# oresat-acs-card.net
KiCad netlist of a schematic drawn in EAGLE
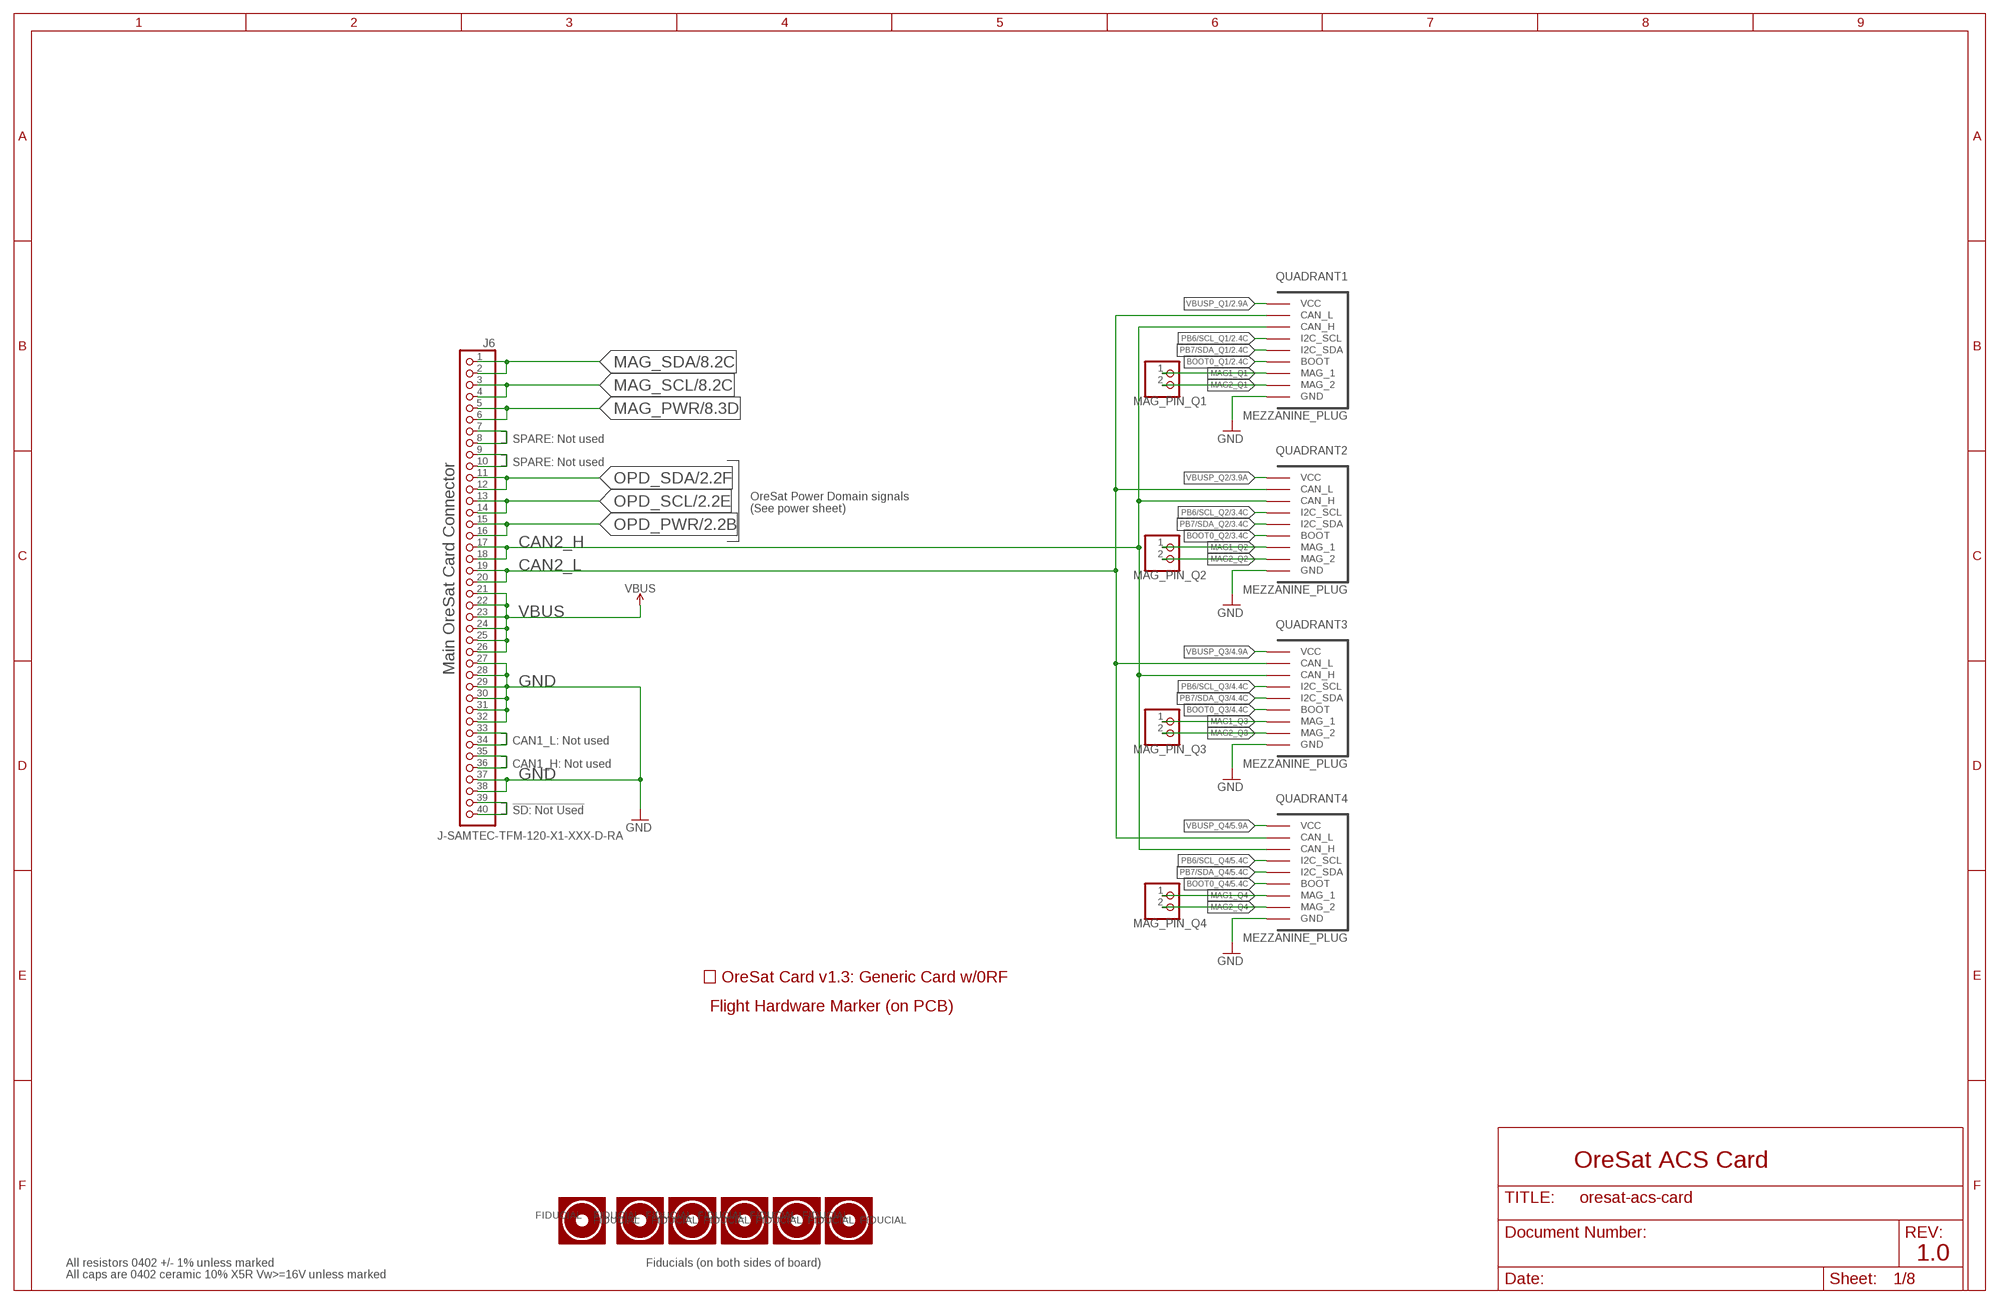
[diagram p0: schematic, sheet 1]
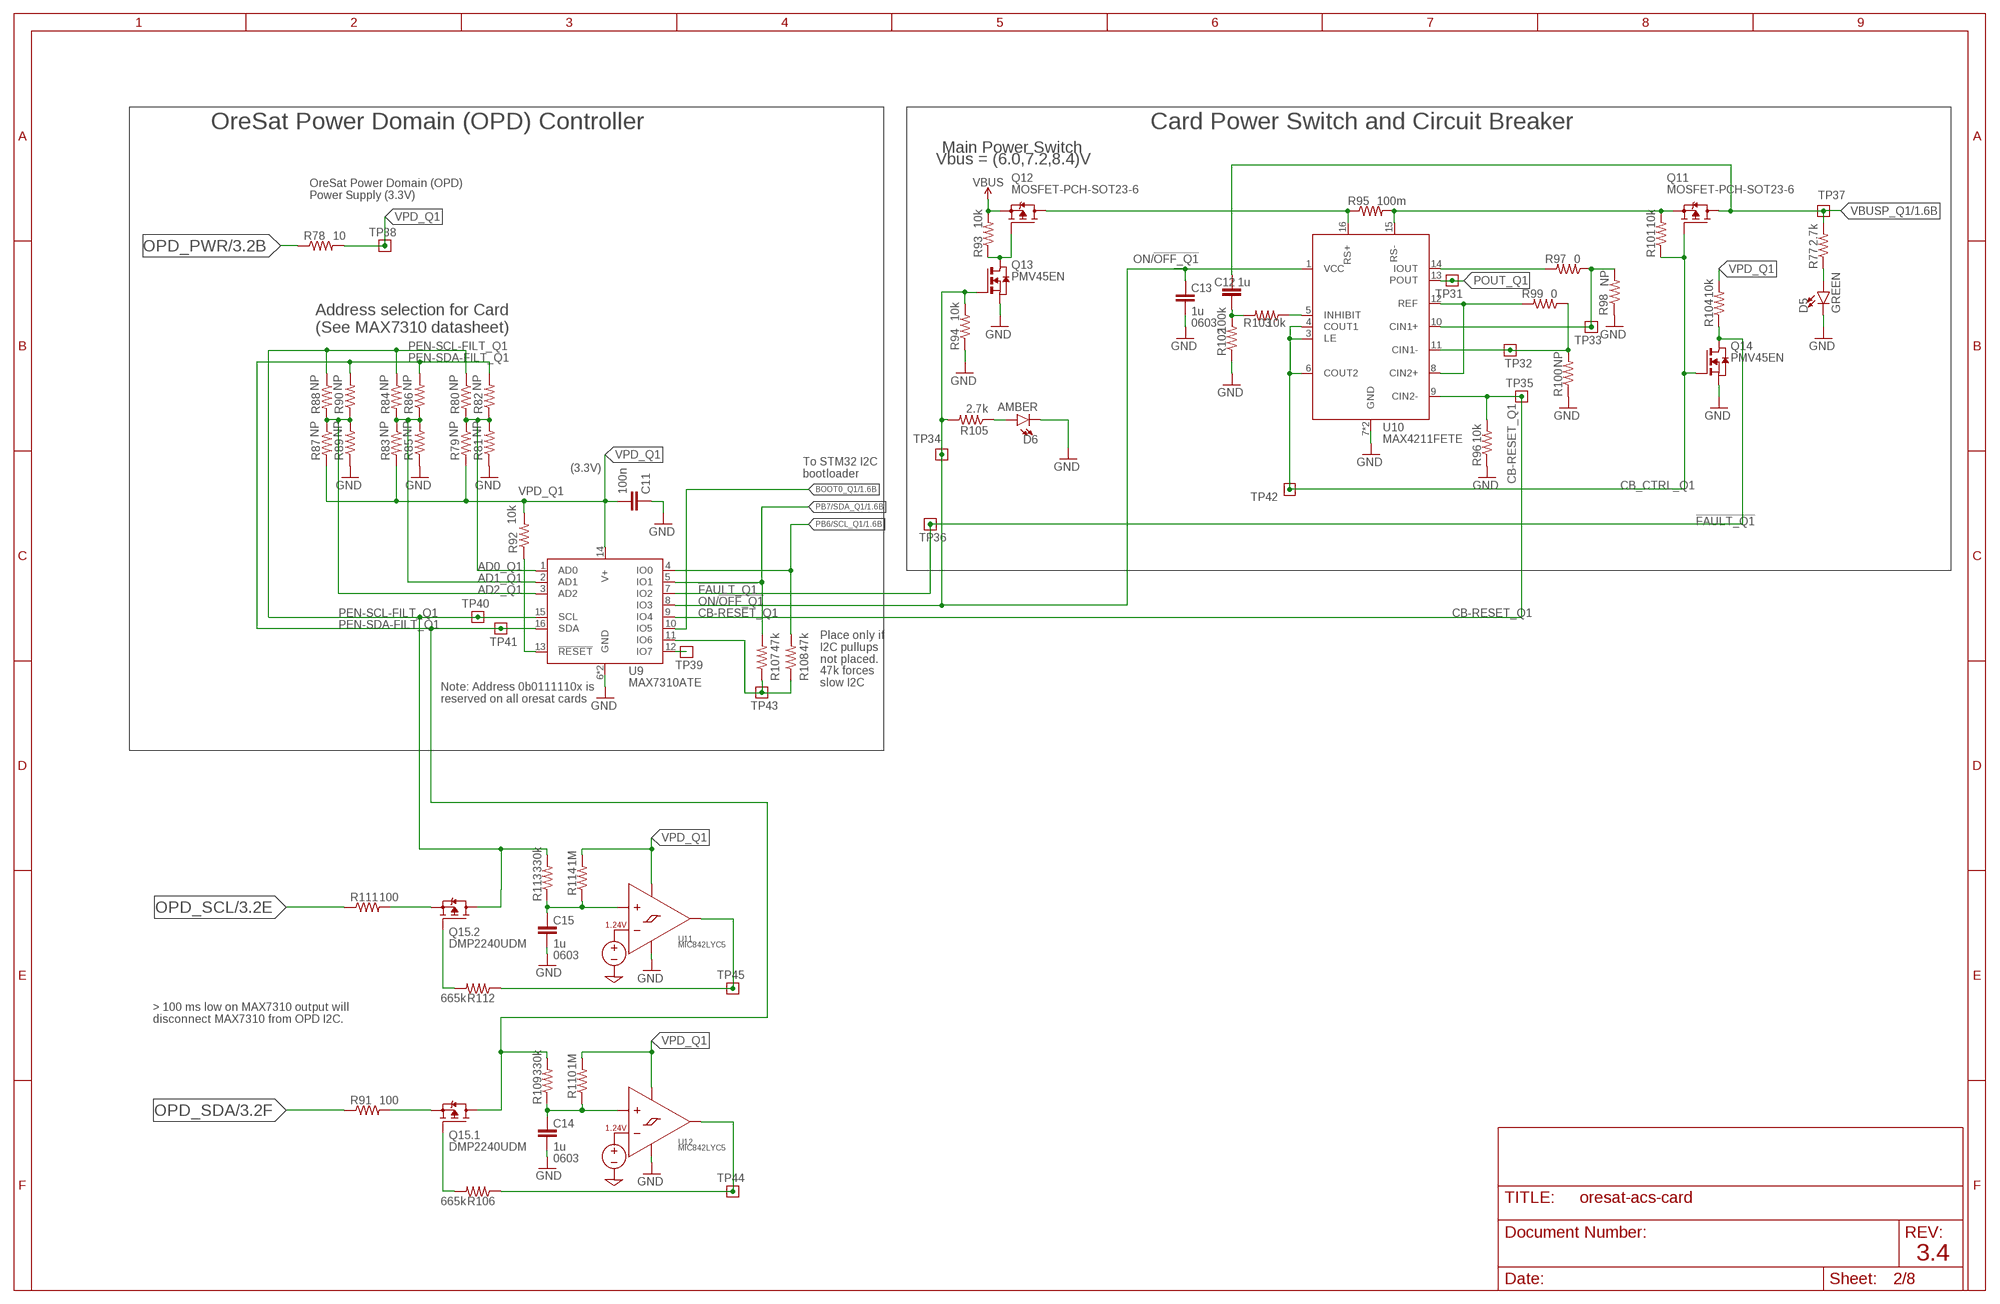
[diagram p1: schematic, sheet 2]
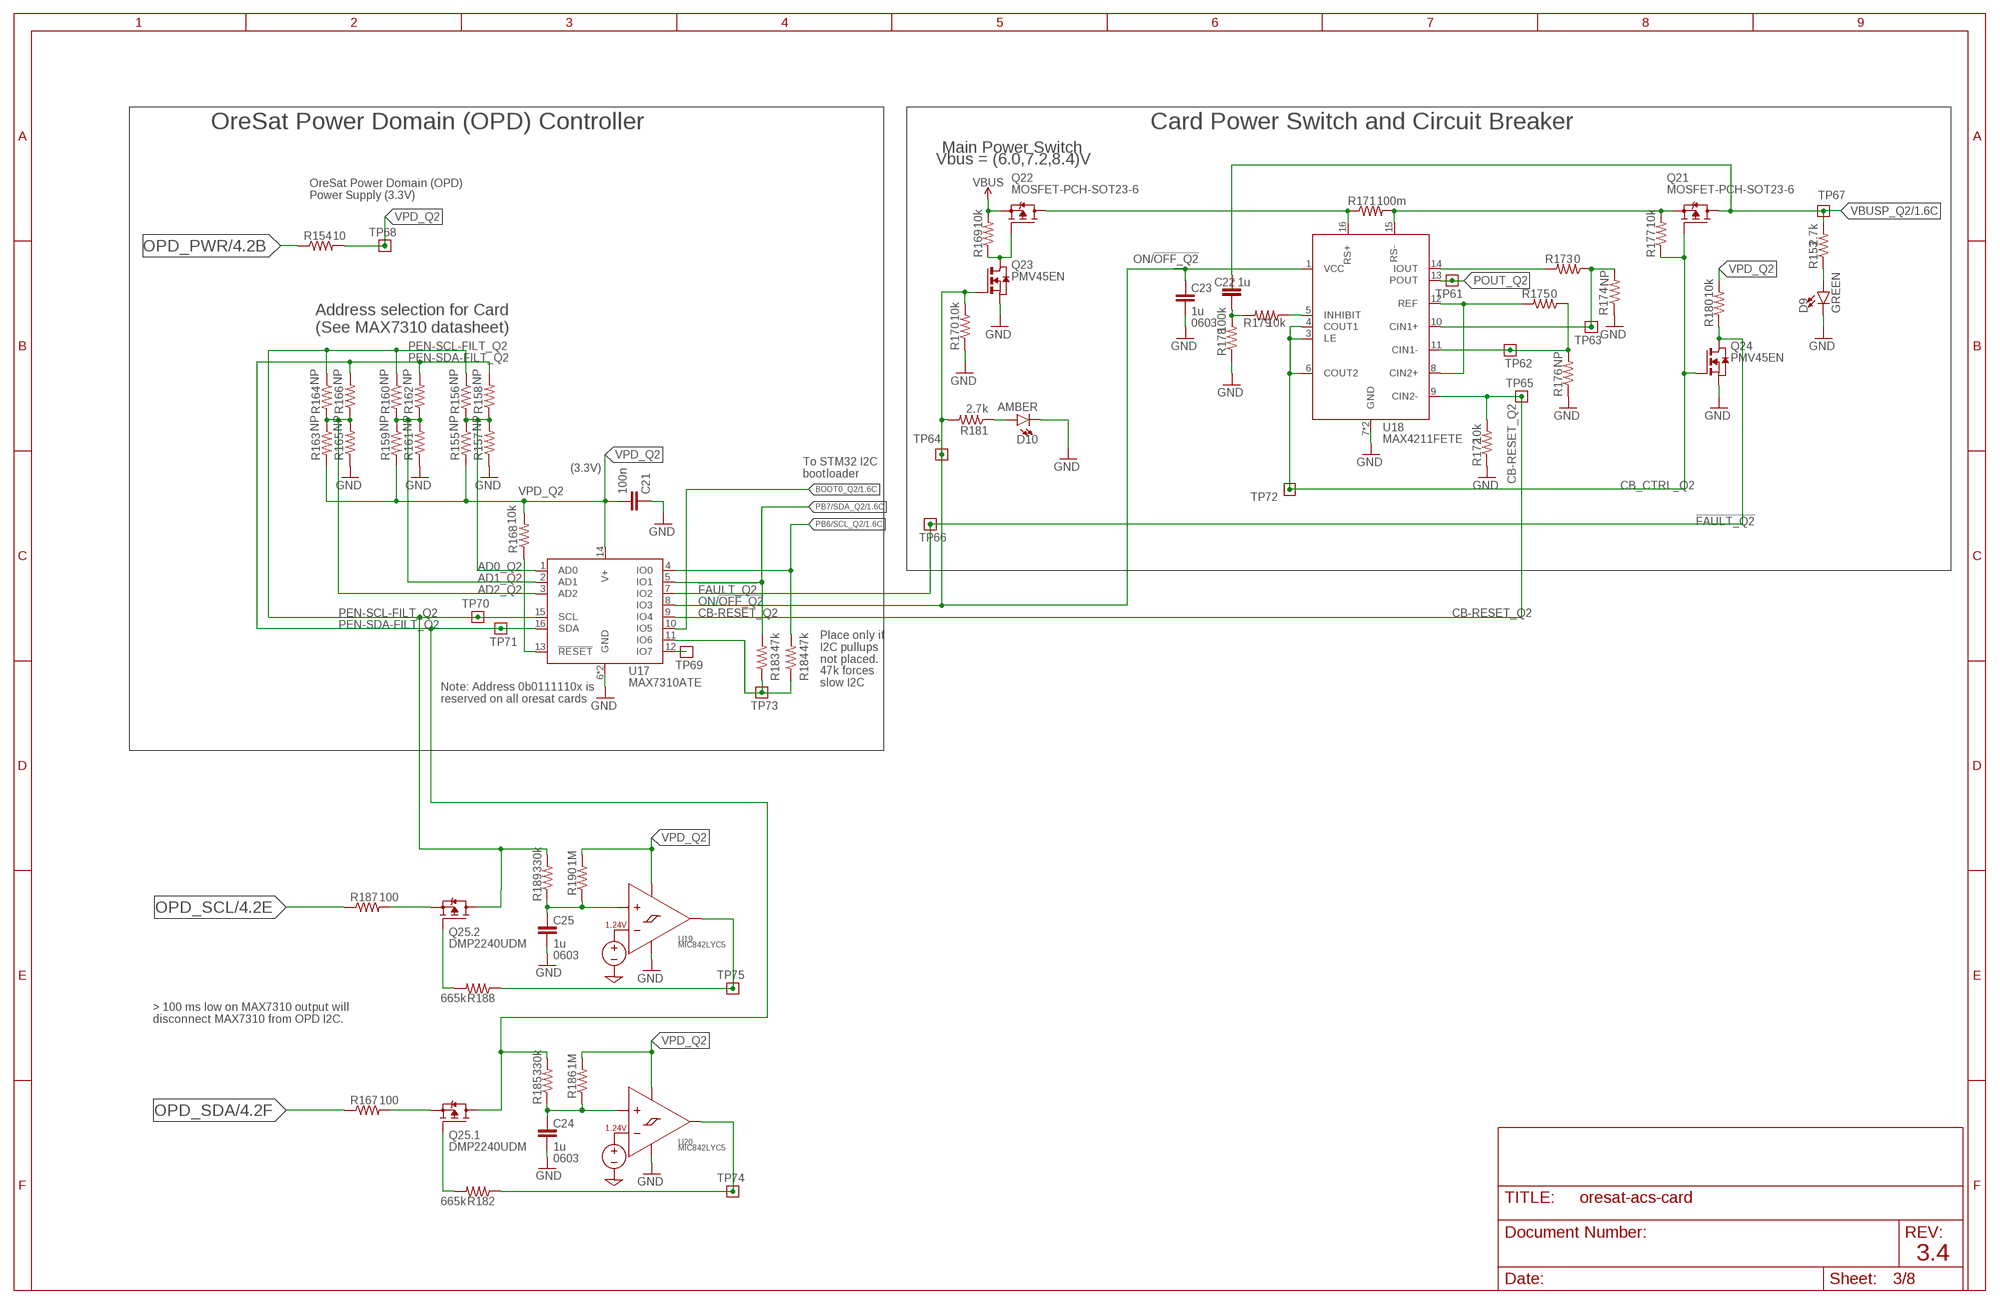
[diagram p2: schematic, sheet 3]
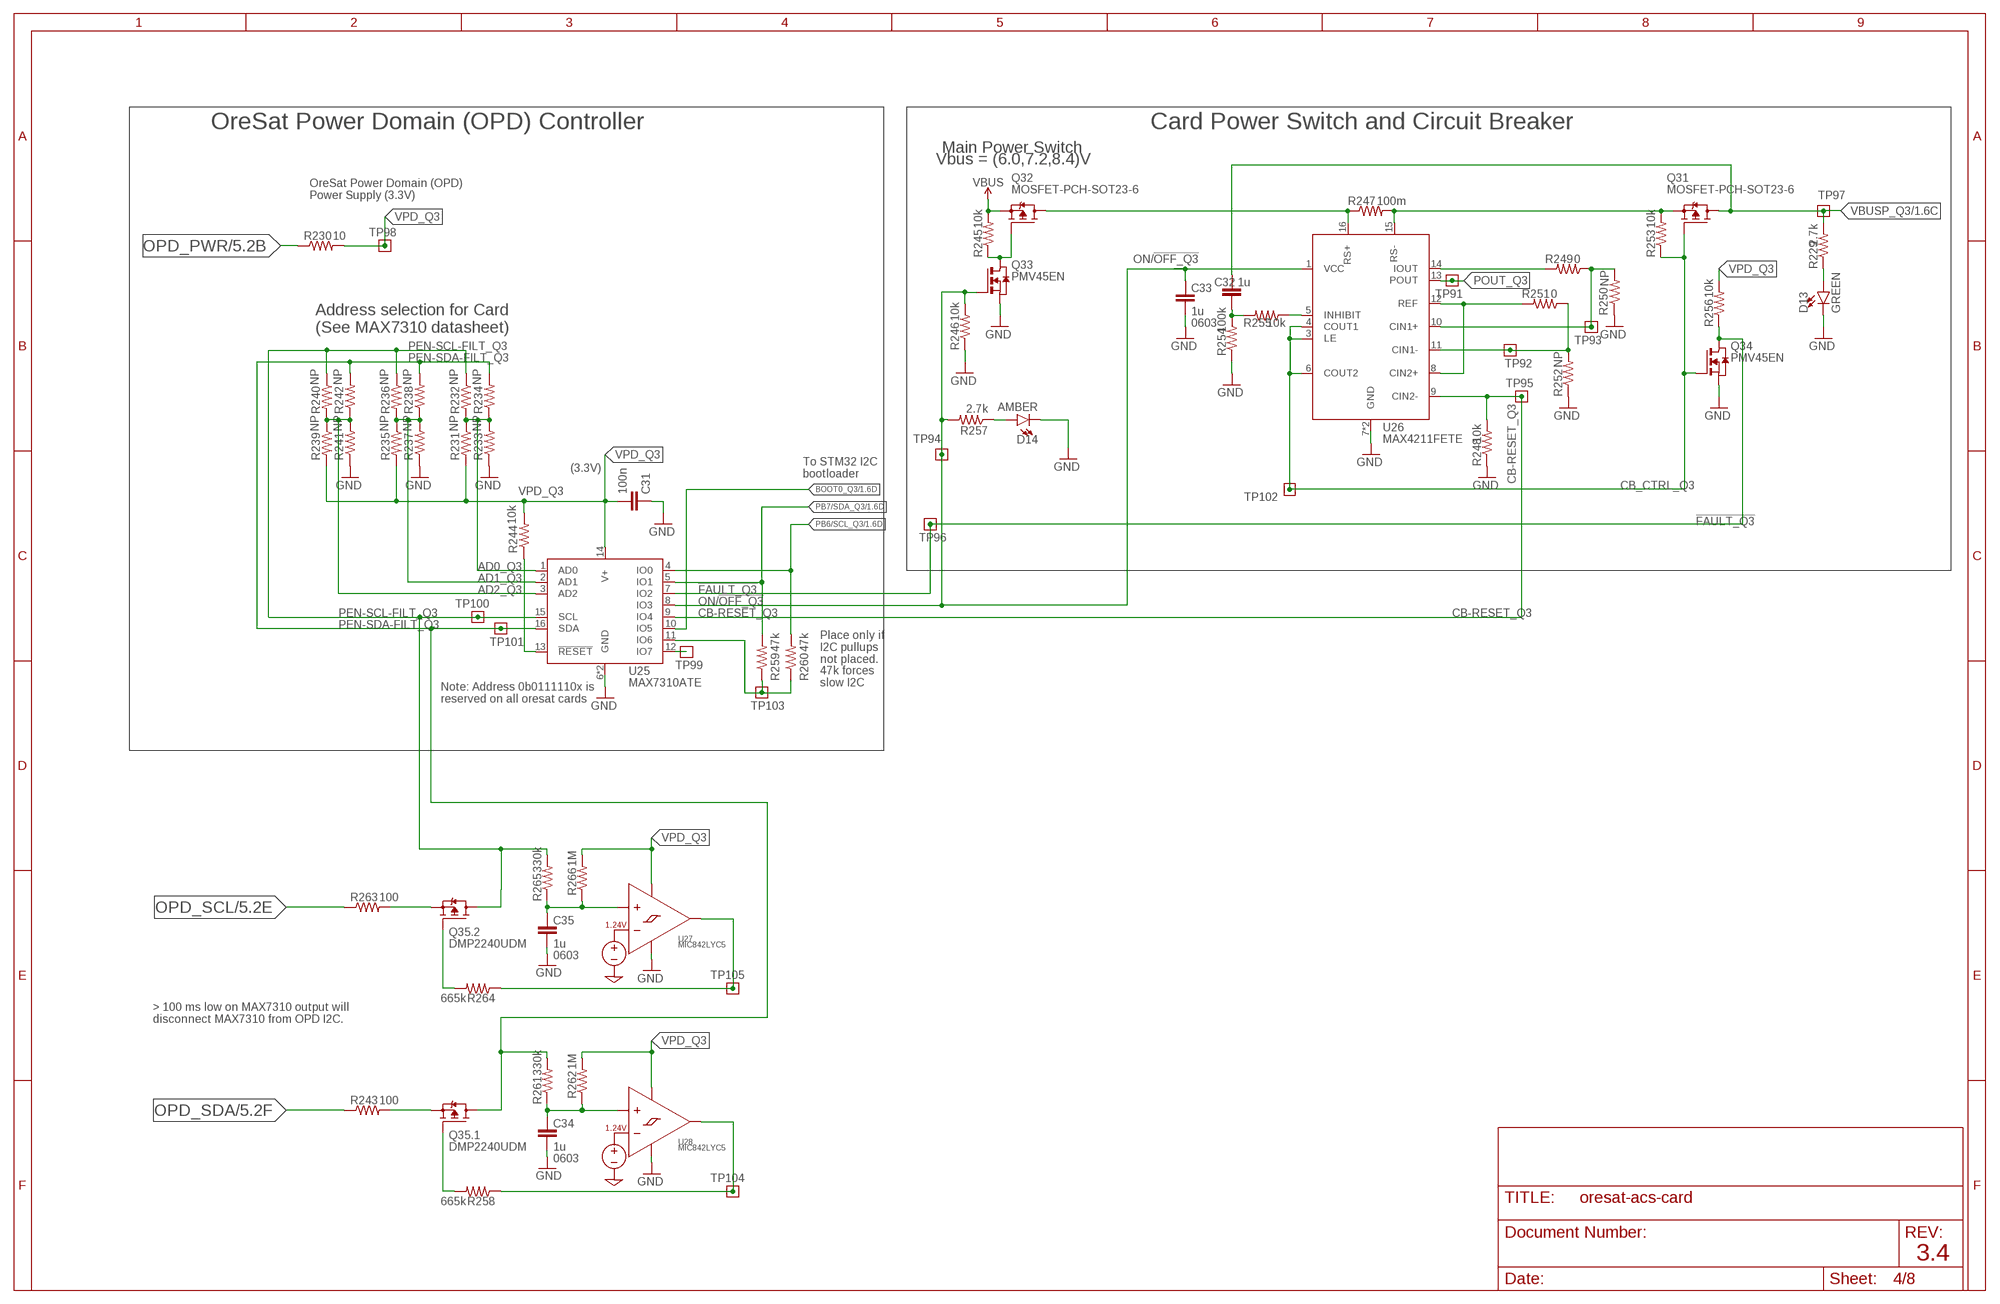
[diagram p3: schematic, sheet 4]
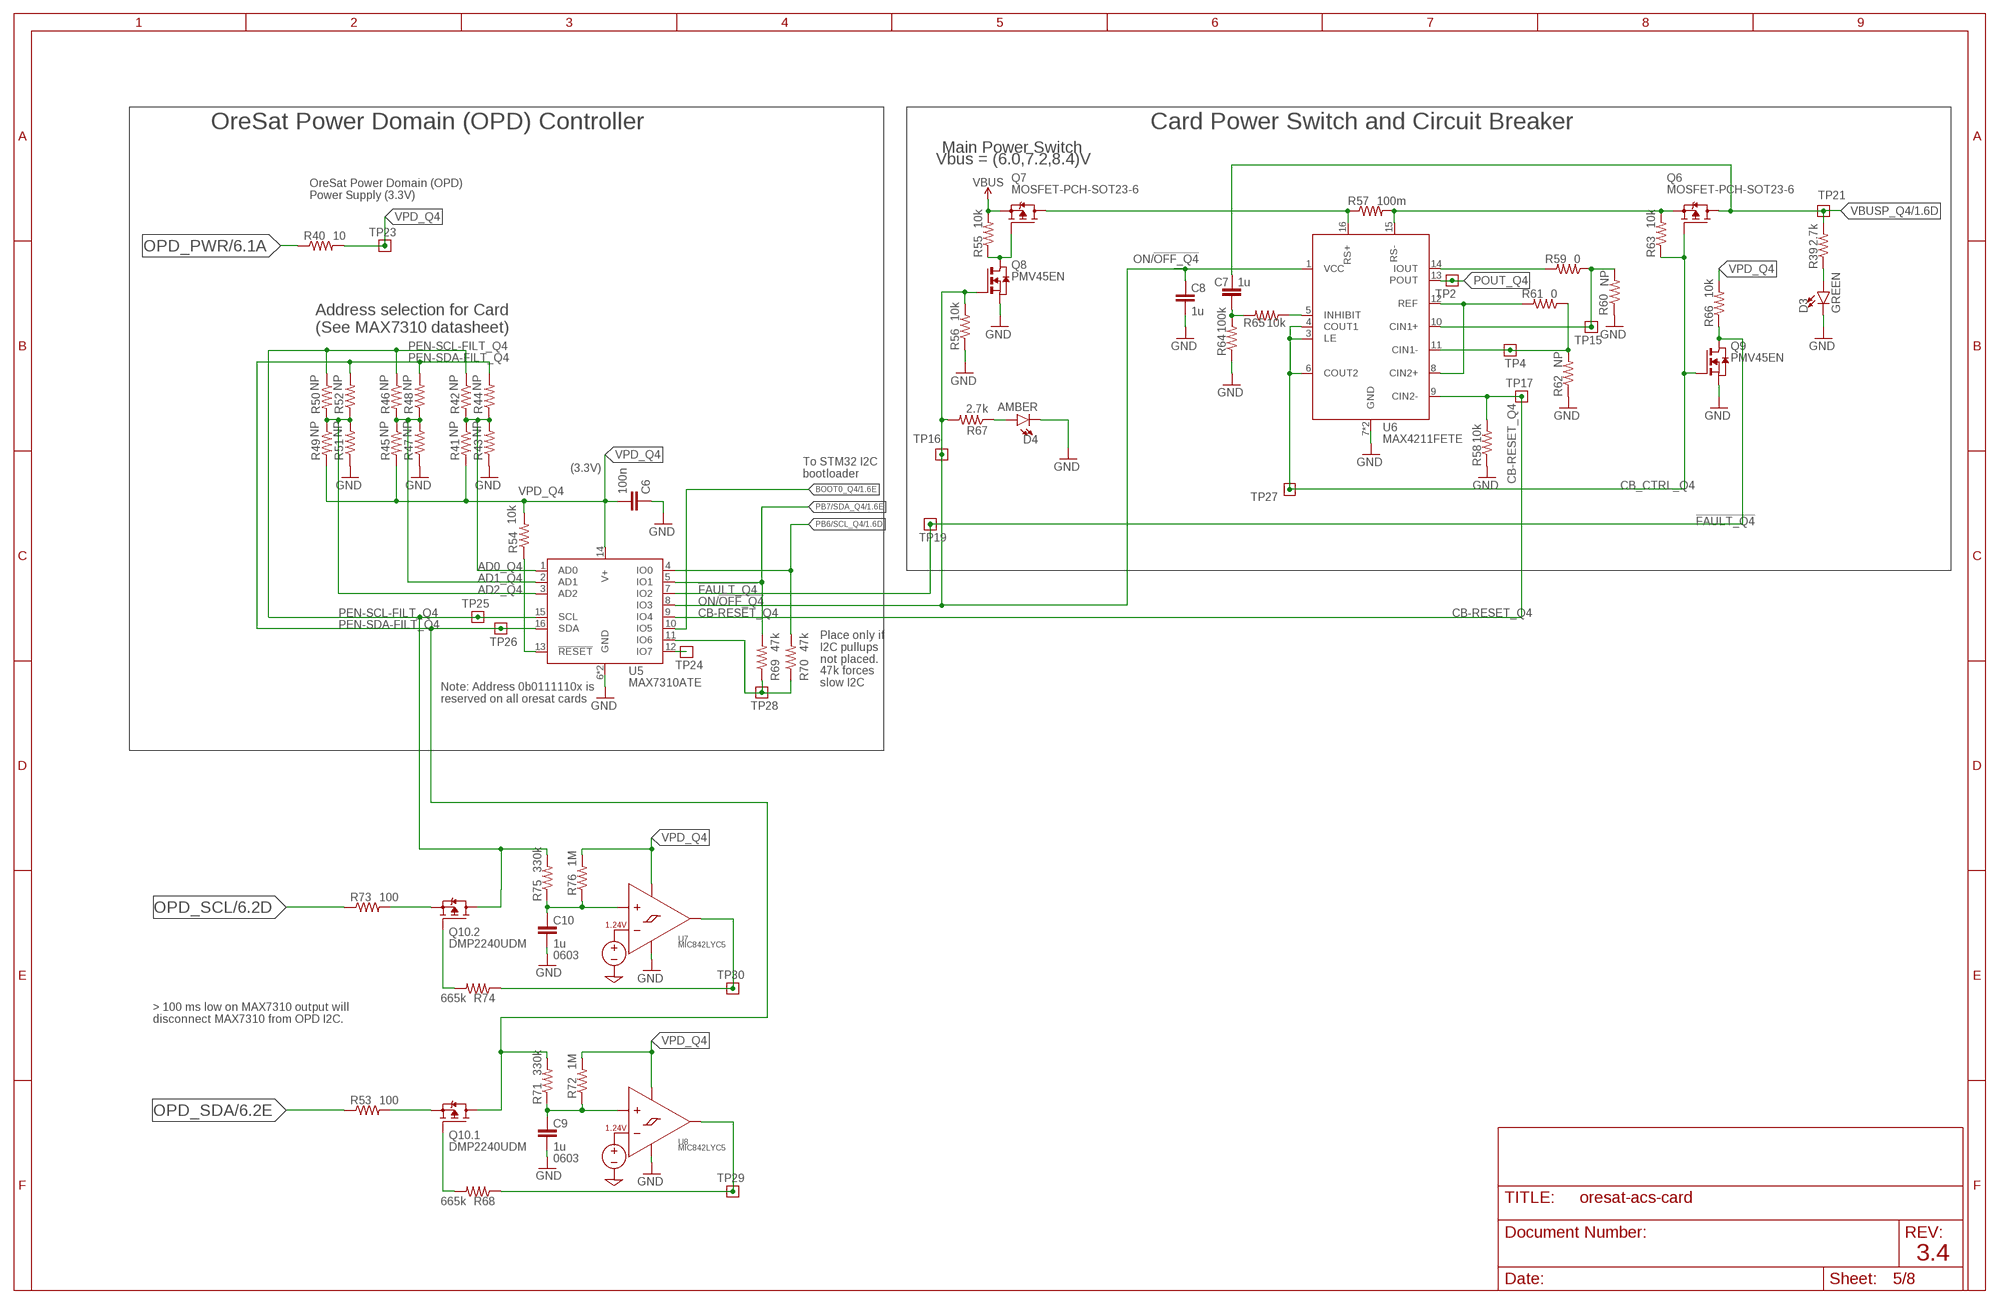
[diagram p4: schematic, sheet 5]
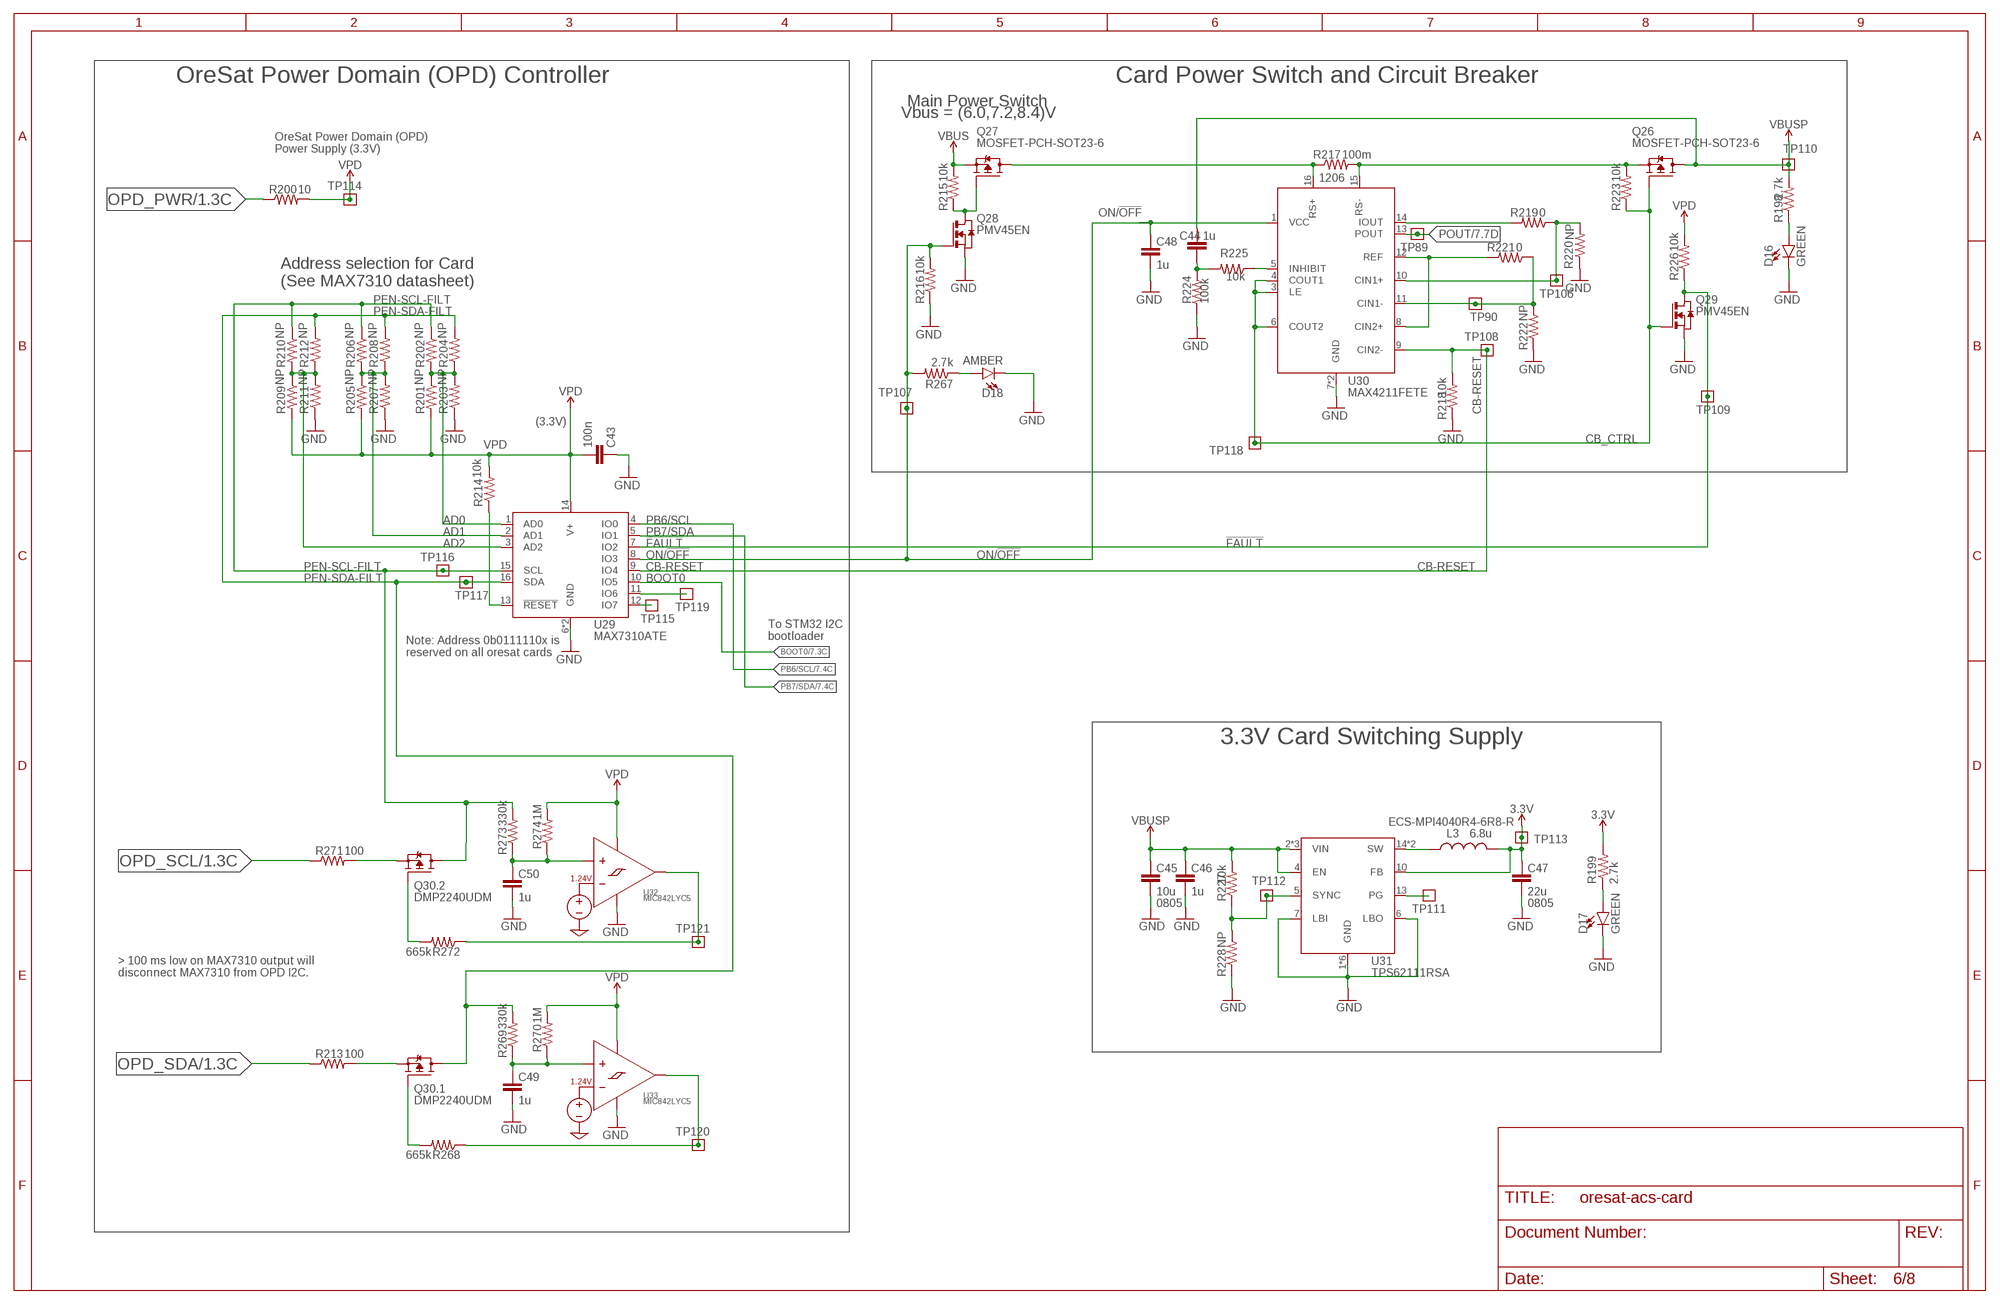
[diagram p5: schematic, sheet 6]
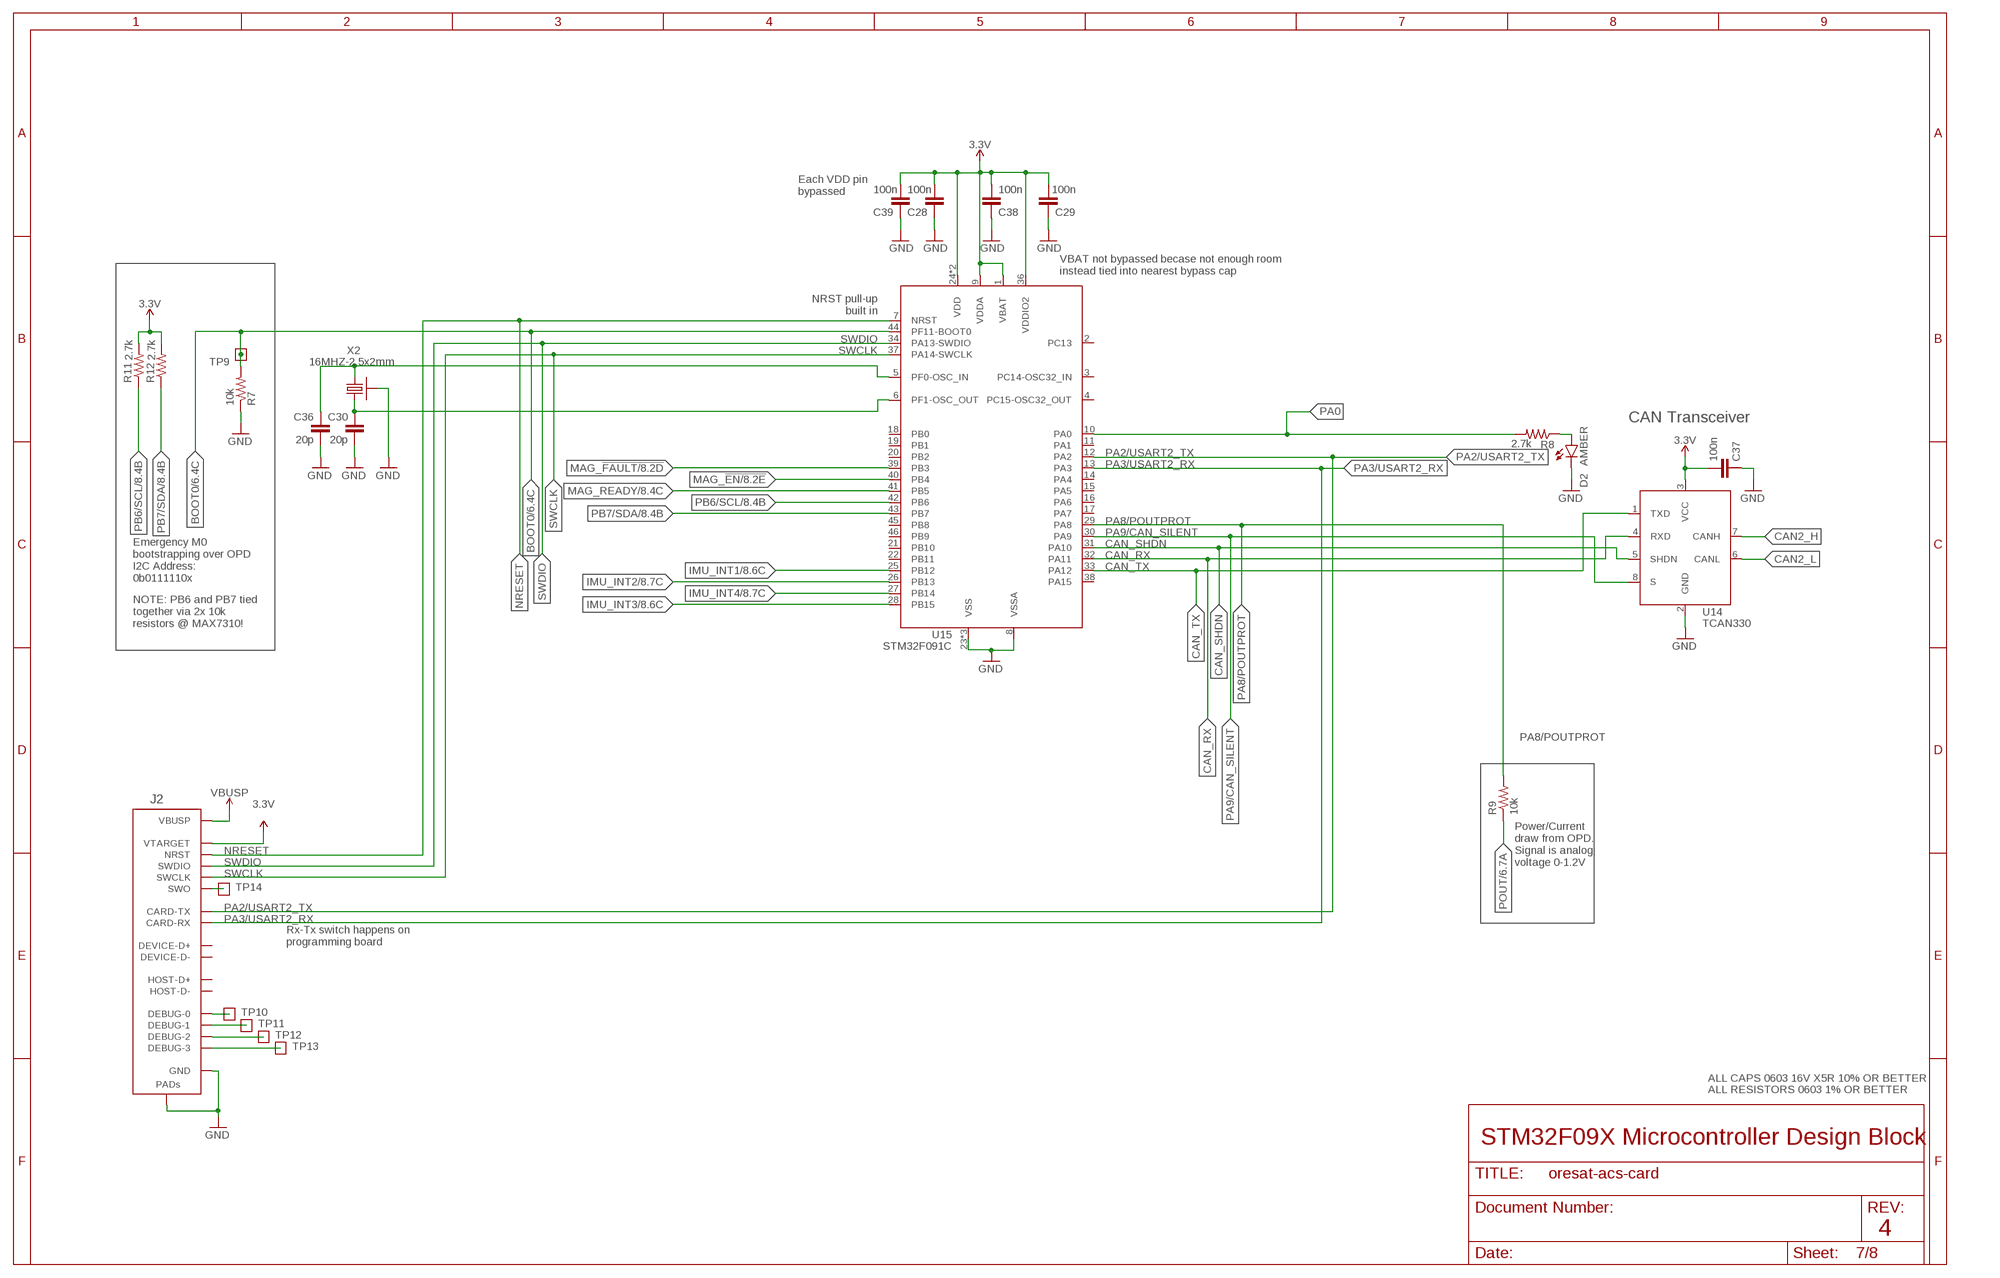
[diagram p6: schematic, sheet 7]
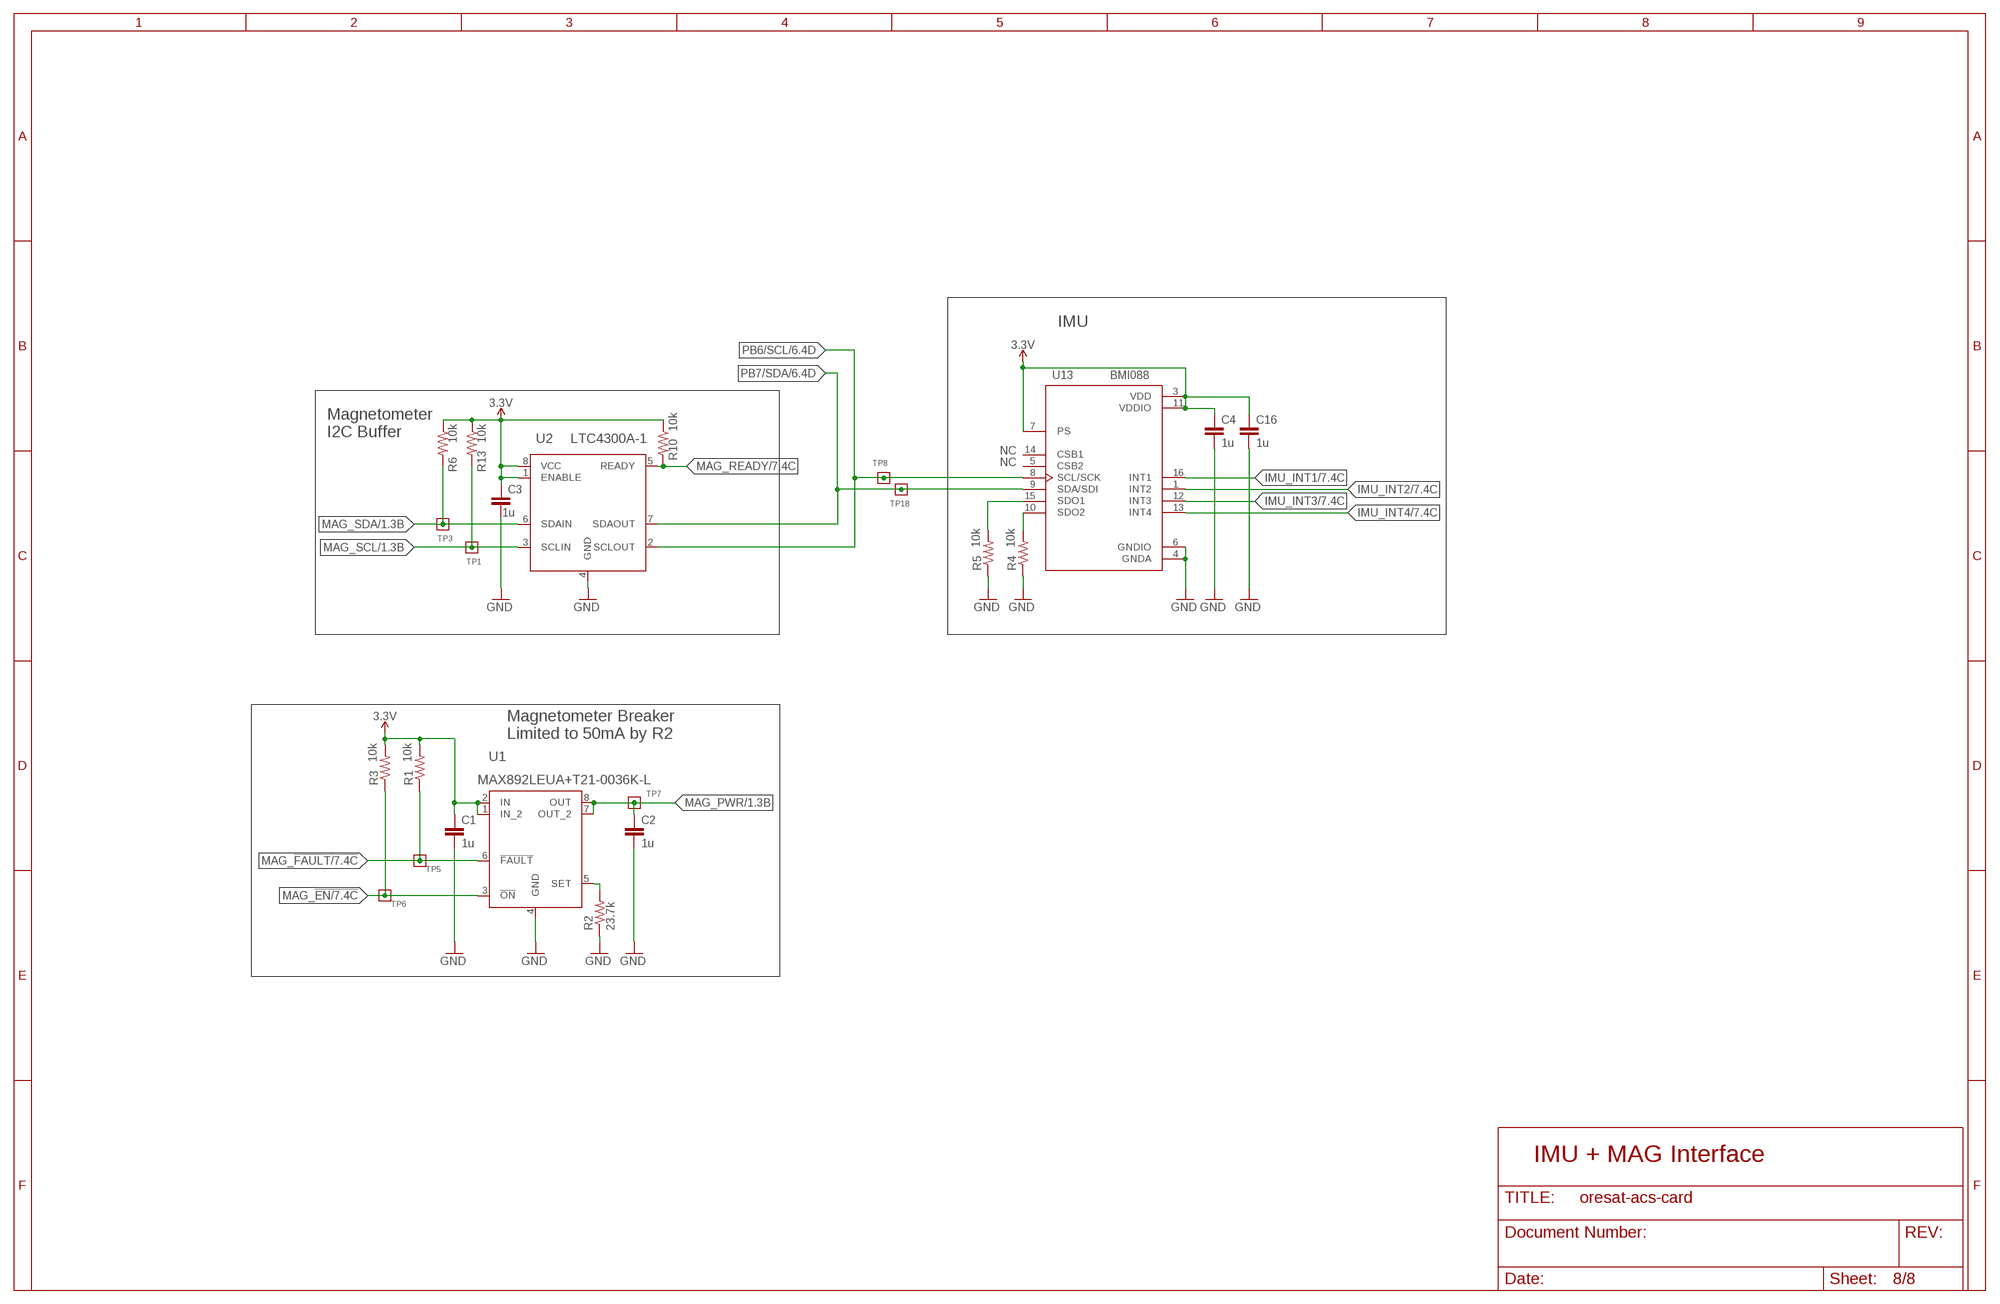
[diagram p7: schematic, sheet 8]

(export (version "E")
  (design (tool "Eeschema 10.0.6"))
  (components
    (comp (ref "C11")
      (value "100n")
      (footprint "eagle-import:.0603-C-NOSILK")
      (fields (field (name "MFR") "Samsung") (field (name "MPN") "CL05B104KO5NNNC"))
      (libsource (lib "eagle-import") (part "C-EU0603-C-NOSILK"))
    )
    (comp (ref "C12")
      (value "1u")
      (footprint "eagle-import:.0603-C-NOSILK")
      (libsource (lib "eagle-import") (part "C-EU0603-C-NOSILK"))
    )
    (comp (ref "C13")
      (value "1u")
      (footprint "eagle-import:.0603-C-NOSILK")
      (fields (field (name "MFR") "Yageo") (field (name "MPN") "CC0603KRX7R7BB105"))
      (libsource (lib "eagle-import") (part "C-EU0603-C-NOSILK"))
    )
    (comp (ref "C14")
      (value "1u")
      (footprint "eagle-import:.0603-C-NOSILK")
      (fields (field (name "MFR") "Yageo") (field (name "MPN") "CC0603KRX7R7BB105"))
      (libsource (lib "eagle-import") (part "C-EU0603-C-NOSILK"))
    )
    (comp (ref "C15")
      (value "1u")
      (footprint "eagle-import:.0603-C-NOSILK")
      (fields (field (name "MFR") "Yageo") (field (name "MPN") "CC0603KRX7R7BB105"))
      (libsource (lib "eagle-import") (part "C-EU0603-C-NOSILK"))
    )
    (comp (ref "D5")
      (value "GREEN")
      (footprint "eagle-import:LED-0603")
      (fields (field (name "MFR") "Rohm") (field (name "MPN") "SML-E12M8WT86"))
      (libsource (lib "eagle-import") (part "LED-GREEN0603"))
    )
    (comp (ref "D6")
      (value "AMBER")
      (footprint "eagle-import:LED-0603")
      (fields (field (name "MFR") "Inolux") (field (name "MPN") "IN-S63AT5A"))
      (libsource (lib "eagle-import") (part "LED-GREEN0603"))
    )
    (comp (ref "Q11")
      (value "MOSFET-PCH-SOT23-6")
      (footprint "eagle-import:SOT23-6")
      (fields (field (name "MFR") "Diodes Inc") (field (name "MPN") "DMP3050LVT-7"))
      (libsource (lib "eagle-import") (part "MOSFET-PCH-SOT23-6"))
    )
    (comp (ref "Q12")
      (value "MOSFET-PCH-SOT23-6")
      (footprint "eagle-import:SOT23-6")
      (fields (field (name "MFR") "Diodes Inc") (field (name "MPN") "DMP3050LVT-7"))
      (libsource (lib "eagle-import") (part "MOSFET-PCH-SOT23-6"))
    )
    (comp (ref "Q13")
      (value "PMV45EN")
      (footprint "eagle-import:SOT23")
      (fields (field (name "MFR") "Nexperia") (field (name "MPN") "PMV45EN2R"))
      (libsource (lib "eagle-import") (part "PMV45EN"))
    )
    (comp (ref "Q14")
      (value "PMV45EN")
      (footprint "eagle-import:SOT23")
      (fields (field (name "MFR") "Nexperia") (field (name "MPN") "PMV45EN2R"))
      (libsource (lib "eagle-import") (part "PMV45EN"))
    )
    (comp (ref "Q15")
      (value "DMP2240UDM")
      (footprint "eagle-import:SOT23-6")
      (fields
        (field (name "DIS") "Digi-Key")
        (field (name "DPN") "DMP2240UDMDICT-ND")
        (field (name "MFR") "Diodes Inc")
        (field (name "MPN") "DMP2240UDM")
      )
      (libsource (lib "eagle-import") (part "Q-MOSFET-PCH-dual-SOT23-6_MOSFET-PCH-SOT23-6"))
    )
    (comp (ref "R77")
      (value "2.7k")
      (footprint "eagle-import:.0603-C-NOSILK")
      (fields (field (name "MFR") "TE Connectivity") (field (name "MPN") "CRGCQ0603F2K7"))
      (libsource (lib "eagle-import") (part "R-US_0603-C-NOSILK"))
    )
    (comp (ref "R78")
      (value "10")
      (footprint "eagle-import:.0603-C-NOSILK")
      (fields (field (name "MFR") "Yageo") (field (name "MPN") "RC0603FR-0710RL"))
      (libsource (lib "eagle-import") (part "R-US_0603-C-NOSILK"))
    )
    (comp (ref "R79")
      (value "NP")
      (footprint "eagle-import:.0603-C-NOSILK")
      (fields (field (name "MFR") "Samsung") (field (name "MPN") "RC1005F6653CS"))
      (libsource (lib "eagle-import") (part "R-US_0603-C-NOSILK"))
    )
    (comp (ref "R80")
      (value "NP")
      (footprint "eagle-import:.0603-C-NOSILK")
      (fields (field (name "MFR") "Samsung") (field (name "MPN") "RC1005F6653CS"))
      (libsource (lib "eagle-import") (part "R-US_0603-C-NOSILK"))
    )
    (comp (ref "R81")
      (value "NP")
      (footprint "eagle-import:.0603-C-NOSILK")
      (fields (field (name "MFR") "Samsung") (field (name "MPN") "RC1005F6653CS"))
      (libsource (lib "eagle-import") (part "R-US_0603-C-NOSILK"))
    )
    (comp (ref "R82")
      (value "NP")
      (footprint "eagle-import:.0603-C-NOSILK")
      (fields (field (name "MFR") "Samsung") (field (name "MPN") "RC1005F6653CS"))
      (libsource (lib "eagle-import") (part "R-US_0603-C-NOSILK"))
    )
    (comp (ref "R83")
      (value "NP")
      (footprint "eagle-import:.0603-C-NOSILK")
      (fields (field (name "MFR") "Samsung") (field (name "MPN") "RC1005F6653CS"))
      (libsource (lib "eagle-import") (part "R-US_0603-C-NOSILK"))
    )
    (comp (ref "R84")
      (value "NP")
      (footprint "eagle-import:.0603-C-NOSILK")
      (fields (field (name "MFR") "Samsung") (field (name "MPN") "RC1005F6653CS"))
      (libsource (lib "eagle-import") (part "R-US_0603-C-NOSILK"))
    )
    (comp (ref "R85")
      (value "NP")
      (footprint "eagle-import:.0603-C-NOSILK")
      (fields (field (name "MFR") "Samsung") (field (name "MPN") "RC1005F6653CS"))
      (libsource (lib "eagle-import") (part "R-US_0603-C-NOSILK"))
    )
    (comp (ref "R86")
      (value "NP")
      (footprint "eagle-import:.0603-C-NOSILK")
      (fields (field (name "MFR") "Samsung") (field (name "MPN") "RC1005F6653CS"))
      (libsource (lib "eagle-import") (part "R-US_0603-C-NOSILK"))
    )
    (comp (ref "R87")
      (value "NP")
      (footprint "eagle-import:.0603-C-NOSILK")
      (fields (field (name "MFR") "Samsung") (field (name "MPN") "RC1005F6653CS"))
      (libsource (lib "eagle-import") (part "R-US_0603-C-NOSILK"))
    )
    (comp (ref "R88")
      (value "NP")
      (footprint "eagle-import:.0603-C-NOSILK")
      (fields (field (name "MFR") "Samsung") (field (name "MPN") "RC1005F6653CS"))
      (libsource (lib "eagle-import") (part "R-US_0603-C-NOSILK"))
    )
    (comp (ref "R89")
      (value "NP")
      (footprint "eagle-import:.0603-C-NOSILK")
      (fields (field (name "MFR") "Samsung") (field (name "MPN") "RC1005F6653CS"))
      (libsource (lib "eagle-import") (part "R-US_0603-C-NOSILK"))
    )
    (comp (ref "R90")
      (value "NP")
      (footprint "eagle-import:.0603-C-NOSILK")
      (fields (field (name "MFR") "Samsung") (field (name "MPN") "RC1005F6653CS"))
      (libsource (lib "eagle-import") (part "R-US_0603-C-NOSILK"))
    )
    (comp (ref "R91")
      (value "100")
      (footprint "eagle-import:.0603-C-NOSILK")
      (fields (field (name "MFR") "Yageo") (field (name "MPN") "RC0603FR-07100RL"))
      (libsource (lib "eagle-import") (part "R-US_0603-C-NOSILK"))
    )
    (comp (ref "R92")
      (value "10k")
      (footprint "eagle-import:.0603-C-NOSILK")
      (fields (field (name "MFR") "Yageo") (field (name "MPN") "RC0603FR-0710KL"))
      (libsource (lib "eagle-import") (part "R-US_0603-C-NOSILK"))
    )
    (comp (ref "R93")
      (value "10k")
      (footprint "eagle-import:.0603-C-NOSILK")
      (fields (field (name "MFR") "Yageo") (field (name "MPN") "RC0603FR-0710KL"))
      (libsource (lib "eagle-import") (part "R-US_0603-C-NOSILK"))
    )
    (comp (ref "R94")
      (value "10k")
      (footprint "eagle-import:.0603-C-NOSILK")
      (fields (field (name "MFR") "Yageo") (field (name "MPN") "RC0603FR-0710KL"))
      (libsource (lib "eagle-import") (part "R-US_0603-C-NOSILK"))
    )
    (comp (ref "R95")
      (value "100m")
      (footprint "eagle-import:R1206")
      (fields (field (name "MFR") "Stackpole") (field (name "MPN") "CSR1206FTR100"))
      (libsource (lib "eagle-import") (part "rcl_334_R-US_R1206"))
    )
    (comp (ref "R96")
      (value "10k")
      (footprint "eagle-import:.0603-C-NOSILK")
      (fields (field (name "MFR") "Yageo") (field (name "MPN") "RC0603FR-0710KL"))
      (libsource (lib "eagle-import") (part "R-US_0603-C-NOSILK"))
    )
    (comp (ref "R97")
      (value "0")
      (footprint "eagle-import:.0603-C-NOSILK")
      (fields (field (name "MFR") "Yageo") (field (name "MPN") "RC0603JR-070RL"))
      (libsource (lib "eagle-import") (part "R-US_0603-C-NOSILK"))
    )
    (comp (ref "R98")
      (value "NP")
      (footprint "eagle-import:.0603-C-NOSILK")
      (fields (field (name "MFR") "Samsung") (field (name "MPN") "RC1005F6653CS"))
      (libsource (lib "eagle-import") (part "R-US_0603-C-NOSILK"))
    )
    (comp (ref "R99")
      (value "0")
      (footprint "eagle-import:.0603-C-NOSILK")
      (fields (field (name "MFR") "Yageo") (field (name "MPN") "RC0603JR-070RL"))
      (libsource (lib "eagle-import") (part "R-US_0603-C-NOSILK"))
    )
    (comp (ref "R100")
      (value "NP")
      (footprint "eagle-import:.0603-C-NOSILK")
      (fields (field (name "MFR") "Samsung") (field (name "MPN") "RC1005F6653CS"))
      (libsource (lib "eagle-import") (part "R-US_0603-C-NOSILK"))
    )
    (comp (ref "R101")
      (value "10k")
      (footprint "eagle-import:.0603-C-NOSILK")
      (fields (field (name "MFR") "Yageo") (field (name "MPN") "RC0603FR-0710KL"))
      (libsource (lib "eagle-import") (part "R-US_0603-C-NOSILK"))
    )
    (comp (ref "R102")
      (value "100k")
      (footprint "eagle-import:.0603-C-NOSILK")
      (fields (field (name "MFR") "Samsung") (field (name "MPN") "RC1005F6653CS"))
      (libsource (lib "eagle-import") (part "R-US_0603-C-NOSILK"))
    )
    (comp (ref "R103")
      (value "10k")
      (footprint "eagle-import:.0603-C-NOSILK")
      (fields (field (name "MFR") "Samsung") (field (name "MPN") "RC1005F6653CS"))
      (libsource (lib "eagle-import") (part "R-US_0603-C-NOSILK"))
    )
    (comp (ref "R104")
      (value "10k")
      (footprint "eagle-import:.0603-C-NOSILK")
      (fields (field (name "MFR") "Yageo") (field (name "MPN") "RC0603FR-0710KL"))
      (libsource (lib "eagle-import") (part "R-US_0603-C-NOSILK"))
    )
    (comp (ref "R105")
      (value "2.7k")
      (footprint "eagle-import:.0603-C-NOSILK")
      (fields (field (name "MFR") "TE Connectivity") (field (name "MPN") "CRGCQ0603F2K7"))
      (libsource (lib "eagle-import") (part "R-US_0603-C-NOSILK"))
    )
    (comp (ref "R106")
      (value "665k")
      (footprint "eagle-import:.0603-C-NOSILK")
      (fields (field (name "MFR") "Yageo") (field (name "MPN") "RC0603FR-07665KL"))
      (libsource (lib "eagle-import") (part "R-US_0603-C-NOSILK"))
    )
    (comp (ref "R107")
      (value "47k")
      (footprint "eagle-import:.0603-C-NOSILK")
      (fields (field (name "MFR") "Yageo") (field (name "MPN") "RC0603FR-0747KL"))
      (libsource (lib "eagle-import") (part "R-US_0603-C-NOSILK"))
    )
    (comp (ref "R108")
      (value "47k")
      (footprint "eagle-import:.0603-C-NOSILK")
      (fields (field (name "MFR") "Yageo") (field (name "MPN") "RC0603FR-0747KL"))
      (libsource (lib "eagle-import") (part "R-US_0603-C-NOSILK"))
    )
    (comp (ref "R109")
      (value "330k")
      (footprint "eagle-import:.0603-C-NOSILK")
      (fields (field (name "MFR") "Vishay") (field (name "MPN") "MCT06030C3303FP000"))
      (libsource (lib "eagle-import") (part "R-US_0603-C-NOSILK"))
    )
    (comp (ref "R110")
      (value "1M")
      (footprint "eagle-import:.0603-C-NOSILK")
      (fields (field (name "MFR") "Yageo") (field (name "MPN") "RC0603FR-071ML"))
      (libsource (lib "eagle-import") (part "R-US_0603-C-NOSILK"))
    )
    (comp (ref "R111")
      (value "100")
      (footprint "eagle-import:.0603-C-NOSILK")
      (fields (field (name "MFR") "Yageo") (field (name "MPN") "RC0603FR-07100RL"))
      (libsource (lib "eagle-import") (part "R-US_0603-C-NOSILK"))
    )
    (comp (ref "R112")
      (value "665k")
      (footprint "eagle-import:.0603-C-NOSILK")
      (fields (field (name "MFR") "Yageo") (field (name "MPN") "RC0603FR-07665KL"))
      (libsource (lib "eagle-import") (part "R-US_0603-C-NOSILK"))
    )
    (comp (ref "R113")
      (value "330k")
      (footprint "eagle-import:.0603-C-NOSILK")
      (fields (field (name "MFR") "Vishay") (field (name "MPN") "MCT06030C3303FP000"))
      (libsource (lib "eagle-import") (part "R-US_0603-C-NOSILK"))
    )
    (comp (ref "R114")
      (value "1M")
      (footprint "eagle-import:.0603-C-NOSILK")
      (fields (field (name "MFR") "Yageo") (field (name "MPN") "RC0603FR-071ML"))
      (libsource (lib "eagle-import") (part "R-US_0603-C-NOSILK"))
    )
    (comp (ref "TP31")
      (value "TEST-POINT-LARGE-SQUARE")
      (footprint "eagle-import:1X01")
      (libsource (lib "eagle-import") (part "TEST-POINT-LARGE-SQUARE"))
    )
    (comp (ref "TP32")
      (value "TEST-POINT-LARGE-SQUARE")
      (footprint "eagle-import:1X01")
      (libsource (lib "eagle-import") (part "TEST-POINT-LARGE-SQUARE"))
    )
    (comp (ref "TP33")
      (value "TEST-POINT-LARGE-SQUARE")
      (footprint "eagle-import:1X01")
      (libsource (lib "eagle-import") (part "TEST-POINT-LARGE-SQUARE"))
    )
    (comp (ref "TP34")
      (value "TEST-POINT-LARGE-SQUARE")
      (footprint "eagle-import:1X01")
      (libsource (lib "eagle-import") (part "TEST-POINT-LARGE-SQUARE"))
    )
    (comp (ref "TP35")
      (value "TEST-POINT-LARGE-SQUARE")
      (footprint "eagle-import:1X01")
      (libsource (lib "eagle-import") (part "TEST-POINT-LARGE-SQUARE"))
    )
    (comp (ref "TP36")
      (value "TEST-POINT-LARGE-SQUARE")
      (footprint "eagle-import:1X01")
      (libsource (lib "eagle-import") (part "TEST-POINT-LARGE-SQUARE"))
    )
    (comp (ref "TP37")
      (value "TEST-POINT-LARGE-SQUARE")
      (footprint "eagle-import:1X01")
      (libsource (lib "eagle-import") (part "TEST-POINT-LARGE-SQUARE"))
    )
    (comp (ref "TP38")
      (value "TEST-POINT-LARGE-SQUARE")
      (footprint "eagle-import:1X01")
      (libsource (lib "eagle-import") (part "TEST-POINT-LARGE-SQUARE"))
    )
    (comp (ref "TP39")
      (value "TEST-POINT-LARGE-SQUARE")
      (footprint "eagle-import:1X01")
      (libsource (lib "eagle-import") (part "TEST-POINT-LARGE-SQUARE"))
    )
    (comp (ref "TP40")
      (value "TEST-POINT-LARGE-SQUARE")
      (footprint "eagle-import:1X01")
      (libsource (lib "eagle-import") (part "TEST-POINT-LARGE-SQUARE"))
    )
    (comp (ref "TP41")
      (value "TEST-POINT-LARGE-SQUARE")
      (footprint "eagle-import:1X01")
      (libsource (lib "eagle-import") (part "TEST-POINT-LARGE-SQUARE"))
    )
    (comp (ref "TP42")
      (value "TEST-POINT-LARGE-SQUARE")
      (footprint "eagle-import:1X01")
      (libsource (lib "eagle-import") (part "TEST-POINT-LARGE-SQUARE"))
    )
    (comp (ref "TP43")
      (value "TEST-POINT-LARGE-SQUARE")
      (footprint "eagle-import:1X01")
      (libsource (lib "eagle-import") (part "TEST-POINT-LARGE-SQUARE"))
    )
    (comp (ref "TP44")
      (value "TEST-POINT-LARGE-SQUARE")
      (footprint "eagle-import:1X01")
      (libsource (lib "eagle-import") (part "TEST-POINT-LARGE-SQUARE"))
    )
    (comp (ref "TP45")
      (value "TEST-POINT-LARGE-SQUARE")
      (footprint "eagle-import:1X01")
      (libsource (lib "eagle-import") (part "TEST-POINT-LARGE-SQUARE"))
    )
    (comp (ref "U9")
      (value "MAX7310ATE")
      (footprint "eagle-import:QFN65P400X400X80-17T210")
      (fields (field (name "MFR") "Maxim"))
      (libsource (lib "eagle-import") (part "MAX7310"))
    )
    (comp (ref "U10")
      (value "MAX4211FETE")
      (footprint "eagle-import:QFN65P400X400X80-17T210")
      (fields (field (name "MFR") "Maxim"))
      (libsource (lib "eagle-import") (part "MAX4211"))
    )
    (comp (ref "U11")
      (value "MIC842LYC5")
      (footprint "eagle-import:SC70-5")
      (fields (field (name "MFR") "Microchip") (field (name "MPN") "MIC842LYC5-TR"))
      (libsource (lib "eagle-import") (part "MIC842LYC5"))
    )
    (comp (ref "U12")
      (value "MIC842LYC5")
      (footprint "eagle-import:SC70-5")
      (fields (field (name "MFR") "Microchip") (field (name "MPN") "MIC842LYC5-TR"))
      (libsource (lib "eagle-import") (part "MIC842LYC5"))
    )
    (comp (ref "C1")
      (value "1u")
      (footprint "eagle-import:.0603-C-NOSILK")
      (fields (field (name "MFR") "Yageo") (field (name "MPN") "CC0603KRX7R7BB105"))
      (libsource (lib "eagle-import") (part "C-EU0603-C-NOSILK"))
    )
    (comp (ref "C2")
      (value "1u")
      (footprint "eagle-import:.0603-C-NOSILK")
      (fields (field (name "MFR") "Yageo") (field (name "MPN") "CC0603KRX7R7BB105"))
      (libsource (lib "eagle-import") (part "C-EU0603-C-NOSILK"))
    )
    (comp (ref "C3")
      (value "1u")
      (footprint "eagle-import:.0603-C-NOSILK")
      (fields (field (name "MFR") "Yageo") (field (name "MPN") "CC0603KRX7R7BB105"))
      (libsource (lib "eagle-import") (part "C-EU0603-C-NOSILK"))
    )
    (comp (ref "C4")
      (value "1u")
      (footprint "eagle-import:.0603-C-NOSILK")
      (fields (field (name "MFR") "Yageo") (field (name "MPN") "CC0603KRX7R7BB105"))
      (libsource (lib "eagle-import") (part "C-EU0603-C-NOSILK"))
    )
    (comp (ref "C16")
      (value "1u")
      (footprint "eagle-import:.0603-C-NOSILK")
      (fields (field (name "MFR") "Yageo") (field (name "MPN") "CC0603KRX7R7BB105"))
      (libsource (lib "eagle-import") (part "C-EU0603-C-NOSILK"))
    )
    (comp (ref "R1")
      (value "10k")
      (footprint "eagle-import:.0603-C-NOSILK")
      (fields (field (name "MFR") "Yageo") (field (name "MPN") "RC0603FR-0710KL"))
      (libsource (lib "eagle-import") (part "R-US_0603-C-NOSILK"))
    )
    (comp (ref "R2")
      (value "23.7k")
      (footprint "eagle-import:.0603-C-NOSILK")
      (fields (field (name "MFR") "Yageo") (field (name "MPN") "RC0603FR-0723K7L"))
      (libsource (lib "eagle-import") (part "R-US_0603-C-NOSILK"))
    )
    (comp (ref "R3")
      (value "10k")
      (footprint "eagle-import:.0603-C-NOSILK")
      (fields (field (name "MFR") "Yageo") (field (name "MPN") "RC0603FR-0710KL"))
      (libsource (lib "eagle-import") (part "R-US_0603-C-NOSILK"))
    )
    (comp (ref "R4")
      (value "10k")
      (footprint "eagle-import:.0603-C-NOSILK")
      (fields (field (name "MFR") "Yageo") (field (name "MPN") "RC0603FR-0710KL"))
      (libsource (lib "eagle-import") (part "R-US_0603-C-NOSILK"))
    )
    (comp (ref "R5")
      (value "10k")
      (footprint "eagle-import:.0603-C-NOSILK")
      (fields (field (name "MFR") "Yageo") (field (name "MPN") "RC0603FR-0710KL"))
      (libsource (lib "eagle-import") (part "R-US_0603-C-NOSILK"))
    )
    (comp (ref "R6")
      (value "10k")
      (footprint "eagle-import:.0603-C-NOSILK")
      (fields (field (name "MFR") "Yageo") (field (name "MPN") "RC0603FR-0710KL"))
      (libsource (lib "eagle-import") (part "R-US_0603-C-NOSILK"))
    )
    (comp (ref "R10")
      (value "10k")
      (footprint "eagle-import:.0603-C-NOSILK")
      (fields (field (name "MFR") "Yageo") (field (name "MPN") "RC0603FR-0710KL"))
      (libsource (lib "eagle-import") (part "R-US_0603-C-NOSILK"))
    )
    (comp (ref "R13")
      (value "10k")
      (footprint "eagle-import:.0603-C-NOSILK")
      (fields (field (name "MFR") "Yageo") (field (name "MPN") "RC0603FR-0710KL"))
      (libsource (lib "eagle-import") (part "R-US_0603-C-NOSILK"))
    )
    (comp (ref "TP1")
      (value "TEST-POINT-LARGE-SQUARE")
      (footprint "eagle-import:1X01")
      (libsource (lib "eagle-import") (part "TEST-POINT-LARGE-SQUARE"))
    )
    (comp (ref "TP3")
      (value "TEST-POINT-LARGE-SQUARE")
      (footprint "eagle-import:1X01")
      (libsource (lib "eagle-import") (part "TEST-POINT-LARGE-SQUARE"))
    )
    (comp (ref "TP5")
      (value "TEST-POINT-LARGE-SQUARE")
      (footprint "eagle-import:1X01")
      (libsource (lib "eagle-import") (part "TEST-POINT-LARGE-SQUARE"))
    )
    (comp (ref "TP6")
      (value "TEST-POINT-LARGE-SQUARE")
      (footprint "eagle-import:1X01")
      (libsource (lib "eagle-import") (part "TEST-POINT-LARGE-SQUARE"))
    )
    (comp (ref "TP7")
      (value "TEST-POINT-LARGE-SQUARE")
      (footprint "eagle-import:1X01")
      (libsource (lib "eagle-import") (part "TEST-POINT-LARGE-SQUARE"))
    )
    (comp (ref "TP8")
      (value "TEST-POINT-LARGE-SQUARE")
      (footprint "eagle-import:1X01")
      (libsource (lib "eagle-import") (part "TEST-POINT-LARGE-SQUARE"))
    )
    (comp (ref "TP18")
      (value "TEST-POINT-LARGE-SQUARE")
      (footprint "eagle-import:1X01")
      (libsource (lib "eagle-import") (part "TEST-POINT-LARGE-SQUARE"))
    )
    (comp (ref "U1")
      (value "MAX892LEUA+T21-0036K-L")
      (footprint "eagle-import:21-0036K-L")
      (fields
        (field (name "MANUFACTURER_PART_NUMBER") "MAX892LEUA+T")
        (field (name "MFR") "Maxim")
        (field (name "MPN") "MAX892LEUA+")
      )
      (libsource (lib "eagle-import") (part "MAX892LEUA+T21-0036K-L"))
    )
    (comp (ref "U2")
      (value "LTC4300A-1")
      (footprint "eagle-import:MS8")
      (fields (field (name "MFR") "Linear") (field (name "MPN") "LTC4300A-1IMS8#TRPBF"))
      (libsource (lib "eagle-import") (part "LTC4300A-1"))
    )
    (comp (ref "U13")
      (value "BMI088")
      (footprint "eagle-import:PQFN50P450X300X100-16N")
      (fields (field (name "MF") "Bosch Sensortec"))
      (libsource (lib "eagle-import") (part "BMI088"))
    )
    (comp (ref "C43")
      (value "100n")
      (footprint "eagle-import:.0603-C-NOSILK")
      (fields (field (name "MFR") "Samsung") (field (name "MPN") "CL10B104KB8NNNL"))
      (libsource (lib "eagle-import") (part "C-EU0603-C-NOSILK"))
    )
    (comp (ref "C44")
      (value "1u")
      (footprint "eagle-import:.0603-C-NOSILK")
      (libsource (lib "eagle-import") (part "C-EU0603-C-NOSILK"))
    )
    (comp (ref "C45")
      (value "10u")
      (footprint "eagle-import:.0805-B-NOSILK")
      (fields (field (name "MFR") "Samsung") (field (name "MPN") "CL21B106KOQNNNG"))
      (libsource (lib "eagle-import") (part "C-EU0805-B-NOSILK"))
    )
    (comp (ref "C46")
      (value "1u")
      (footprint "eagle-import:.0603-C-NOSILK")
      (fields (field (name "MFR") "Yageo") (field (name "MPN") "CC0603KRX7R7BB105"))
      (libsource (lib "eagle-import") (part "C-EU0603-C-NOSILK"))
    )
    (comp (ref "C47")
      (value "22u")
      (footprint "eagle-import:.0805-B-NOSILK")
      (fields (field (name "MFR") "Murata") (field (name "MPN") "GRM21BD71A226ME44L"))
      (libsource (lib "eagle-import") (part "C-EU0805-B-NOSILK"))
    )
    (comp (ref "C48")
      (value "1u")
      (footprint "eagle-import:.0603-C-NOSILK")
      (fields (field (name "MFR") "Yageo") (field (name "MPN") "CC0603KRX7R7BB105"))
      (libsource (lib "eagle-import") (part "C-EU0603-C-NOSILK"))
    )
    (comp (ref "C49")
      (value "1u")
      (footprint "eagle-import:.0603-C-NOSILK")
      (fields (field (name "MFR") "Yageo") (field (name "MPN") "CC0603KRX7R7BB105"))
      (libsource (lib "eagle-import") (part "C-EU0603-C-NOSILK"))
    )
    (comp (ref "C50")
      (value "1u")
      (footprint "eagle-import:.0603-C-NOSILK")
      (fields (field (name "MFR") "Yageo") (field (name "MPN") "CC0603KRX7R7BB105"))
      (libsource (lib "eagle-import") (part "C-EU0603-C-NOSILK"))
    )
    (comp (ref "D16")
      (value "GREEN")
      (footprint "eagle-import:LED-0603")
      (fields (field (name "MFR") "Rohm") (field (name "MPN") "SML-E12M8WT86"))
      (libsource (lib "eagle-import") (part "LED-GREEN0603"))
    )
    (comp (ref "D17")
      (value "GREEN")
      (footprint "eagle-import:LED-0603")
      (fields (field (name "MFR") "Rohm") (field (name "MPN") "SML-E12M8WT86"))
      (libsource (lib "eagle-import") (part "LED-GREEN0603"))
    )
    (comp (ref "D18")
      (value "AMBER")
      (footprint "eagle-import:LED-0603")
      (fields (field (name "MFR") "Inolux") (field (name "MPN") "IN-S63AT5A"))
      (libsource (lib "eagle-import") (part "LED-GREEN0603"))
    )
    (comp (ref "L3")
      (value "6.8u")
      (footprint "eagle-import:ECS-MPI4040")
      (fields (field (name "MFR") "ECS") (field (name "MPN") "ECS-MPI4040R4-6R8-R"))
      (libsource (lib "eagle-import") (part "L-ECS-MPI4040"))
    )
    (comp (ref "Q26")
      (value "MOSFET-PCH-SOT23-6")
      (footprint "eagle-import:SOT23-6")
      (fields (field (name "MFR") "Diodes Inc") (field (name "MPN") "DMP3050LVT-7"))
      (libsource (lib "eagle-import") (part "MOSFET-PCH-SOT23-6"))
    )
    (comp (ref "Q27")
      (value "MOSFET-PCH-SOT23-6")
      (footprint "eagle-import:SOT23-6")
      (fields (field (name "MFR") "Diodes Inc") (field (name "MPN") "DMP3050LVT-7"))
      (libsource (lib "eagle-import") (part "MOSFET-PCH-SOT23-6"))
    )
    (comp (ref "Q28")
      (value "PMV45EN")
      (footprint "eagle-import:SOT23")
      (fields (field (name "MFR") "Nexperia") (field (name "MPN") "PMV45EN2R"))
      (libsource (lib "eagle-import") (part "PMV45EN"))
    )
    (comp (ref "Q29")
      (value "PMV45EN")
      (footprint "eagle-import:SOT23")
      (fields (field (name "MFR") "Nexperia") (field (name "MPN") "PMV45EN2R"))
      (libsource (lib "eagle-import") (part "PMV45EN"))
    )
    (comp (ref "Q30")
      (value "DMP2240UDM")
      (footprint "eagle-import:SOT23-6")
      (fields
        (field (name "DIS") "Digi-Key")
        (field (name "DPN") "DMP2240UDMDICT-ND")
        (field (name "MFR") "Diodes Inc")
        (field (name "MPN") "DMP2240UDM")
      )
      (libsource (lib "eagle-import") (part "Q-MOSFET-PCH-dual-SOT23-6_MOSFET-PCH-SOT23-6"))
    )
    (comp (ref "R198")
      (value "2.7k")
      (footprint "eagle-import:.0603-C-NOSILK")
      (fields (field (name "MFR") "TE Connectivity") (field (name "MPN") "CRGCQ0603F2K7"))
      (libsource (lib "eagle-import") (part "R-US_0603-C-NOSILK"))
    )
    (comp (ref "R199")
      (value "2.7k")
      (footprint "eagle-import:.0603-C-NOSILK")
      (fields (field (name "MFR") "TE Connectivity") (field (name "MPN") "CRGCQ0603F2K7"))
      (libsource (lib "eagle-import") (part "R-US_0603-C-NOSILK"))
    )
    (comp (ref "R200")
      (value "10")
      (footprint "eagle-import:.0603-C-NOSILK")
      (fields (field (name "MFR") "Yageo") (field (name "MPN") "RC0603FR-0710RL"))
      (libsource (lib "eagle-import") (part "R-US_0603-C-NOSILK"))
    )
    (comp (ref "R201")
      (value "NP")
      (footprint "eagle-import:.0603-C-NOSILK")
      (fields (field (name "MFR") "Samsung") (field (name "MPN") "RC1005F6653CS"))
      (libsource (lib "eagle-import") (part "R-US_0603-C-NOSILK"))
    )
    (comp (ref "R202")
      (value "NP")
      (footprint "eagle-import:.0603-C-NOSILK")
      (fields (field (name "MFR") "Samsung") (field (name "MPN") "RC1005F6653CS"))
      (libsource (lib "eagle-import") (part "R-US_0603-C-NOSILK"))
    )
    (comp (ref "R203")
      (value "NP")
      (footprint "eagle-import:.0603-C-NOSILK")
      (fields (field (name "MFR") "Samsung") (field (name "MPN") "RC1005F6653CS"))
      (libsource (lib "eagle-import") (part "R-US_0603-C-NOSILK"))
    )
    (comp (ref "R204")
      (value "NP")
      (footprint "eagle-import:.0603-C-NOSILK")
      (fields (field (name "MFR") "Samsung") (field (name "MPN") "RC1005F6653CS"))
      (libsource (lib "eagle-import") (part "R-US_0603-C-NOSILK"))
    )
    (comp (ref "R205")
      (value "NP")
      (footprint "eagle-import:.0603-C-NOSILK")
      (fields (field (name "MFR") "Samsung") (field (name "MPN") "RC1005F6653CS"))
      (libsource (lib "eagle-import") (part "R-US_0603-C-NOSILK"))
    )
    (comp (ref "R206")
      (value "NP")
      (footprint "eagle-import:.0603-C-NOSILK")
      (fields (field (name "MFR") "Samsung") (field (name "MPN") "RC1005F6653CS"))
      (libsource (lib "eagle-import") (part "R-US_0603-C-NOSILK"))
    )
    (comp (ref "R207")
      (value "NP")
      (footprint "eagle-import:.0603-C-NOSILK")
      (fields (field (name "MFR") "Samsung") (field (name "MPN") "RC1005F6653CS"))
      (libsource (lib "eagle-import") (part "R-US_0603-C-NOSILK"))
    )
    (comp (ref "R208")
      (value "NP")
      (footprint "eagle-import:.0603-C-NOSILK")
      (fields (field (name "MFR") "Samsung") (field (name "MPN") "RC1005F6653CS"))
      (libsource (lib "eagle-import") (part "R-US_0603-C-NOSILK"))
    )
    (comp (ref "R209")
      (value "NP")
      (footprint "eagle-import:.0603-C-NOSILK")
      (fields (field (name "MFR") "Samsung") (field (name "MPN") "RC1005F6653CS"))
      (libsource (lib "eagle-import") (part "R-US_0603-C-NOSILK"))
    )
    (comp (ref "R210")
      (value "NP")
      (footprint "eagle-import:.0603-C-NOSILK")
      (fields (field (name "MFR") "Samsung") (field (name "MPN") "RC1005F6653CS"))
      (libsource (lib "eagle-import") (part "R-US_0603-C-NOSILK"))
    )
    (comp (ref "R211")
      (value "NP")
      (footprint "eagle-import:.0603-C-NOSILK")
      (fields (field (name "MFR") "Samsung") (field (name "MPN") "RC1005F6653CS"))
      (libsource (lib "eagle-import") (part "R-US_0603-C-NOSILK"))
    )
    (comp (ref "R212")
      (value "NP")
      (footprint "eagle-import:.0603-C-NOSILK")
      (fields (field (name "MFR") "Samsung") (field (name "MPN") "RC1005F6653CS"))
      (libsource (lib "eagle-import") (part "R-US_0603-C-NOSILK"))
    )
    (comp (ref "R213")
      (value "100")
      (footprint "eagle-import:.0603-C-NOSILK")
      (fields (field (name "MFR") "Yageo") (field (name "MPN") "RC0603FR-07100RL"))
      (libsource (lib "eagle-import") (part "R-US_0603-C-NOSILK"))
    )
    (comp (ref "R214")
      (value "10k")
      (footprint "eagle-import:.0603-C-NOSILK")
      (fields (field (name "MFR") "Yageo") (field (name "MPN") "RC0603FR-0710KL"))
      (libsource (lib "eagle-import") (part "R-US_0603-C-NOSILK"))
    )
    (comp (ref "R215")
      (value "10k")
      (footprint "eagle-import:.0603-C-NOSILK")
      (fields (field (name "MFR") "Yageo") (field (name "MPN") "RC0603FR-0710KL"))
      (libsource (lib "eagle-import") (part "R-US_0603-C-NOSILK"))
    )
    (comp (ref "R216")
      (value "10k")
      (footprint "eagle-import:.0603-C-NOSILK")
      (fields (field (name "MFR") "Yageo") (field (name "MPN") "RC0603FR-0710KL"))
      (libsource (lib "eagle-import") (part "R-US_0603-C-NOSILK"))
    )
    (comp (ref "R217")
      (value "100m")
      (footprint "eagle-import:R1206")
      (fields (field (name "MFR") "Stackpole") (field (name "MPN") "CSR1206FTR100"))
      (libsource (lib "eagle-import") (part "rcl_334_R-US_R1206"))
    )
    (comp (ref "R218")
      (value "10k")
      (footprint "eagle-import:.0603-C-NOSILK")
      (fields (field (name "MFR") "Yageo") (field (name "MPN") "RC0603FR-0710KL"))
      (libsource (lib "eagle-import") (part "R-US_0603-C-NOSILK"))
    )
    (comp (ref "R219")
      (value "0")
      (footprint "eagle-import:.0603-C-NOSILK")
      (fields (field (name "MFR") "Yageo") (field (name "MPN") "RC0603JR-070RL"))
      (libsource (lib "eagle-import") (part "R-US_0603-C-NOSILK"))
    )
    (comp (ref "R220")
      (value "NP")
      (footprint "eagle-import:.0603-C-NOSILK")
      (fields (field (name "MFR") "Samsung") (field (name "MPN") "RC1005F6653CS"))
      (libsource (lib "eagle-import") (part "R-US_0603-C-NOSILK"))
    )
    (comp (ref "R221")
      (value "0")
      (footprint "eagle-import:.0603-C-NOSILK")
      (fields (field (name "MFR") "Yageo") (field (name "MPN") "RC0603JR-070RL"))
      (libsource (lib "eagle-import") (part "R-US_0603-C-NOSILK"))
    )
    (comp (ref "R222")
      (value "NP")
      (footprint "eagle-import:.0603-C-NOSILK")
      (fields (field (name "MFR") "Samsung") (field (name "MPN") "RC1005F6653CS"))
      (libsource (lib "eagle-import") (part "R-US_0603-C-NOSILK"))
    )
    (comp (ref "R223")
      (value "10k")
      (footprint "eagle-import:.0603-C-NOSILK")
      (fields (field (name "MFR") "Yageo") (field (name "MPN") "RC0603FR-0710KL"))
      (libsource (lib "eagle-import") (part "R-US_0603-C-NOSILK"))
    )
    (comp (ref "R224")
      (value "100k")
      (footprint "eagle-import:.0603-C-NOSILK")
      (fields (field (name "MFR") "Samsung") (field (name "MPN") "RC1005F6653CS"))
      (libsource (lib "eagle-import") (part "R-US_0603-C-NOSILK"))
    )
    (comp (ref "R225")
      (value "10k")
      (footprint "eagle-import:.0603-C-NOSILK")
      (fields (field (name "MFR") "Samsung") (field (name "MPN") "RC1005F6653CS"))
      (libsource (lib "eagle-import") (part "R-US_0603-C-NOSILK"))
    )
    (comp (ref "R226")
      (value "10k")
      (footprint "eagle-import:.0603-C-NOSILK")
      (fields (field (name "MFR") "Yageo") (field (name "MPN") "RC0603FR-0710KL"))
      (libsource (lib "eagle-import") (part "R-US_0603-C-NOSILK"))
    )
    (comp (ref "R227")
      (value "10k")
      (footprint "eagle-import:.0603-C-NOSILK")
      (fields (field (name "MFR") "Yageo") (field (name "MPN") "RC0603FR-0710KL"))
      (libsource (lib "eagle-import") (part "R-US_0603-C-NOSILK"))
    )
    (comp (ref "R228")
      (value "NP")
      (footprint "eagle-import:.0603-C-NOSILK")
      (fields (field (name "MFR") "Samsung") (field (name "MPN") "RC1005F6653CS"))
      (libsource (lib "eagle-import") (part "R-US_0603-C-NOSILK"))
    )
    (comp (ref "R267")
      (value "2.7k")
      (footprint "eagle-import:.0603-C-NOSILK")
      (fields (field (name "MFR") "TE Connectivity") (field (name "MPN") "CRGCQ0603F2K7"))
      (libsource (lib "eagle-import") (part "R-US_0603-C-NOSILK"))
    )
    (comp (ref "R268")
      (value "665k")
      (footprint "eagle-import:.0603-C-NOSILK")
      (fields (field (name "MFR") "Yageo") (field (name "MPN") "RC0603FR-07665KL"))
      (libsource (lib "eagle-import") (part "R-US_0603-C-NOSILK"))
    )
    (comp (ref "R269")
      (value "330k")
      (footprint "eagle-import:.0603-C-NOSILK")
      (fields (field (name "MFR") "Vishay") (field (name "MPN") "MCT06030C3303FP000"))
      (libsource (lib "eagle-import") (part "R-US_0603-C-NOSILK"))
    )
    (comp (ref "R270")
      (value "1M")
      (footprint "eagle-import:.0603-C-NOSILK")
      (fields (field (name "MFR") "Yageo") (field (name "MPN") "RC0603FR-071ML"))
      (libsource (lib "eagle-import") (part "R-US_0603-C-NOSILK"))
    )
    (comp (ref "R271")
      (value "100")
      (footprint "eagle-import:.0603-C-NOSILK")
      (fields (field (name "MFR") "Yageo") (field (name "MPN") "RC0603FR-07100RL"))
      (libsource (lib "eagle-import") (part "R-US_0603-C-NOSILK"))
    )
    (comp (ref "R272")
      (value "665k")
      (footprint "eagle-import:.0603-C-NOSILK")
      (fields (field (name "MFR") "Yageo") (field (name "MPN") "RC0603FR-07665KL"))
      (libsource (lib "eagle-import") (part "R-US_0603-C-NOSILK"))
    )
    (comp (ref "R273")
      (value "330k")
      (footprint "eagle-import:.0603-C-NOSILK")
      (fields (field (name "MFR") "Vishay") (field (name "MPN") "MCT06030C3303FP000"))
      (libsource (lib "eagle-import") (part "R-US_0603-C-NOSILK"))
    )
    (comp (ref "R274")
      (value "1M")
      (footprint "eagle-import:.0603-C-NOSILK")
      (fields (field (name "MFR") "Yageo") (field (name "MPN") "RC0603FR-071ML"))
      (libsource (lib "eagle-import") (part "R-US_0603-C-NOSILK"))
    )
    (comp (ref "TP89")
      (value "TEST-POINT-LARGE-SQUARE")
      (footprint "eagle-import:1X01")
      (libsource (lib "eagle-import") (part "TEST-POINT-LARGE-SQUARE"))
    )
    (comp (ref "TP90")
      (value "TEST-POINT-LARGE-SQUARE")
      (footprint "eagle-import:1X01")
      (libsource (lib "eagle-import") (part "TEST-POINT-LARGE-SQUARE"))
    )
    (comp (ref "TP106")
      (value "TEST-POINT-LARGE-SQUARE")
      (footprint "eagle-import:1X01")
      (libsource (lib "eagle-import") (part "TEST-POINT-LARGE-SQUARE"))
    )
    (comp (ref "TP107")
      (value "TEST-POINT-LARGE-SQUARE")
      (footprint "eagle-import:1X01")
      (libsource (lib "eagle-import") (part "TEST-POINT-LARGE-SQUARE"))
    )
    (comp (ref "TP108")
      (value "TEST-POINT-LARGE-SQUARE")
      (footprint "eagle-import:1X01")
      (libsource (lib "eagle-import") (part "TEST-POINT-LARGE-SQUARE"))
    )
    (comp (ref "TP109")
      (value "TEST-POINT-LARGE-SQUARE")
      (footprint "eagle-import:1X01")
      (libsource (lib "eagle-import") (part "TEST-POINT-LARGE-SQUARE"))
    )
    (comp (ref "TP110")
      (value "TEST-POINT-LARGE-SQUARE")
      (footprint "eagle-import:1X01")
      (libsource (lib "eagle-import") (part "TEST-POINT-LARGE-SQUARE"))
    )
    (comp (ref "TP111")
      (value "TEST-POINT-LARGE-SQUARE")
      (footprint "eagle-import:1X01")
      (libsource (lib "eagle-import") (part "TEST-POINT-LARGE-SQUARE"))
    )
    (comp (ref "TP112")
      (value "TEST-POINT-LARGE-SQUARE")
      (footprint "eagle-import:1X01")
      (libsource (lib "eagle-import") (part "TEST-POINT-LARGE-SQUARE"))
    )
    (comp (ref "TP113")
      (value "TEST-POINT-LARGE-SQUARE")
      (footprint "eagle-import:1X01")
      (libsource (lib "eagle-import") (part "TEST-POINT-LARGE-SQUARE"))
    )
    (comp (ref "TP114")
      (value "TEST-POINT-LARGE-SQUARE")
      (footprint "eagle-import:1X01")
      (libsource (lib "eagle-import") (part "TEST-POINT-LARGE-SQUARE"))
    )
    (comp (ref "TP115")
      (value "TEST-POINT-LARGE-SQUARE")
      (footprint "eagle-import:1X01")
      (libsource (lib "eagle-import") (part "TEST-POINT-LARGE-SQUARE"))
    )
    (comp (ref "TP116")
      (value "TEST-POINT-LARGE-SQUARE")
      (footprint "eagle-import:1X01")
      (libsource (lib "eagle-import") (part "TEST-POINT-LARGE-SQUARE"))
    )
    (comp (ref "TP117")
      (value "TEST-POINT-LARGE-SQUARE")
      (footprint "eagle-import:1X01")
      (libsource (lib "eagle-import") (part "TEST-POINT-LARGE-SQUARE"))
    )
    (comp (ref "TP118")
      (value "TEST-POINT-LARGE-SQUARE")
      (footprint "eagle-import:1X01")
      (libsource (lib "eagle-import") (part "TEST-POINT-LARGE-SQUARE"))
    )
    (comp (ref "TP119")
      (value "TEST-POINT-LARGE-SQUARE")
      (footprint "eagle-import:1X01")
      (libsource (lib "eagle-import") (part "TEST-POINT-LARGE-SQUARE"))
    )
    (comp (ref "TP120")
      (value "TEST-POINT-LARGE-SQUARE")
      (footprint "eagle-import:1X01")
      (libsource (lib "eagle-import") (part "TEST-POINT-LARGE-SQUARE"))
    )
    (comp (ref "TP121")
      (value "TEST-POINT-LARGE-SQUARE")
      (footprint "eagle-import:1X01")
      (libsource (lib "eagle-import") (part "TEST-POINT-LARGE-SQUARE"))
    )
    (comp (ref "U29")
      (value "MAX7310ATE")
      (footprint "eagle-import:QFN65P400X400X80-17T210")
      (fields (field (name "MFR") "Maxim"))
      (libsource (lib "eagle-import") (part "MAX7310"))
    )
    (comp (ref "U30")
      (value "MAX4211FETE")
      (footprint "eagle-import:QFN65P400X400X80-17T210")
      (fields (field (name "MFR") "Maxim"))
      (libsource (lib "eagle-import") (part "MAX4211"))
    )
    (comp (ref "U31")
      (value "TPS62111RSA")
      (footprint "eagle-import:S-PVQFN-16")
      (fields (field (name "MFR") "Texas Instruments"))
      (libsource (lib "eagle-import") (part "TPS6211X"))
    )
    (comp (ref "U32")
      (value "MIC842LYC5")
      (footprint "eagle-import:SC70-5")
      (fields (field (name "MFR") "Microchip") (field (name "MPN") "MIC842LYC5-TR"))
      (libsource (lib "eagle-import") (part "MIC842LYC5"))
    )
    (comp (ref "U33")
      (value "MIC842LYC5")
      (footprint "eagle-import:SC70-5")
      (fields (field (name "MFR") "Microchip") (field (name "MPN") "MIC842LYC5-TR"))
      (libsource (lib "eagle-import") (part "MIC842LYC5"))
    )
    (comp (ref "C21")
      (value "100n")
      (footprint "eagle-import:.0603-C-NOSILK")
      (fields (field (name "MFR") "Samsung") (field (name "MPN") "CL10B104KB8NNNL"))
      (libsource (lib "eagle-import") (part "C-EU0603-C-NOSILK"))
    )
    (comp (ref "C22")
      (value "1u")
      (footprint "eagle-import:.0603-C-NOSILK")
      (libsource (lib "eagle-import") (part "C-EU0603-C-NOSILK"))
    )
    (comp (ref "C23")
      (value "1u")
      (footprint "eagle-import:.0603-C-NOSILK")
      (fields (field (name "MFR") "Yageo") (field (name "MPN") "CC0603KRX7R7BB105"))
      (libsource (lib "eagle-import") (part "C-EU0603-C-NOSILK"))
    )
    (comp (ref "C24")
      (value "1u")
      (footprint "eagle-import:.0603-C-NOSILK")
      (fields (field (name "MFR") "Yageo") (field (name "MPN") "CC0603KRX7R7BB105"))
      (libsource (lib "eagle-import") (part "C-EU0603-C-NOSILK"))
    )
    (comp (ref "C25")
      (value "1u")
      (footprint "eagle-import:.0603-C-NOSILK")
      (fields (field (name "MFR") "Yageo") (field (name "MPN") "CC0603KRX7R7BB105"))
      (libsource (lib "eagle-import") (part "C-EU0603-C-NOSILK"))
    )
    (comp (ref "D9")
      (value "GREEN")
      (footprint "eagle-import:LED-0603")
      (fields (field (name "MFR") "Rohm") (field (name "MPN") "SML-E12M8WT86"))
      (libsource (lib "eagle-import") (part "LED-GREEN0603"))
    )
    (comp (ref "D10")
      (value "AMBER")
      (footprint "eagle-import:LED-0603")
      (fields (field (name "MFR") "Inolux") (field (name "MPN") "IN-S63AT5A"))
      (libsource (lib "eagle-import") (part "LED-GREEN0603"))
    )
    (comp (ref "Q21")
      (value "MOSFET-PCH-SOT23-6")
      (footprint "eagle-import:SOT23-6")
      (fields (field (name "MFR") "Diodes Inc") (field (name "MPN") "DMP3050LVT-7"))
      (libsource (lib "eagle-import") (part "MOSFET-PCH-SOT23-6"))
    )
    (comp (ref "Q22")
      (value "MOSFET-PCH-SOT23-6")
      (footprint "eagle-import:SOT23-6")
      (fields (field (name "MFR") "Diodes Inc") (field (name "MPN") "DMP3050LVT-7"))
      (libsource (lib "eagle-import") (part "MOSFET-PCH-SOT23-6"))
    )
    (comp (ref "Q23")
      (value "PMV45EN")
      (footprint "eagle-import:SOT23")
      (fields (field (name "MFR") "Nexperia") (field (name "MPN") "PMV45EN2R"))
      (libsource (lib "eagle-import") (part "PMV45EN"))
    )
    (comp (ref "Q24")
      (value "PMV45EN")
      (footprint "eagle-import:SOT23")
      (fields (field (name "MFR") "Nexperia") (field (name "MPN") "PMV45EN2R"))
      (libsource (lib "eagle-import") (part "PMV45EN"))
    )
    (comp (ref "Q25")
      (value "DMP2240UDM")
      (footprint "eagle-import:SOT23-6")
      (fields
        (field (name "DIS") "Digi-Key")
        (field (name "DPN") "DMP2240UDMDICT-ND")
        (field (name "MFR") "Diodes Inc")
        (field (name "MPN") "DMP2240UDM")
      )
      (libsource (lib "eagle-import") (part "Q-MOSFET-PCH-dual-SOT23-6_MOSFET-PCH-SOT23-6"))
    )
    (comp (ref "R153")
      (value "2.7k")
      (footprint "eagle-import:.0603-C-NOSILK")
      (fields (field (name "MFR") "TE Connectivity") (field (name "MPN") "CRGCQ0603F2K7"))
      (libsource (lib "eagle-import") (part "R-US_0603-C-NOSILK"))
    )
    (comp (ref "R154")
      (value "10")
      (footprint "eagle-import:.0603-C-NOSILK")
      (fields (field (name "MFR") "Yageo") (field (name "MPN") "RC0603FR-0710RL"))
      (libsource (lib "eagle-import") (part "R-US_0603-C-NOSILK"))
    )
    (comp (ref "R155")
      (value "NP")
      (footprint "eagle-import:.0603-C-NOSILK")
      (fields (field (name "MFR") "Samsung") (field (name "MPN") "RC1005F6653CS"))
      (libsource (lib "eagle-import") (part "R-US_0603-C-NOSILK"))
    )
    (comp (ref "R156")
      (value "NP")
      (footprint "eagle-import:.0603-C-NOSILK")
      (fields (field (name "MFR") "Samsung") (field (name "MPN") "RC1005F6653CS"))
      (libsource (lib "eagle-import") (part "R-US_0603-C-NOSILK"))
    )
    (comp (ref "R157")
      (value "NP")
      (footprint "eagle-import:.0603-C-NOSILK")
      (fields (field (name "MFR") "Samsung") (field (name "MPN") "RC1005F6653CS"))
      (libsource (lib "eagle-import") (part "R-US_0603-C-NOSILK"))
    )
    (comp (ref "R158")
      (value "NP")
      (footprint "eagle-import:.0603-C-NOSILK")
      (fields (field (name "MFR") "Samsung") (field (name "MPN") "RC1005F6653CS"))
      (libsource (lib "eagle-import") (part "R-US_0603-C-NOSILK"))
    )
    (comp (ref "R159")
      (value "NP")
      (footprint "eagle-import:.0603-C-NOSILK")
      (fields (field (name "MFR") "Samsung") (field (name "MPN") "RC1005F6653CS"))
      (libsource (lib "eagle-import") (part "R-US_0603-C-NOSILK"))
    )
    (comp (ref "R160")
      (value "NP")
      (footprint "eagle-import:.0603-C-NOSILK")
      (fields (field (name "MFR") "Samsung") (field (name "MPN") "RC1005F6653CS"))
      (libsource (lib "eagle-import") (part "R-US_0603-C-NOSILK"))
    )
    (comp (ref "R161")
      (value "NP")
      (footprint "eagle-import:.0603-C-NOSILK")
      (fields (field (name "MFR") "Samsung") (field (name "MPN") "RC1005F6653CS"))
      (libsource (lib "eagle-import") (part "R-US_0603-C-NOSILK"))
    )
    (comp (ref "R162")
      (value "NP")
      (footprint "eagle-import:.0603-C-NOSILK")
      (fields (field (name "MFR") "Samsung") (field (name "MPN") "RC1005F6653CS"))
      (libsource (lib "eagle-import") (part "R-US_0603-C-NOSILK"))
    )
    (comp (ref "R163")
      (value "NP")
      (footprint "eagle-import:.0603-C-NOSILK")
      (fields (field (name "MFR") "Samsung") (field (name "MPN") "RC1005F6653CS"))
      (libsource (lib "eagle-import") (part "R-US_0603-C-NOSILK"))
    )
    (comp (ref "R164")
      (value "NP")
      (footprint "eagle-import:.0603-C-NOSILK")
      (fields (field (name "MFR") "Samsung") (field (name "MPN") "RC1005F6653CS"))
      (libsource (lib "eagle-import") (part "R-US_0603-C-NOSILK"))
    )
    (comp (ref "R165")
      (value "NP")
      (footprint "eagle-import:.0603-C-NOSILK")
      (fields (field (name "MFR") "Samsung") (field (name "MPN") "RC1005F6653CS"))
      (libsource (lib "eagle-import") (part "R-US_0603-C-NOSILK"))
    )
    (comp (ref "R166")
      (value "NP")
      (footprint "eagle-import:.0603-C-NOSILK")
      (fields (field (name "MFR") "Samsung") (field (name "MPN") "RC1005F6653CS"))
      (libsource (lib "eagle-import") (part "R-US_0603-C-NOSILK"))
    )
    (comp (ref "R167")
      (value "100")
      (footprint "eagle-import:.0603-C-NOSILK")
      (fields (field (name "MFR") "Yageo") (field (name "MPN") "RC0603FR-07100RL"))
      (libsource (lib "eagle-import") (part "R-US_0603-C-NOSILK"))
    )
    (comp (ref "R168")
      (value "10k")
      (footprint "eagle-import:.0603-C-NOSILK")
      (fields (field (name "MFR") "Yageo") (field (name "MPN") "RC0603FR-0710KL"))
      (libsource (lib "eagle-import") (part "R-US_0603-C-NOSILK"))
    )
    (comp (ref "R169")
      (value "10k")
      (footprint "eagle-import:.0603-C-NOSILK")
      (fields (field (name "MFR") "Yageo") (field (name "MPN") "RC0603FR-0710KL"))
      (libsource (lib "eagle-import") (part "R-US_0603-C-NOSILK"))
    )
    (comp (ref "R170")
      (value "10k")
      (footprint "eagle-import:.0603-C-NOSILK")
      (fields (field (name "MFR") "Yageo") (field (name "MPN") "RC0603FR-0710KL"))
      (libsource (lib "eagle-import") (part "R-US_0603-C-NOSILK"))
    )
    (comp (ref "R171")
      (value "100m")
      (footprint "eagle-import:R1206")
      (fields (field (name "MFR") "Stackpole") (field (name "MPN") "CSR1206FTR100"))
      (libsource (lib "eagle-import") (part "rcl_334_R-US_R1206"))
    )
    (comp (ref "R172")
      (value "10k")
      (footprint "eagle-import:.0603-C-NOSILK")
      (fields (field (name "MFR") "Yageo") (field (name "MPN") "RC0603FR-0710KL"))
      (libsource (lib "eagle-import") (part "R-US_0603-C-NOSILK"))
    )
    (comp (ref "R173")
      (value "0")
      (footprint "eagle-import:.0603-C-NOSILK")
      (fields (field (name "MFR") "Yageo") (field (name "MPN") "RC0603JR-070RL"))
      (libsource (lib "eagle-import") (part "R-US_0603-C-NOSILK"))
    )
    (comp (ref "R174")
      (value "NP")
      (footprint "eagle-import:.0603-C-NOSILK")
      (fields (field (name "MFR") "Samsung") (field (name "MPN") "RC1005F6653CS"))
      (libsource (lib "eagle-import") (part "R-US_0603-C-NOSILK"))
    )
    (comp (ref "R175")
      (value "0")
      (footprint "eagle-import:.0603-C-NOSILK")
      (fields (field (name "MFR") "Yageo") (field (name "MPN") "RC0603JR-070RL"))
      (libsource (lib "eagle-import") (part "R-US_0603-C-NOSILK"))
    )
    (comp (ref "R176")
      (value "NP")
      (footprint "eagle-import:.0603-C-NOSILK")
      (fields (field (name "MFR") "Samsung") (field (name "MPN") "RC1005F6653CS"))
      (libsource (lib "eagle-import") (part "R-US_0603-C-NOSILK"))
    )
    (comp (ref "R177")
      (value "10k")
      (footprint "eagle-import:.0603-C-NOSILK")
      (fields (field (name "MFR") "Yageo") (field (name "MPN") "RC0603FR-0710KL"))
      (libsource (lib "eagle-import") (part "R-US_0603-C-NOSILK"))
    )
    (comp (ref "R178")
      (value "100k")
      (footprint "eagle-import:.0603-C-NOSILK")
      (fields (field (name "MFR") "Samsung") (field (name "MPN") "RC1005F6653CS"))
      (libsource (lib "eagle-import") (part "R-US_0603-C-NOSILK"))
    )
    (comp (ref "R179")
      (value "10k")
      (footprint "eagle-import:.0603-C-NOSILK")
      (fields (field (name "MFR") "Samsung") (field (name "MPN") "RC1005F6653CS"))
      (libsource (lib "eagle-import") (part "R-US_0603-C-NOSILK"))
    )
    (comp (ref "R180")
      (value "10k")
      (footprint "eagle-import:.0603-C-NOSILK")
      (fields (field (name "MFR") "Yageo") (field (name "MPN") "RC0603FR-0710KL"))
      (libsource (lib "eagle-import") (part "R-US_0603-C-NOSILK"))
    )
    (comp (ref "R181")
      (value "2.7k")
      (footprint "eagle-import:.0603-C-NOSILK")
      (fields (field (name "MFR") "TE Connectivity") (field (name "MPN") "CRGCQ0603F2K7"))
      (libsource (lib "eagle-import") (part "R-US_0603-C-NOSILK"))
    )
    (comp (ref "R182")
      (value "665k")
      (footprint "eagle-import:.0603-C-NOSILK")
      (fields (field (name "MFR") "Yageo") (field (name "MPN") "RC0603FR-07665KL"))
      (libsource (lib "eagle-import") (part "R-US_0603-C-NOSILK"))
    )
    (comp (ref "R183")
      (value "47k")
      (footprint "eagle-import:.0603-C-NOSILK")
      (fields (field (name "MFR") "Yageo") (field (name "MPN") "RC0603FR-0747KL"))
      (libsource (lib "eagle-import") (part "R-US_0603-C-NOSILK"))
    )
    (comp (ref "R184")
      (value "47k")
      (footprint "eagle-import:.0603-C-NOSILK")
      (fields (field (name "MFR") "Yageo") (field (name "MPN") "RC0603FR-0747KL"))
      (libsource (lib "eagle-import") (part "R-US_0603-C-NOSILK"))
    )
    (comp (ref "R185")
      (value "330k")
      (footprint "eagle-import:.0603-C-NOSILK")
      (fields (field (name "MFR") "Vishay") (field (name "MPN") "MCT06030C3303FP000"))
      (libsource (lib "eagle-import") (part "R-US_0603-C-NOSILK"))
    )
    (comp (ref "R186")
      (value "1M")
      (footprint "eagle-import:.0603-C-NOSILK")
      (fields (field (name "MFR") "Yageo") (field (name "MPN") "RC0603FR-071ML"))
      (libsource (lib "eagle-import") (part "R-US_0603-C-NOSILK"))
    )
    (comp (ref "R187")
      (value "100")
      (footprint "eagle-import:.0603-C-NOSILK")
      (fields (field (name "MFR") "Yageo") (field (name "MPN") "RC0603FR-07100RL"))
      (libsource (lib "eagle-import") (part "R-US_0603-C-NOSILK"))
    )
    (comp (ref "R188")
      (value "665k")
      (footprint "eagle-import:.0603-C-NOSILK")
      (fields (field (name "MFR") "Yageo") (field (name "MPN") "RC0603FR-07665KL"))
      (libsource (lib "eagle-import") (part "R-US_0603-C-NOSILK"))
    )
    (comp (ref "R189")
      (value "330k")
      (footprint "eagle-import:.0603-C-NOSILK")
      (fields (field (name "MFR") "Vishay") (field (name "MPN") "MCT06030C3303FP000"))
      (libsource (lib "eagle-import") (part "R-US_0603-C-NOSILK"))
    )
    (comp (ref "R190")
      (value "1M")
      (footprint "eagle-import:.0603-C-NOSILK")
      (fields (field (name "MFR") "Yageo") (field (name "MPN") "RC0603FR-071ML"))
      (libsource (lib "eagle-import") (part "R-US_0603-C-NOSILK"))
    )
    (comp (ref "TP61")
      (value "TEST-POINT-LARGE-SQUARE")
      (footprint "eagle-import:1X01")
      (libsource (lib "eagle-import") (part "TEST-POINT-LARGE-SQUARE"))
    )
    (comp (ref "TP62")
      (value "TEST-POINT-LARGE-SQUARE")
      (footprint "eagle-import:1X01")
      (libsource (lib "eagle-import") (part "TEST-POINT-LARGE-SQUARE"))
    )
    (comp (ref "TP63")
      (value "TEST-POINT-LARGE-SQUARE")
      (footprint "eagle-import:1X01")
      (libsource (lib "eagle-import") (part "TEST-POINT-LARGE-SQUARE"))
    )
    (comp (ref "TP64")
      (value "TEST-POINT-LARGE-SQUARE")
      (footprint "eagle-import:1X01")
      (libsource (lib "eagle-import") (part "TEST-POINT-LARGE-SQUARE"))
    )
    (comp (ref "TP65")
      (value "TEST-POINT-LARGE-SQUARE")
      (footprint "eagle-import:1X01")
      (libsource (lib "eagle-import") (part "TEST-POINT-LARGE-SQUARE"))
    )
    (comp (ref "TP66")
      (value "TEST-POINT-LARGE-SQUARE")
      (footprint "eagle-import:1X01")
      (libsource (lib "eagle-import") (part "TEST-POINT-LARGE-SQUARE"))
    )
    (comp (ref "TP67")
      (value "TEST-POINT-LARGE-SQUARE")
      (footprint "eagle-import:1X01")
      (libsource (lib "eagle-import") (part "TEST-POINT-LARGE-SQUARE"))
    )
    (comp (ref "TP68")
      (value "TEST-POINT-LARGE-SQUARE")
      (footprint "eagle-import:1X01")
      (libsource (lib "eagle-import") (part "TEST-POINT-LARGE-SQUARE"))
    )
    (comp (ref "TP69")
      (value "TEST-POINT-LARGE-SQUARE")
      (footprint "eagle-import:1X01")
      (libsource (lib "eagle-import") (part "TEST-POINT-LARGE-SQUARE"))
    )
    (comp (ref "TP70")
      (value "TEST-POINT-LARGE-SQUARE")
      (footprint "eagle-import:1X01")
      (libsource (lib "eagle-import") (part "TEST-POINT-LARGE-SQUARE"))
    )
    (comp (ref "TP71")
      (value "TEST-POINT-LARGE-SQUARE")
      (footprint "eagle-import:1X01")
      (libsource (lib "eagle-import") (part "TEST-POINT-LARGE-SQUARE"))
    )
    (comp (ref "TP72")
      (value "TEST-POINT-LARGE-SQUARE")
      (footprint "eagle-import:1X01")
      (libsource (lib "eagle-import") (part "TEST-POINT-LARGE-SQUARE"))
    )
    (comp (ref "TP73")
      (value "TEST-POINT-LARGE-SQUARE")
      (footprint "eagle-import:1X01")
      (libsource (lib "eagle-import") (part "TEST-POINT-LARGE-SQUARE"))
    )
    (comp (ref "TP74")
      (value "TEST-POINT-LARGE-SQUARE")
      (footprint "eagle-import:1X01")
      (libsource (lib "eagle-import") (part "TEST-POINT-LARGE-SQUARE"))
    )
    (comp (ref "TP75")
      (value "TEST-POINT-LARGE-SQUARE")
      (footprint "eagle-import:1X01")
      (libsource (lib "eagle-import") (part "TEST-POINT-LARGE-SQUARE"))
    )
    (comp (ref "U17")
      (value "MAX7310ATE")
      (footprint "eagle-import:QFN65P400X400X80-17T210")
      (fields (field (name "MFR") "Maxim"))
      (libsource (lib "eagle-import") (part "MAX7310"))
    )
    (comp (ref "U18")
      (value "MAX4211FETE")
      (footprint "eagle-import:QFN65P400X400X80-17T210")
      (fields (field (name "MFR") "Maxim"))
      (libsource (lib "eagle-import") (part "MAX4211"))
    )
    (comp (ref "U19")
      (value "MIC842LYC5")
      (footprint "eagle-import:SC70-5")
      (fields (field (name "MFR") "Microchip") (field (name "MPN") "MIC842LYC5-TR"))
      (libsource (lib "eagle-import") (part "MIC842LYC5"))
    )
    (comp (ref "U20")
      (value "MIC842LYC5")
      (footprint "eagle-import:SC70-5")
      (fields (field (name "MFR") "Microchip") (field (name "MPN") "MIC842LYC5-TR"))
      (libsource (lib "eagle-import") (part "MIC842LYC5"))
    )
    (comp (ref "C31")
      (value "100n")
      (footprint "eagle-import:.0603-C-NOSILK")
      (fields (field (name "MFR") "Samsung") (field (name "MPN") "CL10B104KB8NNNL"))
      (libsource (lib "eagle-import") (part "C-EU0603-C-NOSILK"))
    )
    (comp (ref "C32")
      (value "1u")
      (footprint "eagle-import:.0603-C-NOSILK")
      (libsource (lib "eagle-import") (part "C-EU0603-C-NOSILK"))
    )
    (comp (ref "C33")
      (value "1u")
      (footprint "eagle-import:.0603-C-NOSILK")
      (fields (field (name "MFR") "Yageo") (field (name "MPN") "CC0603KRX7R7BB105"))
      (libsource (lib "eagle-import") (part "C-EU0603-C-NOSILK"))
    )
    (comp (ref "C34")
      (value "1u")
      (footprint "eagle-import:.0603-C-NOSILK")
      (fields (field (name "MFR") "Yageo") (field (name "MPN") "CC0603KRX7R7BB105"))
      (libsource (lib "eagle-import") (part "C-EU0603-C-NOSILK"))
    )
    (comp (ref "C35")
      (value "1u")
      (footprint "eagle-import:.0603-C-NOSILK")
      (fields (field (name "MFR") "Yageo") (field (name "MPN") "CC0603KRX7R7BB105"))
      (libsource (lib "eagle-import") (part "C-EU0603-C-NOSILK"))
    )
    (comp (ref "D13")
      (value "GREEN")
      (footprint "eagle-import:LED-0603")
      (fields (field (name "MFR") "Rohm") (field (name "MPN") "SML-E12M8WT86"))
      (libsource (lib "eagle-import") (part "LED-GREEN0603"))
    )
    (comp (ref "D14")
      (value "AMBER")
      (footprint "eagle-import:LED-0603")
      (fields (field (name "MFR") "Inolux") (field (name "MPN") "IN-S63AT5A"))
      (libsource (lib "eagle-import") (part "LED-GREEN0603"))
    )
    (comp (ref "Q31")
      (value "MOSFET-PCH-SOT23-6")
      (footprint "eagle-import:SOT23-6")
      (fields (field (name "MFR") "Diodes Inc") (field (name "MPN") "DMP3050LVT-7"))
      (libsource (lib "eagle-import") (part "MOSFET-PCH-SOT23-6"))
    )
    (comp (ref "Q32")
      (value "MOSFET-PCH-SOT23-6")
      (footprint "eagle-import:SOT23-6")
      (fields (field (name "MFR") "Diodes Inc") (field (name "MPN") "DMP3050LVT-7"))
      (libsource (lib "eagle-import") (part "MOSFET-PCH-SOT23-6"))
    )
    (comp (ref "Q33")
      (value "PMV45EN")
      (footprint "eagle-import:SOT23")
      (fields (field (name "MFR") "Nexperia") (field (name "MPN") "PMV45EN2R"))
      (libsource (lib "eagle-import") (part "PMV45EN"))
    )
    (comp (ref "Q34")
      (value "PMV45EN")
      (footprint "eagle-import:SOT23")
      (fields (field (name "MFR") "Nexperia") (field (name "MPN") "PMV45EN2R"))
      (libsource (lib "eagle-import") (part "PMV45EN"))
    )
    (comp (ref "Q35")
      (value "DMP2240UDM")
      (footprint "eagle-import:SOT23-6")
      (fields
        (field (name "MFR") "Diodes Inc")
        (field (name "MPN") "DMP2240UDM")
        (field (name "DIS") "Digi-Key")
        (field (name "DPN") "DMP2240UDMDICT-ND")
      )
      (libsource (lib "eagle-import") (part "Q-MOSFET-PCH-dual-SOT23-6_MOSFET-PCH-SOT23-6"))
    )
    (comp (ref "R229")
      (value "2.7k")
      (footprint "eagle-import:.0603-C-NOSILK")
      (fields (field (name "MFR") "TE Connectivity") (field (name "MPN") "CRGCQ0603F2K7"))
      (libsource (lib "eagle-import") (part "R-US_0603-C-NOSILK"))
    )
    (comp (ref "R230")
      (value "10")
      (footprint "eagle-import:.0603-C-NOSILK")
      (fields (field (name "MFR") "Yageo") (field (name "MPN") "RC0603FR-0710RL"))
      (libsource (lib "eagle-import") (part "R-US_0603-C-NOSILK"))
    )
    (comp (ref "R231")
      (value "NP")
      (footprint "eagle-import:.0603-C-NOSILK")
      (fields (field (name "MFR") "Samsung") (field (name "MPN") "RC1005F6653CS"))
      (libsource (lib "eagle-import") (part "R-US_0603-C-NOSILK"))
    )
    (comp (ref "R232")
      (value "NP")
      (footprint "eagle-import:.0603-C-NOSILK")
      (fields (field (name "MFR") "Samsung") (field (name "MPN") "RC1005F6653CS"))
      (libsource (lib "eagle-import") (part "R-US_0603-C-NOSILK"))
    )
    (comp (ref "R233")
      (value "NP")
      (footprint "eagle-import:.0603-C-NOSILK")
      (fields (field (name "MFR") "Samsung") (field (name "MPN") "RC1005F6653CS"))
      (libsource (lib "eagle-import") (part "R-US_0603-C-NOSILK"))
    )
    (comp (ref "R234")
      (value "NP")
      (footprint "eagle-import:.0603-C-NOSILK")
      (fields (field (name "MFR") "Samsung") (field (name "MPN") "RC1005F6653CS"))
      (libsource (lib "eagle-import") (part "R-US_0603-C-NOSILK"))
    )
    (comp (ref "R235")
      (value "NP")
      (footprint "eagle-import:.0603-C-NOSILK")
      (fields (field (name "MFR") "Samsung") (field (name "MPN") "RC1005F6653CS"))
      (libsource (lib "eagle-import") (part "R-US_0603-C-NOSILK"))
    )
    (comp (ref "R236")
      (value "NP")
      (footprint "eagle-import:.0603-C-NOSILK")
      (fields (field (name "MFR") "Samsung") (field (name "MPN") "RC1005F6653CS"))
      (libsource (lib "eagle-import") (part "R-US_0603-C-NOSILK"))
    )
    (comp (ref "R237")
      (value "NP")
      (footprint "eagle-import:.0603-C-NOSILK")
      (fields (field (name "MFR") "Samsung") (field (name "MPN") "RC1005F6653CS"))
      (libsource (lib "eagle-import") (part "R-US_0603-C-NOSILK"))
    )
    (comp (ref "R238")
      (value "NP")
      (footprint "eagle-import:.0603-C-NOSILK")
      (fields (field (name "MFR") "Samsung") (field (name "MPN") "RC1005F6653CS"))
      (libsource (lib "eagle-import") (part "R-US_0603-C-NOSILK"))
    )
    (comp (ref "R239")
      (value "NP")
      (footprint "eagle-import:.0603-C-NOSILK")
      (fields (field (name "MFR") "Samsung") (field (name "MPN") "RC1005F6653CS"))
      (libsource (lib "eagle-import") (part "R-US_0603-C-NOSILK"))
    )
    (comp (ref "R240")
      (value "NP")
      (footprint "eagle-import:.0603-C-NOSILK")
      (fields (field (name "MFR") "Samsung") (field (name "MPN") "RC1005F6653CS"))
      (libsource (lib "eagle-import") (part "R-US_0603-C-NOSILK"))
    )
    (comp (ref "R241")
      (value "NP")
      (footprint "eagle-import:.0603-C-NOSILK")
      (fields (field (name "MFR") "Samsung") (field (name "MPN") "RC1005F6653CS"))
      (libsource (lib "eagle-import") (part "R-US_0603-C-NOSILK"))
    )
    (comp (ref "R242")
      (value "NP")
      (footprint "eagle-import:.0603-C-NOSILK")
      (fields (field (name "MFR") "Samsung") (field (name "MPN") "RC1005F6653CS"))
      (libsource (lib "eagle-import") (part "R-US_0603-C-NOSILK"))
    )
    (comp (ref "R243")
      (value "100")
      (footprint "eagle-import:.0603-C-NOSILK")
      (fields (field (name "MFR") "Yageo") (field (name "MPN") "RC0603FR-07100RL"))
      (libsource (lib "eagle-import") (part "R-US_0603-C-NOSILK"))
    )
    (comp (ref "R244")
      (value "10k")
      (footprint "eagle-import:.0603-C-NOSILK")
      (fields (field (name "MFR") "Yageo") (field (name "MPN") "RC0603FR-0710KL"))
      (libsource (lib "eagle-import") (part "R-US_0603-C-NOSILK"))
    )
    (comp (ref "R245")
      (value "10k")
      (footprint "eagle-import:.0603-C-NOSILK")
      (fields (field (name "MFR") "Yageo") (field (name "MPN") "RC0603FR-0710KL"))
      (libsource (lib "eagle-import") (part "R-US_0603-C-NOSILK"))
    )
    (comp (ref "R246")
      (value "10k")
      (footprint "eagle-import:.0603-C-NOSILK")
      (fields (field (name "MFR") "Yageo") (field (name "MPN") "RC0603FR-0710KL"))
      (libsource (lib "eagle-import") (part "R-US_0603-C-NOSILK"))
    )
    (comp (ref "R247")
      (value "100m")
      (footprint "eagle-import:R1206")
      (fields (field (name "MFR") "Stackpole") (field (name "MPN") "CSR1206FTR100"))
      (libsource (lib "eagle-import") (part "rcl_334_R-US_R1206"))
    )
    (comp (ref "R248")
      (value "10k")
      (footprint "eagle-import:.0603-C-NOSILK")
      (fields (field (name "MFR") "Yageo") (field (name "MPN") "RC0603FR-0710KL"))
      (libsource (lib "eagle-import") (part "R-US_0603-C-NOSILK"))
    )
    (comp (ref "R249")
      (value "0")
      (footprint "eagle-import:.0603-C-NOSILK")
      (fields (field (name "MFR") "Yageo") (field (name "MPN") "RC0603JR-070RL"))
      (libsource (lib "eagle-import") (part "R-US_0603-C-NOSILK"))
    )
    (comp (ref "R250")
      (value "NP")
      (footprint "eagle-import:.0603-C-NOSILK")
      (fields (field (name "MFR") "Samsung") (field (name "MPN") "RC1005F6653CS"))
      (libsource (lib "eagle-import") (part "R-US_0603-C-NOSILK"))
    )
    (comp (ref "R251")
      (value "0")
      (footprint "eagle-import:.0603-C-NOSILK")
      (fields (field (name "MFR") "Yageo") (field (name "MPN") "RC0603JR-070RL"))
      (libsource (lib "eagle-import") (part "R-US_0603-C-NOSILK"))
    )
    (comp (ref "R252")
      (value "NP")
      (footprint "eagle-import:.0603-C-NOSILK")
      (fields (field (name "MFR") "Samsung") (field (name "MPN") "RC1005F6653CS"))
      (libsource (lib "eagle-import") (part "R-US_0603-C-NOSILK"))
    )
    (comp (ref "R253")
      (value "10k")
      (footprint "eagle-import:.0603-C-NOSILK")
      (fields (field (name "MFR") "Yageo") (field (name "MPN") "RC0603FR-0710KL"))
      (libsource (lib "eagle-import") (part "R-US_0603-C-NOSILK"))
    )
    (comp (ref "R254")
      (value "100k")
      (footprint "eagle-import:.0603-C-NOSILK")
      (fields (field (name "MFR") "Samsung") (field (name "MPN") "RC1005F6653CS"))
      (libsource (lib "eagle-import") (part "R-US_0603-C-NOSILK"))
    )
    (comp (ref "R255")
      (value "10k")
      (footprint "eagle-import:.0603-C-NOSILK")
      (fields (field (name "MFR") "Samsung") (field (name "MPN") "RC1005F6653CS"))
      (libsource (lib "eagle-import") (part "R-US_0603-C-NOSILK"))
    )
    (comp (ref "R256")
      (value "10k")
      (footprint "eagle-import:.0603-C-NOSILK")
      (fields (field (name "MFR") "Yageo") (field (name "MPN") "RC0603FR-0710KL"))
      (libsource (lib "eagle-import") (part "R-US_0603-C-NOSILK"))
    )
    (comp (ref "R257")
      (value "2.7k")
      (footprint "eagle-import:.0603-C-NOSILK")
      (fields (field (name "MFR") "TE Connectivity") (field (name "MPN") "CRGCQ0603F2K7"))
      (libsource (lib "eagle-import") (part "R-US_0603-C-NOSILK"))
    )
    (comp (ref "R258")
      (value "665k")
      (footprint "eagle-import:.0603-C-NOSILK")
      (fields (field (name "MFR") "Yageo") (field (name "MPN") "RC0603FR-07665KL"))
      (libsource (lib "eagle-import") (part "R-US_0603-C-NOSILK"))
    )
    (comp (ref "R259")
      (value "47k")
      (footprint "eagle-import:.0603-C-NOSILK")
      (fields (field (name "MFR") "Yageo") (field (name "MPN") "RC0603FR-0747KL"))
      (libsource (lib "eagle-import") (part "R-US_0603-C-NOSILK"))
    )
    (comp (ref "R260")
      (value "47k")
      (footprint "eagle-import:.0603-C-NOSILK")
      (fields (field (name "MFR") "Yageo") (field (name "MPN") "RC0603FR-0747KL"))
      (libsource (lib "eagle-import") (part "R-US_0603-C-NOSILK"))
    )
    (comp (ref "R261")
      (value "330k")
      (footprint "eagle-import:.0603-C-NOSILK")
      (fields (field (name "MFR") "Vishay") (field (name "MPN") "MCT06030C3303FP000"))
      (libsource (lib "eagle-import") (part "R-US_0603-C-NOSILK"))
    )
    (comp (ref "R262")
      (value "1M")
      (footprint "eagle-import:.0603-C-NOSILK")
      (fields (field (name "MFR") "Yageo") (field (name "MPN") "RC0603FR-071ML"))
      (libsource (lib "eagle-import") (part "R-US_0603-C-NOSILK"))
    )
    (comp (ref "R263")
      (value "100")
      (footprint "eagle-import:.0603-C-NOSILK")
      (fields (field (name "MFR") "Yageo") (field (name "MPN") "RC0603FR-07100RL"))
      (libsource (lib "eagle-import") (part "R-US_0603-C-NOSILK"))
    )
    (comp (ref "R264")
      (value "665k")
      (footprint "eagle-import:.0603-C-NOSILK")
      (fields (field (name "MFR") "Yageo") (field (name "MPN") "RC0603FR-07665KL"))
      (libsource (lib "eagle-import") (part "R-US_0603-C-NOSILK"))
    )
    (comp (ref "R265")
      (value "330k")
      (footprint "eagle-import:.0603-C-NOSILK")
      (fields (field (name "MFR") "Vishay") (field (name "MPN") "MCT06030C3303FP000"))
      (libsource (lib "eagle-import") (part "R-US_0603-C-NOSILK"))
    )
    (comp (ref "R266")
      (value "1M")
      (footprint "eagle-import:.0603-C-NOSILK")
      (fields (field (name "MFR") "Yageo") (field (name "MPN") "RC0603FR-071ML"))
      (libsource (lib "eagle-import") (part "R-US_0603-C-NOSILK"))
    )
    (comp (ref "TP91")
      (value "TEST-POINT-LARGE-SQUARE")
      (footprint "eagle-import:1X01")
      (libsource (lib "eagle-import") (part "TEST-POINT-LARGE-SQUARE"))
    )
    (comp (ref "TP92")
      (value "TEST-POINT-LARGE-SQUARE")
      (footprint "eagle-import:1X01")
      (libsource (lib "eagle-import") (part "TEST-POINT-LARGE-SQUARE"))
    )
    (comp (ref "TP93")
      (value "TEST-POINT-LARGE-SQUARE")
      (footprint "eagle-import:1X01")
      (libsource (lib "eagle-import") (part "TEST-POINT-LARGE-SQUARE"))
    )
    (comp (ref "TP94")
      (value "TEST-POINT-LARGE-SQUARE")
      (footprint "eagle-import:1X01")
      (libsource (lib "eagle-import") (part "TEST-POINT-LARGE-SQUARE"))
    )
    (comp (ref "TP95")
      (value "TEST-POINT-LARGE-SQUARE")
      (footprint "eagle-import:1X01")
      (libsource (lib "eagle-import") (part "TEST-POINT-LARGE-SQUARE"))
    )
    (comp (ref "TP96")
      (value "TEST-POINT-LARGE-SQUARE")
      (footprint "eagle-import:1X01")
      (libsource (lib "eagle-import") (part "TEST-POINT-LARGE-SQUARE"))
    )
    (comp (ref "TP97")
      (value "TEST-POINT-LARGE-SQUARE")
      (footprint "eagle-import:1X01")
      (libsource (lib "eagle-import") (part "TEST-POINT-LARGE-SQUARE"))
    )
    (comp (ref "TP98")
      (value "TEST-POINT-LARGE-SQUARE")
      (footprint "eagle-import:1X01")
      (libsource (lib "eagle-import") (part "TEST-POINT-LARGE-SQUARE"))
    )
    (comp (ref "TP99")
      (value "TEST-POINT-LARGE-SQUARE")
      (footprint "eagle-import:1X01")
      (libsource (lib "eagle-import") (part "TEST-POINT-LARGE-SQUARE"))
    )
    (comp (ref "TP100")
      (value "TEST-POINT-LARGE-SQUARE")
      (footprint "eagle-import:1X01")
      (libsource (lib "eagle-import") (part "TEST-POINT-LARGE-SQUARE"))
    )
    (comp (ref "TP101")
      (value "TEST-POINT-LARGE-SQUARE")
      (footprint "eagle-import:1X01")
      (libsource (lib "eagle-import") (part "TEST-POINT-LARGE-SQUARE"))
    )
    (comp (ref "TP102")
      (value "TEST-POINT-LARGE-SQUARE")
      (footprint "eagle-import:1X01")
      (libsource (lib "eagle-import") (part "TEST-POINT-LARGE-SQUARE"))
    )
    (comp (ref "TP103")
      (value "TEST-POINT-LARGE-SQUARE")
      (footprint "eagle-import:1X01")
      (libsource (lib "eagle-import") (part "TEST-POINT-LARGE-SQUARE"))
    )
    (comp (ref "TP104")
      (value "TEST-POINT-LARGE-SQUARE")
      (footprint "eagle-import:1X01")
      (libsource (lib "eagle-import") (part "TEST-POINT-LARGE-SQUARE"))
    )
    (comp (ref "TP105")
      (value "TEST-POINT-LARGE-SQUARE")
      (footprint "eagle-import:1X01")
      (libsource (lib "eagle-import") (part "TEST-POINT-LARGE-SQUARE"))
    )
    (comp (ref "U25")
      (value "MAX7310ATE")
      (footprint "eagle-import:QFN65P400X400X80-17T210")
      (fields (field (name "MFR") "Maxim"))
      (libsource (lib "eagle-import") (part "MAX7310"))
    )
    (comp (ref "U26")
      (value "MAX4211FETE")
      (footprint "eagle-import:QFN65P400X400X80-17T210")
      (fields (field (name "MFR") "Maxim"))
      (libsource (lib "eagle-import") (part "MAX4211"))
    )
    (comp (ref "U27")
      (value "MIC842LYC5")
      (footprint "eagle-import:SC70-5")
      (fields (field (name "MFR") "Microchip") (field (name "MPN") "MIC842LYC5-TR"))
      (libsource (lib "eagle-import") (part "MIC842LYC5"))
    )
    (comp (ref "U28")
      (value "MIC842LYC5")
      (footprint "eagle-import:SC70-5")
      (fields (field (name "MFR") "Microchip") (field (name "MPN") "MIC842LYC5-TR"))
      (libsource (lib "eagle-import") (part "MIC842LYC5"))
    )
    (comp (ref "C28")
      (value "100n")
      (footprint "eagle-import:.0603-C-NOSILK")
      (fields (field (name "MFR") "Samsung") (field (name "MPN") "CL10B104KB8NNNL"))
      (libsource (lib "eagle-import") (part "C-EU0603-C-NOSILK"))
    )
    (comp (ref "C29")
      (value "100n")
      (footprint "eagle-import:.0603-C-NOSILK")
      (fields (field (name "MFR") "Samsung") (field (name "MPN") "CL10B104KB8NNNL"))
      (libsource (lib "eagle-import") (part "C-EU0603-C-NOSILK"))
    )
    (comp (ref "C30")
      (value "20p")
      (footprint "eagle-import:.0603-C-NOSILK")
      (fields (field (name "MFR") "Samsung") (field (name "MPN") "CL10C200JB8NNNC"))
      (libsource (lib "eagle-import") (part "C-EU0603-C-NOSILK"))
    )
    (comp (ref "C36")
      (value "20p")
      (footprint "eagle-import:.0603-C-NOSILK")
      (fields (field (name "MFR") "Samsung") (field (name "MPN") "CL10C200JB8NNNC"))
      (libsource (lib "eagle-import") (part "C-EU0603-C-NOSILK"))
    )
    (comp (ref "C37")
      (value "100n")
      (footprint "eagle-import:.0603-C-NOSILK")
      (fields (field (name "MFR") "Samsung") (field (name "MPN") "CL10B104KB8NNNL"))
      (libsource (lib "eagle-import") (part "C-EU0603-C-NOSILK"))
    )
    (comp (ref "C38")
      (value "100n")
      (footprint "eagle-import:.0603-C-NOSILK")
      (fields (field (name "MFR") "Samsung") (field (name "MPN") "CL10B104KB8NNNL"))
      (libsource (lib "eagle-import") (part "C-EU0603-C-NOSILK"))
    )
    (comp (ref "C39")
      (value "100n")
      (footprint "eagle-import:.0603-C-NOSILK")
      (fields (field (name "MFR") "Samsung") (field (name "MPN") "CL10B104KB8NNNL"))
      (libsource (lib "eagle-import") (part "C-EU0603-C-NOSILK"))
    )
    (comp (ref "D2")
      (value "AMBER")
      (footprint "eagle-import:LED-0603")
      (fields (field (name "MFR") "Inolux") (field (name "MPN") "IN-S63AT5A"))
      (libsource (lib "eagle-import") (part "LED-GREEN0603"))
    )
    (comp (ref "J2")
      (value "ORESAT-DEBUG-CONNECTOR-SOLAR")
      (footprint "eagle-import:WURTH_687120183622")
      (libsource (lib "eagle-import") (part "ORESAT-DEBUG-CONNECTOR-SOLAR"))
    )
    (comp (ref "R7")
      (value "10k")
      (footprint "eagle-import:.0603-C-NOSILK")
      (fields (field (name "MFR") "Yageo") (field (name "MPN") "RC0603FR-0710KL"))
      (libsource (lib "eagle-import") (part "R-US_0603-C-NOSILK"))
    )
    (comp (ref "R8")
      (value "2.7k")
      (footprint "eagle-import:.0603-C-NOSILK")
      (fields (field (name "MFR") "TE Connectivity") (field (name "MPN") "CRGCQ0603F2K7"))
      (libsource (lib "eagle-import") (part "R-US_0603-C-NOSILK"))
    )
    (comp (ref "R9")
      (value "10k")
      (footprint "eagle-import:.0603-C-NOSILK")
      (fields (field (name "MFR") "Yageo") (field (name "MPN") "RC0603FR-0710KL"))
      (libsource (lib "eagle-import") (part "R-US_0603-C-NOSILK"))
    )
    (comp (ref "R11")
      (value "2.7k")
      (footprint "eagle-import:.0603-C-NOSILK")
      (fields (field (name "MFR") "TE Connectivity") (field (name "MPN") "CRGCQ0603F2K7"))
      (libsource (lib "eagle-import") (part "R-US_0603-C-NOSILK"))
    )
    (comp (ref "R12")
      (value "2.7k")
      (footprint "eagle-import:.0603-C-NOSILK")
      (fields (field (name "MFR") "TE Connectivity") (field (name "MPN") "CRGCQ0603F2K7"))
      (libsource (lib "eagle-import") (part "R-US_0603-C-NOSILK"))
    )
    (comp (ref "TP9")
      (value "TEST-POINT-LARGE-SQUARE")
      (footprint "eagle-import:1X01")
      (libsource (lib "eagle-import") (part "TEST-POINT-LARGE-SQUARE"))
    )
    (comp (ref "TP10")
      (value "TEST-POINT-LARGE-SQUARE")
      (footprint "eagle-import:1X01")
      (libsource (lib "eagle-import") (part "TEST-POINT-LARGE-SQUARE"))
    )
    (comp (ref "TP11")
      (value "TEST-POINT-LARGE-SQUARE")
      (footprint "eagle-import:1X01")
      (libsource (lib "eagle-import") (part "TEST-POINT-LARGE-SQUARE"))
    )
    (comp (ref "TP12")
      (value "TEST-POINT-LARGE-SQUARE")
      (footprint "eagle-import:1X01")
      (libsource (lib "eagle-import") (part "TEST-POINT-LARGE-SQUARE"))
    )
    (comp (ref "TP13")
      (value "TEST-POINT-LARGE-SQUARE")
      (footprint "eagle-import:1X01")
      (libsource (lib "eagle-import") (part "TEST-POINT-LARGE-SQUARE"))
    )
    (comp (ref "TP14")
      (value "TEST-POINT-LARGE-SQUARE")
      (footprint "eagle-import:1X01")
      (libsource (lib "eagle-import") (part "TEST-POINT-LARGE-SQUARE"))
    )
    (comp (ref "U14")
      (value "TCAN330")
      (footprint "eagle-import:SOT23-8_TI-DCN")
      (fields (field (name "MFR") "Texas Instruments") (field (name "MPN") "TCAN330GDCNT"))
      (libsource (lib "eagle-import") (part "TCAN330"))
    )
    (comp (ref "U15")
      (value "STM32F091C")
      (footprint "eagle-import:STM32F091C")
      (fields (field (name "MFR") "STMicroelectronics") (field (name "MPN") "STM32F042K6T7"))
      (libsource (lib "eagle-import") (part "STM32F091C"))
    )
    (comp (ref "X2")
      (value "16MHZ-2.5x2mm")
      (footprint "eagle-import:CRYSTAL_2.5X2")
      (fields (field (name "MFR") "ECS Inc.") (field (name "MPN") "ECS-160-10-36Q-ES-TR"))
      (libsource (lib "eagle-import") (part "CRYSTAL-WITH-GND"))
    )
    (comp (ref "C6")
      (value "100n")
      (footprint "eagle-import:.0603-C-NOSILK")
      (fields (field (name "MFR") "Samsung") (field (name "MPN") "CL10B104KB8NNNL"))
      (libsource (lib "eagle-import") (part "C-EU0603-C-NOSILK"))
    )
    (comp (ref "C7")
      (value "1u")
      (footprint "eagle-import:.0603-C-NOSILK")
      (libsource (lib "eagle-import") (part "C-EU0603-C-NOSILK"))
    )
    (comp (ref "C8")
      (value "1u")
      (footprint "eagle-import:.0603-C-NOSILK")
      (fields (field (name "MFR") "Yageo") (field (name "MPN") "CC0603KRX7R7BB105"))
      (libsource (lib "eagle-import") (part "C-EU0603-C-NOSILK"))
    )
    (comp (ref "C9")
      (value "1u")
      (footprint "eagle-import:.0603-C-NOSILK")
      (fields (field (name "MFR") "Yageo") (field (name "MPN") "CC0603KRX7R7BB105"))
      (libsource (lib "eagle-import") (part "C-EU0603-C-NOSILK"))
    )
    (comp (ref "C10")
      (value "1u")
      (footprint "eagle-import:.0603-C-NOSILK")
      (fields (field (name "MFR") "Yageo") (field (name "MPN") "CC0603KRX7R7BB105"))
      (libsource (lib "eagle-import") (part "C-EU0603-C-NOSILK"))
    )
    (comp (ref "D3")
      (value "GREEN")
      (footprint "eagle-import:LED-0603")
      (fields (field (name "MFR") "Rohm") (field (name "MPN") "SML-E12M8WT86"))
      (libsource (lib "eagle-import") (part "LED-GREEN0603"))
    )
    (comp (ref "D4")
      (value "AMBER")
      (footprint "eagle-import:LED-0603")
      (fields (field (name "MFR") "Inolux") (field (name "MPN") "IN-S63AT5A"))
      (libsource (lib "eagle-import") (part "LED-GREEN0603"))
    )
    (comp (ref "Q6")
      (value "MOSFET-PCH-SOT23-6")
      (footprint "eagle-import:SOT23-6")
      (fields (field (name "MFR") "Diodes Inc") (field (name "MPN") "DMP3050LVT-7"))
      (libsource (lib "eagle-import") (part "MOSFET-PCH-SOT23-6"))
    )
    (comp (ref "Q7")
      (value "MOSFET-PCH-SOT23-6")
      (footprint "eagle-import:SOT23-6")
      (fields (field (name "MFR") "Diodes Inc") (field (name "MPN") "DMP3050LVT-7"))
      (libsource (lib "eagle-import") (part "MOSFET-PCH-SOT23-6"))
    )
    (comp (ref "Q8")
      (value "PMV45EN")
      (footprint "eagle-import:SOT23")
      (fields (field (name "MFR") "Nexperia") (field (name "MPN") "PMV45EN2R"))
      (libsource (lib "eagle-import") (part "PMV45EN"))
    )
    (comp (ref "Q9")
      (value "PMV45EN")
      (footprint "eagle-import:SOT23")
      (fields (field (name "MFR") "Nexperia") (field (name "MPN") "PMV45EN2R"))
      (libsource (lib "eagle-import") (part "PMV45EN"))
    )
    (comp (ref "Q10")
      (value "DMP2240UDM")
      (footprint "eagle-import:SOT23-6")
      (fields
        (field (name "MFR") "Diodes Inc")
        (field (name "MPN") "DMP2240UDM")
        (field (name "DIS") "Digi-Key")
        (field (name "DPN") "DMP2240UDMDICT-ND")
      )
      (libsource (lib "eagle-import") (part "Q-MOSFET-PCH-dual-SOT23-6_MOSFET-PCH-SOT23-6"))
    )
    (comp (ref "R39")
      (value "2.7k")
      (footprint "eagle-import:.0603-C-NOSILK")
      (fields (field (name "MFR") "TE Connectivity") (field (name "MPN") "CRGCQ0603F2K7"))
      (libsource (lib "eagle-import") (part "R-US_0603-C-NOSILK"))
    )
    (comp (ref "R40")
      (value "10")
      (footprint "eagle-import:.0603-C-NOSILK")
      (fields (field (name "MFR") "Yageo") (field (name "MPN") "RC0603FR-0710RL"))
      (libsource (lib "eagle-import") (part "R-US_0603-C-NOSILK"))
    )
    (comp (ref "R41")
      (value "NP")
      (footprint "eagle-import:.0603-C-NOSILK")
      (fields (field (name "MFR") "Samsung") (field (name "MPN") "RC1005F6653CS"))
      (libsource (lib "eagle-import") (part "R-US_0603-C-NOSILK"))
    )
    (comp (ref "R42")
      (value "NP")
      (footprint "eagle-import:.0603-C-NOSILK")
      (fields (field (name "MFR") "Samsung") (field (name "MPN") "RC1005F6653CS"))
      (libsource (lib "eagle-import") (part "R-US_0603-C-NOSILK"))
    )
    (comp (ref "R43")
      (value "NP")
      (footprint "eagle-import:.0603-C-NOSILK")
      (fields (field (name "MFR") "Samsung") (field (name "MPN") "RC1005F6653CS"))
      (libsource (lib "eagle-import") (part "R-US_0603-C-NOSILK"))
    )
    (comp (ref "R44")
      (value "NP")
      (footprint "eagle-import:.0603-C-NOSILK")
      (fields (field (name "MFR") "Samsung") (field (name "MPN") "RC1005F6653CS"))
      (libsource (lib "eagle-import") (part "R-US_0603-C-NOSILK"))
    )
    (comp (ref "R45")
      (value "NP")
      (footprint "eagle-import:.0603-C-NOSILK")
      (fields (field (name "MFR") "Samsung") (field (name "MPN") "RC1005F6653CS"))
      (libsource (lib "eagle-import") (part "R-US_0603-C-NOSILK"))
    )
    (comp (ref "R46")
      (value "NP")
      (footprint "eagle-import:.0603-C-NOSILK")
      (fields (field (name "MFR") "Samsung") (field (name "MPN") "RC1005F6653CS"))
      (libsource (lib "eagle-import") (part "R-US_0603-C-NOSILK"))
    )
    (comp (ref "R47")
      (value "NP")
      (footprint "eagle-import:.0603-C-NOSILK")
      (fields (field (name "MFR") "Samsung") (field (name "MPN") "RC1005F6653CS"))
      (libsource (lib "eagle-import") (part "R-US_0603-C-NOSILK"))
    )
    (comp (ref "R48")
      (value "NP")
      (footprint "eagle-import:.0603-C-NOSILK")
      (fields (field (name "MFR") "Samsung") (field (name "MPN") "RC1005F6653CS"))
      (libsource (lib "eagle-import") (part "R-US_0603-C-NOSILK"))
    )
    (comp (ref "R49")
      (value "NP")
      (footprint "eagle-import:.0603-C-NOSILK")
      (fields (field (name "MFR") "Samsung") (field (name "MPN") "RC1005F6653CS"))
      (libsource (lib "eagle-import") (part "R-US_0603-C-NOSILK"))
    )
    (comp (ref "R50")
      (value "NP")
      (footprint "eagle-import:.0603-C-NOSILK")
      (fields (field (name "MFR") "Samsung") (field (name "MPN") "RC1005F6653CS"))
      (libsource (lib "eagle-import") (part "R-US_0603-C-NOSILK"))
    )
    (comp (ref "R51")
      (value "NP")
      (footprint "eagle-import:.0603-C-NOSILK")
      (fields (field (name "MFR") "Samsung") (field (name "MPN") "RC1005F6653CS"))
      (libsource (lib "eagle-import") (part "R-US_0603-C-NOSILK"))
    )
    (comp (ref "R52")
      (value "NP")
      (footprint "eagle-import:.0603-C-NOSILK")
      (fields (field (name "MFR") "Samsung") (field (name "MPN") "RC1005F6653CS"))
      (libsource (lib "eagle-import") (part "R-US_0603-C-NOSILK"))
    )
    (comp (ref "R53")
      (value "100")
      (footprint "eagle-import:.0603-C-NOSILK")
      (fields (field (name "MFR") "Yageo") (field (name "MPN") "RC0603FR-07100RL"))
      (libsource (lib "eagle-import") (part "R-US_0603-C-NOSILK"))
    )
    (comp (ref "R54")
      (value "10k")
      (footprint "eagle-import:.0603-C-NOSILK")
      (fields (field (name "MFR") "Yageo") (field (name "MPN") "RC0603FR-0710KL"))
      (libsource (lib "eagle-import") (part "R-US_0603-C-NOSILK"))
    )
    (comp (ref "R55")
      (value "10k")
      (footprint "eagle-import:.0603-C-NOSILK")
      (fields (field (name "MFR") "Yageo") (field (name "MPN") "RC0603FR-0710KL"))
      (libsource (lib "eagle-import") (part "R-US_0603-C-NOSILK"))
    )
    (comp (ref "R56")
      (value "10k")
      (footprint "eagle-import:.0603-C-NOSILK")
      (fields (field (name "MFR") "Yageo") (field (name "MPN") "RC0603FR-0710KL"))
      (libsource (lib "eagle-import") (part "R-US_0603-C-NOSILK"))
    )
    (comp (ref "R57")
      (value "100m")
      (footprint "eagle-import:R1206")
      (fields (field (name "MFR") "Stackpole") (field (name "MPN") "CSR1206FTR100"))
      (libsource (lib "eagle-import") (part "rcl_334_R-US_R1206"))
    )
    (comp (ref "R58")
      (value "10k")
      (footprint "eagle-import:.0603-C-NOSILK")
      (fields (field (name "MFR") "Yageo") (field (name "MPN") "RC0603FR-0710KL"))
      (libsource (lib "eagle-import") (part "R-US_0603-C-NOSILK"))
    )
    (comp (ref "R59")
      (value "0")
      (footprint "eagle-import:.0603-C-NOSILK")
      (fields (field (name "MFR") "Yageo") (field (name "MPN") "RC0603JR-070RL"))
      (libsource (lib "eagle-import") (part "R-US_0603-C-NOSILK"))
    )
    (comp (ref "R60")
      (value "NP")
      (footprint "eagle-import:.0603-C-NOSILK")
      (fields (field (name "MFR") "Samsung") (field (name "MPN") "RC1005F6653CS"))
      (libsource (lib "eagle-import") (part "R-US_0603-C-NOSILK"))
    )
    (comp (ref "R61")
      (value "0")
      (footprint "eagle-import:.0603-C-NOSILK")
      (fields (field (name "MFR") "Yageo") (field (name "MPN") "RC0603JR-070RL"))
      (libsource (lib "eagle-import") (part "R-US_0603-C-NOSILK"))
    )
    (comp (ref "R62")
      (value "NP")
      (footprint "eagle-import:.0603-C-NOSILK")
      (fields (field (name "MFR") "Samsung") (field (name "MPN") "RC1005F6653CS"))
      (libsource (lib "eagle-import") (part "R-US_0603-C-NOSILK"))
    )
    (comp (ref "R63")
      (value "10k")
      (footprint "eagle-import:.0603-C-NOSILK")
      (fields (field (name "MFR") "Yageo") (field (name "MPN") "RC0603FR-0710KL"))
      (libsource (lib "eagle-import") (part "R-US_0603-C-NOSILK"))
    )
    (comp (ref "R64")
      (value "100k")
      (footprint "eagle-import:.0603-C-NOSILK")
      (fields (field (name "MFR") "Samsung") (field (name "MPN") "RC1005F6653CS"))
      (libsource (lib "eagle-import") (part "R-US_0603-C-NOSILK"))
    )
    (comp (ref "R65")
      (value "10k")
      (footprint "eagle-import:.0603-C-NOSILK")
      (fields (field (name "MFR") "Samsung") (field (name "MPN") "RC1005F6653CS"))
      (libsource (lib "eagle-import") (part "R-US_0603-C-NOSILK"))
    )
    (comp (ref "R66")
      (value "10k")
      (footprint "eagle-import:.0603-C-NOSILK")
      (fields (field (name "MFR") "Yageo") (field (name "MPN") "RC0603FR-0710KL"))
      (libsource (lib "eagle-import") (part "R-US_0603-C-NOSILK"))
    )
    (comp (ref "R67")
      (value "2.7k")
      (footprint "eagle-import:.0603-C-NOSILK")
      (fields (field (name "MFR") "TE Connectivity") (field (name "MPN") "CRGCQ0603F2K7"))
      (libsource (lib "eagle-import") (part "R-US_0603-C-NOSILK"))
    )
    (comp (ref "R68")
      (value "665k")
      (footprint "eagle-import:.0603-C-NOSILK")
      (fields (field (name "MFR") "Yageo") (field (name "MPN") "RC0603FR-07665KL"))
      (libsource (lib "eagle-import") (part "R-US_0603-C-NOSILK"))
    )
    (comp (ref "R69")
      (value "47k")
      (footprint "eagle-import:.0603-C-NOSILK")
      (fields (field (name "MFR") "Yageo") (field (name "MPN") "RC0603FR-0747KL"))
      (libsource (lib "eagle-import") (part "R-US_0603-C-NOSILK"))
    )
    (comp (ref "R70")
      (value "47k")
      (footprint "eagle-import:.0603-C-NOSILK")
      (fields (field (name "MFR") "Yageo") (field (name "MPN") "RC0603FR-0747KL"))
      (libsource (lib "eagle-import") (part "R-US_0603-C-NOSILK"))
    )
    (comp (ref "R71")
      (value "330k")
      (footprint "eagle-import:.0603-C-NOSILK")
      (fields (field (name "MFR") "Vishay") (field (name "MPN") "MCT06030C3303FP000"))
      (libsource (lib "eagle-import") (part "R-US_0603-C-NOSILK"))
    )
    (comp (ref "R72")
      (value "1M")
      (footprint "eagle-import:.0603-C-NOSILK")
      (fields (field (name "MFR") "Yageo") (field (name "MPN") "RC0603FR-071ML"))
      (libsource (lib "eagle-import") (part "R-US_0603-C-NOSILK"))
    )
    (comp (ref "R73")
      (value "100")
      (footprint "eagle-import:.0603-C-NOSILK")
      (fields (field (name "MFR") "Yageo") (field (name "MPN") "RC0603FR-07100RL"))
      (libsource (lib "eagle-import") (part "R-US_0603-C-NOSILK"))
    )
    (comp (ref "R74")
      (value "665k")
      (footprint "eagle-import:.0603-C-NOSILK")
      (fields (field (name "MFR") "Yageo") (field (name "MPN") "RC0603FR-07665KL"))
      (libsource (lib "eagle-import") (part "R-US_0603-C-NOSILK"))
    )
    (comp (ref "R75")
      (value "330k")
      (footprint "eagle-import:.0603-C-NOSILK")
      (fields (field (name "MFR") "Vishay") (field (name "MPN") "MCT06030C3303FP000"))
      (libsource (lib "eagle-import") (part "R-US_0603-C-NOSILK"))
    )
    (comp (ref "R76")
      (value "1M")
      (footprint "eagle-import:.0603-C-NOSILK")
      (fields (field (name "MFR") "Yageo") (field (name "MPN") "RC0603FR-071ML"))
      (libsource (lib "eagle-import") (part "R-US_0603-C-NOSILK"))
    )
    (comp (ref "TP2")
      (value "TEST-POINT-LARGE-SQUARE")
      (footprint "eagle-import:1X01")
      (libsource (lib "eagle-import") (part "TEST-POINT-LARGE-SQUARE"))
    )
    (comp (ref "TP4")
      (value "TEST-POINT-LARGE-SQUARE")
      (footprint "eagle-import:1X01")
      (libsource (lib "eagle-import") (part "TEST-POINT-LARGE-SQUARE"))
    )
    (comp (ref "TP15")
      (value "TEST-POINT-LARGE-SQUARE")
      (footprint "eagle-import:1X01")
      (libsource (lib "eagle-import") (part "TEST-POINT-LARGE-SQUARE"))
    )
    (comp (ref "TP16")
      (value "TEST-POINT-LARGE-SQUARE")
      (footprint "eagle-import:1X01")
      (libsource (lib "eagle-import") (part "TEST-POINT-LARGE-SQUARE"))
    )
    (comp (ref "TP17")
      (value "TEST-POINT-LARGE-SQUARE")
      (footprint "eagle-import:1X01")
      (libsource (lib "eagle-import") (part "TEST-POINT-LARGE-SQUARE"))
    )
    (comp (ref "TP19")
      (value "TEST-POINT-LARGE-SQUARE")
      (footprint "eagle-import:1X01")
      (libsource (lib "eagle-import") (part "TEST-POINT-LARGE-SQUARE"))
    )
    (comp (ref "TP21")
      (value "TEST-POINT-LARGE-SQUARE")
      (footprint "eagle-import:1X01")
      (libsource (lib "eagle-import") (part "TEST-POINT-LARGE-SQUARE"))
    )
    (comp (ref "TP23")
      (value "TEST-POINT-LARGE-SQUARE")
      (footprint "eagle-import:1X01")
      (libsource (lib "eagle-import") (part "TEST-POINT-LARGE-SQUARE"))
    )
    (comp (ref "TP24")
      (value "TEST-POINT-LARGE-SQUARE")
      (footprint "eagle-import:1X01")
      (libsource (lib "eagle-import") (part "TEST-POINT-LARGE-SQUARE"))
    )
    (comp (ref "TP25")
      (value "TEST-POINT-LARGE-SQUARE")
      (footprint "eagle-import:1X01")
      (libsource (lib "eagle-import") (part "TEST-POINT-LARGE-SQUARE"))
    )
    (comp (ref "TP26")
      (value "TEST-POINT-LARGE-SQUARE")
      (footprint "eagle-import:1X01")
      (libsource (lib "eagle-import") (part "TEST-POINT-LARGE-SQUARE"))
    )
    (comp (ref "TP27")
      (value "TEST-POINT-LARGE-SQUARE")
      (footprint "eagle-import:1X01")
      (libsource (lib "eagle-import") (part "TEST-POINT-LARGE-SQUARE"))
    )
    (comp (ref "TP28")
      (value "TEST-POINT-LARGE-SQUARE")
      (footprint "eagle-import:1X01")
      (libsource (lib "eagle-import") (part "TEST-POINT-LARGE-SQUARE"))
    )
    (comp (ref "TP29")
      (value "TEST-POINT-LARGE-SQUARE")
      (footprint "eagle-import:1X01")
      (libsource (lib "eagle-import") (part "TEST-POINT-LARGE-SQUARE"))
    )
    (comp (ref "TP30")
      (value "TEST-POINT-LARGE-SQUARE")
      (footprint "eagle-import:1X01")
      (libsource (lib "eagle-import") (part "TEST-POINT-LARGE-SQUARE"))
    )
    (comp (ref "U5")
      (value "MAX7310ATE")
      (footprint "eagle-import:QFN65P400X400X80-17T210")
      (fields (field (name "MFR") "Maxim"))
      (libsource (lib "eagle-import") (part "MAX7310"))
    )
    (comp (ref "U6")
      (value "MAX4211FETE")
      (footprint "eagle-import:QFN65P400X400X80-17T210")
      (fields (field (name "MFR") "Maxim"))
      (libsource (lib "eagle-import") (part "MAX4211"))
    )
    (comp (ref "U7")
      (value "MIC842LYC5")
      (footprint "eagle-import:SC70-5")
      (fields (field (name "MFR") "Microchip") (field (name "MPN") "MIC842LYC5-TR"))
      (libsource (lib "eagle-import") (part "MIC842LYC5"))
    )
    (comp (ref "U8")
      (value "MIC842LYC5")
      (footprint "eagle-import:SC70-5")
      (fields (field (name "MFR") "Microchip") (field (name "MPN") "MIC842LYC5-TR"))
      (libsource (lib "eagle-import") (part "MIC842LYC5"))
    )
    (comp (ref "FIDUCIAL1")
      (value "FIDUCIAL-1.0X2.0")
      (footprint "eagle-import:FIDUCIAL-1.0X2.0")
      (libsource (lib "eagle-import") (part "FIDUCIAL-1.0X2.0"))
    )
    (comp (ref "FIDUCIAL2")
      (value "FIDUCIAL-1.0X2.0")
      (footprint "eagle-import:FIDUCIAL-1.0X2.0")
      (libsource (lib "eagle-import") (part "FIDUCIAL-1.0X2.0"))
    )
    (comp (ref "FIDUCIAL3")
      (value "FIDUCIAL-1.0X2.0")
      (footprint "eagle-import:FIDUCIAL-1.0X2.0")
      (libsource (lib "eagle-import") (part "FIDUCIAL-1.0X2.0"))
    )
    (comp (ref "FIDUCIAL4")
      (value "FIDUCIAL-1.0X2.0")
      (footprint "eagle-import:FIDUCIAL-1.0X2.0")
      (libsource (lib "eagle-import") (part "FIDUCIAL-1.0X2.0"))
    )
    (comp (ref "FIDUCIAL5")
      (value "FIDUCIAL-1.0X2.0")
      (footprint "eagle-import:FIDUCIAL-1.0X2.0")
      (libsource (lib "eagle-import") (part "FIDUCIAL-1.0X2.0"))
    )
    (comp (ref "FIDUCIAL6")
      (value "FIDUCIAL-1.0X2.0")
      (footprint "eagle-import:FIDUCIAL-1.0X2.0")
      (libsource (lib "eagle-import") (part "FIDUCIAL-1.0X2.0"))
    )
    (comp (ref "J6")
      (value "J-SAMTEC-TFM-120-X1-XXX-D-RA")
      (footprint "eagle-import:J-SAMTEC-TFM-120-X1-XXX-D-RA")
      (fields (field (name "MFR") "Samtec") (field (name "MPN") "TFM-120-01-L-D-RA"))
      (libsource (lib "eagle-import") (part "J-SAMTEC-TFM-120-X1-XXX-D-RA"))
    )
    (comp (ref "MAG_PIN_Q1")
      (value "PINHD-1X2")
      (footprint "eagle-import:1X02")
      (libsource (lib "eagle-import") (part "PINHD-1X2"))
    )
    (comp (ref "MAG_PIN_Q2")
      (value "PINHD-1X2")
      (footprint "eagle-import:1X02")
      (libsource (lib "eagle-import") (part "PINHD-1X2"))
    )
    (comp (ref "MAG_PIN_Q3")
      (value "PINHD-1X2")
      (footprint "eagle-import:1X02")
      (libsource (lib "eagle-import") (part "PINHD-1X2"))
    )
    (comp (ref "MAG_PIN_Q4")
      (value "PINHD-1X2")
      (footprint "eagle-import:1X02")
      (libsource (lib "eagle-import") (part "PINHD-1X2"))
    )
    (comp (ref "PCB1")
      (value "ORESAT-CARD-V1.3-GENERIC-0RF")
      (footprint "eagle-import:ORESAT-CARD-V1.3-GENERIC-0RF")
      (libsource (lib "eagle-import") (part "ORESAT-CARD-V1.3-GENERIC-0RF"))
    )
    (comp (ref "QUADRANT1")
      (value "MEZZANINE_PLUG")
      (footprint "eagle-import:MEZZANINE_PLUG")
      (fields (field (name "MFR") "Molex") (field (name "MPN") "0555600307"))
      (libsource (lib "eagle-import") (part "MEZZANINE_PLUG"))
    )
    (comp (ref "QUADRANT2")
      (value "MEZZANINE_PLUG")
      (footprint "eagle-import:MEZZANINE_PLUG")
      (fields (field (name "MFR") "Molex") (field (name "MPN") "0555600307"))
      (libsource (lib "eagle-import") (part "MEZZANINE_PLUG"))
    )
    (comp (ref "QUADRANT3")
      (value "MEZZANINE_PLUG")
      (footprint "eagle-import:MEZZANINE_PLUG")
      (fields (field (name "MFR") "Molex") (field (name "MPN") "0555600307"))
      (libsource (lib "eagle-import") (part "MEZZANINE_PLUG"))
    )
    (comp (ref "QUADRANT4")
      (value "MEZZANINE_PLUG")
      (footprint "eagle-import:MEZZANINE_PLUG")
      (fields (field (name "MFR") "Molex") (field (name "MPN") "0555600307"))
      (libsource (lib "eagle-import") (part "MEZZANINE_PLUG"))
    )
    (comp (ref "U$1")
      (value "FLIGHMARKERNEW")
      (footprint "eagle-import:FLIGHTMARKER_NEW_BOARDS")
      (libsource (lib "eagle-import") (part "FLIGHMARKERNEW"))
    )
  )
  (nets
    (net (code "1") (name "3.3V") (class "Default")
      (node (ref "C1") (pin "1") (pinfunction "1_1") (pintype "passive"))
      (node (ref "C16") (pin "1") (pinfunction "1_1") (pintype "passive"))
      (node (ref "C28") (pin "2") (pinfunction "2_2") (pintype "passive"))
      (node (ref "C29") (pin "2") (pinfunction "2_2") (pintype "passive"))
      (node (ref "C3") (pin "1") (pinfunction "1_1") (pintype "passive"))
      (node (ref "C37") (pin "2") (pinfunction "2_2") (pintype "passive"))
      (node (ref "C38") (pin "2") (pinfunction "2_2") (pintype "passive"))
      (node (ref "C39") (pin "2") (pinfunction "2_2") (pintype "passive"))
      (node (ref "C4") (pin "1") (pinfunction "1_1") (pintype "passive"))
      (node (ref "C47") (pin "1") (pinfunction "1_1") (pintype "passive"))
      (node (ref "J2") (pin "11") (pinfunction "VTARGET_11") (pintype "passive"))
      (node (ref "L3") (pin "2") (pinfunction "2_2") (pintype "passive"))
      (node (ref "R1") (pin "2") (pinfunction "2_2") (pintype "passive"))
      (node (ref "R10") (pin "1") (pinfunction "1_1") (pintype "passive"))
      (node (ref "R11") (pin "2") (pinfunction "2_2") (pintype "passive"))
      (node (ref "R12") (pin "2") (pinfunction "2_2") (pintype "passive"))
      (node (ref "R13") (pin "1") (pinfunction "1_1") (pintype "passive"))
      (node (ref "R199") (pin "2") (pinfunction "2_2") (pintype "passive"))
      (node (ref "R3") (pin "2") (pinfunction "2_2") (pintype "passive"))
      (node (ref "R6") (pin "1") (pinfunction "1_1") (pintype "passive"))
      (node (ref "TP113") (pin "1") (pinfunction "1_1") (pintype "passive"))
      (node (ref "U1") (pin "1") (pinfunction "IN_2_1") (pintype "power_in"))
      (node (ref "U1") (pin "2") (pinfunction "IN_2") (pintype "power_in"))
      (node (ref "U13") (pin "11") (pinfunction "VDDIO_11") (pintype "power_in"))
      (node (ref "U13") (pin "3") (pinfunction "VDD_3") (pintype "power_in"))
      (node (ref "U13") (pin "7") (pinfunction "PS_7") (pintype "input"))
      (node (ref "U14") (pin "3") (pinfunction "VCC_3") (pintype "power_in"))
      (node (ref "U15") (pin "1") (pinfunction "VBAT_1") (pintype "power_in"))
      (node (ref "U15") (pin "24") (pinfunction "VDD_24") (pintype "power_in"))
      (node (ref "U15") (pin "36") (pinfunction "VDDIO2_36") (pintype "power_in"))
      (node (ref "U15") (pin "48") (pinfunction "VDD_48") (pintype "power_in"))
      (node (ref "U15") (pin "9") (pinfunction "VDDA_9") (pintype "power_in"))
      (node (ref "U2") (pin "1") (pinfunction "ENABLE_1") (pintype "input"))
      (node (ref "U2") (pin "8") (pinfunction "VCC_8") (pintype "power_in"))
      (node (ref "U31") (pin "10") (pinfunction "FB_10") (pintype "input"))
    )
    (net (code "2") (name "AD0") (class "Default")
      (node (ref "R201") (pin "1") (pinfunction "1_1") (pintype "passive"))
      (node (ref "R202") (pin "2") (pinfunction "2_2") (pintype "passive"))
      (node (ref "R203") (pin "2") (pinfunction "2_2") (pintype "passive"))
      (node (ref "R204") (pin "1") (pinfunction "1_1") (pintype "passive"))
      (node (ref "U29") (pin "1") (pinfunction "AD0_1") (pintype "input"))
    )
    (net (code "3") (name "AD0_Q1") (class "Default")
      (node (ref "R79") (pin "1") (pinfunction "1_1") (pintype "passive"))
      (node (ref "R80") (pin "2") (pinfunction "2_2") (pintype "passive"))
      (node (ref "R81") (pin "2") (pinfunction "2_2") (pintype "passive"))
      (node (ref "R82") (pin "1") (pinfunction "1_1") (pintype "passive"))
      (node (ref "U9") (pin "1") (pinfunction "AD0_1") (pintype "input"))
    )
    (net (code "4") (name "AD0_Q2") (class "Default")
      (node (ref "R155") (pin "1") (pinfunction "1_1") (pintype "passive"))
      (node (ref "R156") (pin "2") (pinfunction "2_2") (pintype "passive"))
      (node (ref "R157") (pin "2") (pinfunction "2_2") (pintype "passive"))
      (node (ref "R158") (pin "1") (pinfunction "1_1") (pintype "passive"))
      (node (ref "U17") (pin "1") (pinfunction "AD0_1") (pintype "input"))
    )
    (net (code "5") (name "AD0_Q3") (class "Default")
      (node (ref "R231") (pin "1") (pinfunction "1_1") (pintype "passive"))
      (node (ref "R232") (pin "2") (pinfunction "2_2") (pintype "passive"))
      (node (ref "R233") (pin "2") (pinfunction "2_2") (pintype "passive"))
      (node (ref "R234") (pin "1") (pinfunction "1_1") (pintype "passive"))
      (node (ref "U25") (pin "1") (pinfunction "AD0_1") (pintype "input"))
    )
    (net (code "6") (name "AD0_Q4") (class "Default")
      (node (ref "R41") (pin "1") (pinfunction "1_1") (pintype "passive"))
      (node (ref "R42") (pin "2") (pinfunction "2_2") (pintype "passive"))
      (node (ref "R43") (pin "2") (pinfunction "2_2") (pintype "passive"))
      (node (ref "R44") (pin "1") (pinfunction "1_1") (pintype "passive"))
      (node (ref "U5") (pin "1") (pinfunction "AD0_1") (pintype "input"))
    )
    (net (code "7") (name "AD1") (class "Default")
      (node (ref "R205") (pin "1") (pinfunction "1_1") (pintype "passive"))
      (node (ref "R206") (pin "2") (pinfunction "2_2") (pintype "passive"))
      (node (ref "R207") (pin "2") (pinfunction "2_2") (pintype "passive"))
      (node (ref "R208") (pin "1") (pinfunction "1_1") (pintype "passive"))
      (node (ref "U29") (pin "2") (pinfunction "AD1_2") (pintype "input"))
    )
    (net (code "8") (name "AD1_Q1") (class "Default")
      (node (ref "R83") (pin "1") (pinfunction "1_1") (pintype "passive"))
      (node (ref "R84") (pin "2") (pinfunction "2_2") (pintype "passive"))
      (node (ref "R85") (pin "2") (pinfunction "2_2") (pintype "passive"))
      (node (ref "R86") (pin "1") (pinfunction "1_1") (pintype "passive"))
      (node (ref "U9") (pin "2") (pinfunction "AD1_2") (pintype "input"))
    )
    (net (code "9") (name "AD1_Q2") (class "Default")
      (node (ref "R159") (pin "1") (pinfunction "1_1") (pintype "passive"))
      (node (ref "R160") (pin "2") (pinfunction "2_2") (pintype "passive"))
      (node (ref "R161") (pin "2") (pinfunction "2_2") (pintype "passive"))
      (node (ref "R162") (pin "1") (pinfunction "1_1") (pintype "passive"))
      (node (ref "U17") (pin "2") (pinfunction "AD1_2") (pintype "input"))
    )
    (net (code "10") (name "AD1_Q3") (class "Default")
      (node (ref "R235") (pin "1") (pinfunction "1_1") (pintype "passive"))
      (node (ref "R236") (pin "2") (pinfunction "2_2") (pintype "passive"))
      (node (ref "R237") (pin "2") (pinfunction "2_2") (pintype "passive"))
      (node (ref "R238") (pin "1") (pinfunction "1_1") (pintype "passive"))
      (node (ref "U25") (pin "2") (pinfunction "AD1_2") (pintype "input"))
    )
    (net (code "11") (name "AD1_Q4") (class "Default")
      (node (ref "R45") (pin "1") (pinfunction "1_1") (pintype "passive"))
      (node (ref "R46") (pin "2") (pinfunction "2_2") (pintype "passive"))
      (node (ref "R47") (pin "2") (pinfunction "2_2") (pintype "passive"))
      (node (ref "R48") (pin "1") (pinfunction "1_1") (pintype "passive"))
      (node (ref "U5") (pin "2") (pinfunction "AD1_2") (pintype "input"))
    )
    (net (code "12") (name "AD2") (class "Default")
      (node (ref "R209") (pin "1") (pinfunction "1_1") (pintype "passive"))
      (node (ref "R210") (pin "2") (pinfunction "2_2") (pintype "passive"))
      (node (ref "R211") (pin "2") (pinfunction "2_2") (pintype "passive"))
      (node (ref "R212") (pin "1") (pinfunction "1_1") (pintype "passive"))
      (node (ref "U29") (pin "3") (pinfunction "AD2_3") (pintype "input"))
    )
    (net (code "13") (name "AD2_Q1") (class "Default")
      (node (ref "R87") (pin "1") (pinfunction "1_1") (pintype "passive"))
      (node (ref "R88") (pin "2") (pinfunction "2_2") (pintype "passive"))
      (node (ref "R89") (pin "2") (pinfunction "2_2") (pintype "passive"))
      (node (ref "R90") (pin "1") (pinfunction "1_1") (pintype "passive"))
      (node (ref "U9") (pin "3") (pinfunction "AD2_3") (pintype "input"))
    )
    (net (code "14") (name "AD2_Q2") (class "Default")
      (node (ref "R163") (pin "1") (pinfunction "1_1") (pintype "passive"))
      (node (ref "R164") (pin "2") (pinfunction "2_2") (pintype "passive"))
      (node (ref "R165") (pin "2") (pinfunction "2_2") (pintype "passive"))
      (node (ref "R166") (pin "1") (pinfunction "1_1") (pintype "passive"))
      (node (ref "U17") (pin "3") (pinfunction "AD2_3") (pintype "input"))
    )
    (net (code "15") (name "AD2_Q3") (class "Default")
      (node (ref "R239") (pin "1") (pinfunction "1_1") (pintype "passive"))
      (node (ref "R240") (pin "2") (pinfunction "2_2") (pintype "passive"))
      (node (ref "R241") (pin "2") (pinfunction "2_2") (pintype "passive"))
      (node (ref "R242") (pin "1") (pinfunction "1_1") (pintype "passive"))
      (node (ref "U25") (pin "3") (pinfunction "AD2_3") (pintype "input"))
    )
    (net (code "16") (name "AD2_Q4") (class "Default")
      (node (ref "R49") (pin "1") (pinfunction "1_1") (pintype "passive"))
      (node (ref "R50") (pin "2") (pinfunction "2_2") (pintype "passive"))
      (node (ref "R51") (pin "2") (pinfunction "2_2") (pintype "passive"))
      (node (ref "R52") (pin "1") (pinfunction "1_1") (pintype "passive"))
      (node (ref "U5") (pin "3") (pinfunction "AD2_3") (pintype "input"))
    )
    (net (code "17") (name "BOOT0") (class "Default")
      (node (ref "R7") (pin "2") (pinfunction "2_2") (pintype "passive"))
      (node (ref "TP9") (pin "1") (pinfunction "1_1") (pintype "passive"))
      (node (ref "U15") (pin "44") (pinfunction "PF11-BOOT0_44") (pintype "bidirectional"))
      (node (ref "U29") (pin "10") (pinfunction "IO5_10") (pintype "bidirectional"))
    )
    (net (code "18") (name "BOOT0_Q1") (class "Default")
      (node (ref "QUADRANT1") (pin "P$22") (pinfunction "BOOT_P$22") (pintype "bidirectional"))
      (node (ref "QUADRANT1") (pin "P$9") (pinfunction "BOOT_P$9") (pintype "bidirectional"))
      (node (ref "U9") (pin "10") (pinfunction "IO5_10") (pintype "bidirectional"))
    )
    (net (code "19") (name "BOOT0_Q2") (class "Default")
      (node (ref "QUADRANT2") (pin "P$22") (pinfunction "BOOT_P$22") (pintype "bidirectional"))
      (node (ref "QUADRANT2") (pin "P$9") (pinfunction "BOOT_P$9") (pintype "bidirectional"))
      (node (ref "U17") (pin "10") (pinfunction "IO5_10") (pintype "bidirectional"))
    )
    (net (code "20") (name "BOOT0_Q3") (class "Default")
      (node (ref "QUADRANT3") (pin "P$22") (pinfunction "BOOT_P$22") (pintype "bidirectional"))
      (node (ref "QUADRANT3") (pin "P$9") (pinfunction "BOOT_P$9") (pintype "bidirectional"))
      (node (ref "U25") (pin "10") (pinfunction "IO5_10") (pintype "bidirectional"))
    )
    (net (code "21") (name "BOOT0_Q4") (class "Default")
      (node (ref "QUADRANT4") (pin "P$22") (pinfunction "BOOT_P$22") (pintype "bidirectional"))
      (node (ref "QUADRANT4") (pin "P$9") (pinfunction "BOOT_P$9") (pintype "bidirectional"))
      (node (ref "U5") (pin "10") (pinfunction "IO5_10") (pintype "bidirectional"))
    )
    (net (code "22") (name "CAN2_H") (class "Default")
      (node (ref "J6") (pin "17") (pinfunction "17_17") (pintype "passive"))
      (node (ref "J6") (pin "18") (pinfunction "18_18") (pintype "passive"))
      (node (ref "QUADRANT1") (pin "P$25") (pinfunction "CAN_H_P$25") (pintype "bidirectional"))
      (node (ref "QUADRANT1") (pin "P$6") (pinfunction "CAN_H_P$6") (pintype "bidirectional"))
      (node (ref "QUADRANT2") (pin "P$25") (pinfunction "CAN_H_P$25") (pintype "bidirectional"))
      (node (ref "QUADRANT2") (pin "P$6") (pinfunction "CAN_H_P$6") (pintype "bidirectional"))
      (node (ref "QUADRANT3") (pin "P$25") (pinfunction "CAN_H_P$25") (pintype "bidirectional"))
      (node (ref "QUADRANT3") (pin "P$6") (pinfunction "CAN_H_P$6") (pintype "bidirectional"))
      (node (ref "QUADRANT4") (pin "P$25") (pinfunction "CAN_H_P$25") (pintype "bidirectional"))
      (node (ref "QUADRANT4") (pin "P$6") (pinfunction "CAN_H_P$6") (pintype "bidirectional"))
      (node (ref "U14") (pin "7") (pinfunction "CANH_7") (pintype "bidirectional"))
    )
    (net (code "23") (name "CAN2_L") (class "Default")
      (node (ref "J6") (pin "19") (pinfunction "19_19") (pintype "passive"))
      (node (ref "J6") (pin "20") (pinfunction "20_20") (pintype "passive"))
      (node (ref "QUADRANT1") (pin "P$26") (pinfunction "CAN_L_P$26") (pintype "bidirectional"))
      (node (ref "QUADRANT1") (pin "P$5") (pinfunction "CAN_L_P$5") (pintype "bidirectional"))
      (node (ref "QUADRANT2") (pin "P$26") (pinfunction "CAN_L_P$26") (pintype "bidirectional"))
      (node (ref "QUADRANT2") (pin "P$5") (pinfunction "CAN_L_P$5") (pintype "bidirectional"))
      (node (ref "QUADRANT3") (pin "P$26") (pinfunction "CAN_L_P$26") (pintype "bidirectional"))
      (node (ref "QUADRANT3") (pin "P$5") (pinfunction "CAN_L_P$5") (pintype "bidirectional"))
      (node (ref "QUADRANT4") (pin "P$26") (pinfunction "CAN_L_P$26") (pintype "bidirectional"))
      (node (ref "QUADRANT4") (pin "P$5") (pinfunction "CAN_L_P$5") (pintype "bidirectional"))
      (node (ref "U14") (pin "6") (pinfunction "CANL_6") (pintype "bidirectional"))
    )
    (net (code "24") (name "CAN_RX") (class "Default")
      (node (ref "U14") (pin "4") (pinfunction "RXD_4") (pintype "output"))
      (node (ref "U15") (pin "32") (pinfunction "PA11_32") (pintype "bidirectional"))
    )
    (net (code "25") (name "CAN_SHDN") (class "Default")
      (node (ref "U14") (pin "5") (pinfunction "SHDN_5") (pintype "input"))
      (node (ref "U15") (pin "31") (pinfunction "PA10_31") (pintype "bidirectional"))
    )
    (net (code "26") (name "CAN_TX") (class "Default")
      (node (ref "U14") (pin "1") (pinfunction "TXD_1") (pintype "input"))
      (node (ref "U15") (pin "33") (pinfunction "PA12_33") (pintype "bidirectional"))
    )
    (net (code "27") (name "CB-RESET") (class "Default")
      (node (ref "R218") (pin "2") (pinfunction "2_2") (pintype "passive"))
      (node (ref "TP108") (pin "1") (pinfunction "1_1") (pintype "passive"))
      (node (ref "U29") (pin "9") (pinfunction "IO4_9") (pintype "bidirectional"))
      (node (ref "U30") (pin "9") (pinfunction "CIN2-_9") (pintype "input"))
    )
    (net (code "28") (name "CB-RESET_Q1") (class "Default")
      (node (ref "R96") (pin "2") (pinfunction "2_2") (pintype "passive"))
      (node (ref "TP35") (pin "1") (pinfunction "1_1") (pintype "passive"))
      (node (ref "U10") (pin "9") (pinfunction "CIN2-_9") (pintype "input"))
      (node (ref "U9") (pin "9") (pinfunction "IO4_9") (pintype "bidirectional"))
    )
    (net (code "29") (name "CB-RESET_Q2") (class "Default")
      (node (ref "R172") (pin "2") (pinfunction "2_2") (pintype "passive"))
      (node (ref "TP65") (pin "1") (pinfunction "1_1") (pintype "passive"))
      (node (ref "U17") (pin "9") (pinfunction "IO4_9") (pintype "bidirectional"))
      (node (ref "U18") (pin "9") (pinfunction "CIN2-_9") (pintype "input"))
    )
    (net (code "30") (name "CB-RESET_Q3") (class "Default")
      (node (ref "R248") (pin "2") (pinfunction "2_2") (pintype "passive"))
      (node (ref "TP95") (pin "1") (pinfunction "1_1") (pintype "passive"))
      (node (ref "U25") (pin "9") (pinfunction "IO4_9") (pintype "bidirectional"))
      (node (ref "U26") (pin "9") (pinfunction "CIN2-_9") (pintype "input"))
    )
    (net (code "31") (name "CB-RESET_Q4") (class "Default")
      (node (ref "R58") (pin "2") (pinfunction "2_2") (pintype "passive"))
      (node (ref "TP17") (pin "1") (pinfunction "1_1") (pintype "passive"))
      (node (ref "U5") (pin "9") (pinfunction "IO4_9") (pintype "bidirectional"))
      (node (ref "U6") (pin "9") (pinfunction "CIN2-_9") (pintype "input"))
    )
    (net (code "32") (name "CB_CTRL") (class "Default")
      (node (ref "Q26") (pin "3") (pinfunction "G_3") (pintype "passive"))
      (node (ref "Q29") (pin "1") (pinfunction "G_1") (pintype "passive"))
      (node (ref "R223") (pin "1") (pinfunction "1_1") (pintype "passive"))
      (node (ref "TP118") (pin "1") (pinfunction "1_1") (pintype "passive"))
      (node (ref "U30") (pin "3") (pinfunction "LE_3") (pintype "input"))
      (node (ref "U30") (pin "4") (pinfunction "COUT1_4") (pintype "open_collector"))
      (node (ref "U30") (pin "6") (pinfunction "COUT2_6") (pintype "open_collector"))
    )
    (net (code "33") (name "CB_CTRL_Q1") (class "Default")
      (node (ref "Q11") (pin "3") (pinfunction "G_3") (pintype "passive"))
      (node (ref "Q14") (pin "1") (pinfunction "G_1") (pintype "passive"))
      (node (ref "R101") (pin "1") (pinfunction "1_1") (pintype "passive"))
      (node (ref "TP42") (pin "1") (pinfunction "1_1") (pintype "passive"))
      (node (ref "U10") (pin "3") (pinfunction "LE_3") (pintype "input"))
      (node (ref "U10") (pin "4") (pinfunction "COUT1_4") (pintype "open_collector"))
      (node (ref "U10") (pin "6") (pinfunction "COUT2_6") (pintype "open_collector"))
    )
    (net (code "34") (name "CB_CTRL_Q2") (class "Default")
      (node (ref "Q21") (pin "3") (pinfunction "G_3") (pintype "passive"))
      (node (ref "Q24") (pin "1") (pinfunction "G_1") (pintype "passive"))
      (node (ref "R177") (pin "1") (pinfunction "1_1") (pintype "passive"))
      (node (ref "TP72") (pin "1") (pinfunction "1_1") (pintype "passive"))
      (node (ref "U18") (pin "3") (pinfunction "LE_3") (pintype "input"))
      (node (ref "U18") (pin "4") (pinfunction "COUT1_4") (pintype "open_collector"))
      (node (ref "U18") (pin "6") (pinfunction "COUT2_6") (pintype "open_collector"))
    )
    (net (code "35") (name "CB_CTRL_Q3") (class "Default")
      (node (ref "Q31") (pin "3") (pinfunction "G_3") (pintype "passive"))
      (node (ref "Q34") (pin "1") (pinfunction "G_1") (pintype "passive"))
      (node (ref "R253") (pin "1") (pinfunction "1_1") (pintype "passive"))
      (node (ref "TP102") (pin "1") (pinfunction "1_1") (pintype "passive"))
      (node (ref "U26") (pin "3") (pinfunction "LE_3") (pintype "input"))
      (node (ref "U26") (pin "4") (pinfunction "COUT1_4") (pintype "open_collector"))
      (node (ref "U26") (pin "6") (pinfunction "COUT2_6") (pintype "open_collector"))
    )
    (net (code "36") (name "CB_CTRL_Q4") (class "Default")
      (node (ref "Q6") (pin "3") (pinfunction "G_3") (pintype "passive"))
      (node (ref "Q9") (pin "1") (pinfunction "G_1") (pintype "passive"))
      (node (ref "R63") (pin "1") (pinfunction "1_1") (pintype "passive"))
      (node (ref "TP27") (pin "1") (pinfunction "1_1") (pintype "passive"))
      (node (ref "U6") (pin "3") (pinfunction "LE_3") (pintype "input"))
      (node (ref "U6") (pin "4") (pinfunction "COUT1_4") (pintype "open_collector"))
      (node (ref "U6") (pin "6") (pinfunction "COUT2_6") (pintype "open_collector"))
    )
    (net (code "37") (name "GND") (class "Default")
      (node (ref "C1") (pin "2") (pinfunction "2_2") (pintype "passive"))
      (node (ref "C10") (pin "2") (pinfunction "2_2") (pintype "passive"))
      (node (ref "C11") (pin "1") (pinfunction "1_1") (pintype "passive"))
      (node (ref "C13") (pin "2") (pinfunction "2_2") (pintype "passive"))
      (node (ref "C14") (pin "2") (pinfunction "2_2") (pintype "passive"))
      (node (ref "C15") (pin "2") (pinfunction "2_2") (pintype "passive"))
      (node (ref "C16") (pin "2") (pinfunction "2_2") (pintype "passive"))
      (node (ref "C2") (pin "2") (pinfunction "2_2") (pintype "passive"))
      (node (ref "C21") (pin "1") (pinfunction "1_1") (pintype "passive"))
      (node (ref "C23") (pin "2") (pinfunction "2_2") (pintype "passive"))
      (node (ref "C24") (pin "2") (pinfunction "2_2") (pintype "passive"))
      (node (ref "C25") (pin "2") (pinfunction "2_2") (pintype "passive"))
      (node (ref "C28") (pin "1") (pinfunction "1_1") (pintype "passive"))
      (node (ref "C29") (pin "1") (pinfunction "1_1") (pintype "passive"))
      (node (ref "C3") (pin "2") (pinfunction "2_2") (pintype "passive"))
      (node (ref "C30") (pin "2") (pinfunction "2_2") (pintype "passive"))
      (node (ref "C31") (pin "1") (pinfunction "1_1") (pintype "passive"))
      (node (ref "C33") (pin "2") (pinfunction "2_2") (pintype "passive"))
      (node (ref "C34") (pin "2") (pinfunction "2_2") (pintype "passive"))
      (node (ref "C35") (pin "2") (pinfunction "2_2") (pintype "passive"))
      (node (ref "C36") (pin "2") (pinfunction "2_2") (pintype "passive"))
      (node (ref "C37") (pin "1") (pinfunction "1_1") (pintype "passive"))
      (node (ref "C38") (pin "1") (pinfunction "1_1") (pintype "passive"))
      (node (ref "C39") (pin "1") (pinfunction "1_1") (pintype "passive"))
      (node (ref "C4") (pin "2") (pinfunction "2_2") (pintype "passive"))
      (node (ref "C43") (pin "1") (pinfunction "1_1") (pintype "passive"))
      (node (ref "C45") (pin "2") (pinfunction "2_2") (pintype "passive"))
      (node (ref "C46") (pin "2") (pinfunction "2_2") (pintype "passive"))
      (node (ref "C47") (pin "2") (pinfunction "2_2") (pintype "passive"))
      (node (ref "C48") (pin "2") (pinfunction "2_2") (pintype "passive"))
      (node (ref "C49") (pin "2") (pinfunction "2_2") (pintype "passive"))
      (node (ref "C50") (pin "2") (pinfunction "2_2") (pintype "passive"))
      (node (ref "C6") (pin "1") (pinfunction "1_1") (pintype "passive"))
      (node (ref "C8") (pin "2") (pinfunction "2_2") (pintype "passive"))
      (node (ref "C9") (pin "2") (pinfunction "2_2") (pintype "passive"))
      (node (ref "D10") (pin "C") (pinfunction "C_C") (pintype "passive"))
      (node (ref "D13") (pin "C") (pinfunction "C_C") (pintype "passive"))
      (node (ref "D14") (pin "C") (pinfunction "C_C") (pintype "passive"))
      (node (ref "D16") (pin "C") (pinfunction "C_C") (pintype "passive"))
      (node (ref "D17") (pin "C") (pinfunction "C_C") (pintype "passive"))
      (node (ref "D18") (pin "C") (pinfunction "C_C") (pintype "passive"))
      (node (ref "D2") (pin "C") (pinfunction "C_C") (pintype "passive"))
      (node (ref "D3") (pin "C") (pinfunction "C_C") (pintype "passive"))
      (node (ref "D4") (pin "C") (pinfunction "C_C") (pintype "passive"))
      (node (ref "D5") (pin "C") (pinfunction "C_C") (pintype "passive"))
      (node (ref "D6") (pin "C") (pinfunction "C_C") (pintype "passive"))
      (node (ref "D9") (pin "C") (pinfunction "C_C") (pintype "passive"))
      (node (ref "J2") (pin "3") (pinfunction "GND_3") (pintype "passive"))
      (node (ref "J2") (pin "6") (pinfunction "GND_6") (pintype "passive"))
      (node (ref "J2") (pin "9") (pinfunction "GND_9") (pintype "passive"))
      (node (ref "J2") (pin "PAD1") (pinfunction "PAD_PAD1") (pintype "bidirectional"))
      (node (ref "J2") (pin "PAD2") (pinfunction "PAD_PAD2") (pintype "bidirectional"))
      (node (ref "J6") (pin "27") (pinfunction "27_27") (pintype "passive"))
      (node (ref "J6") (pin "28") (pinfunction "28_28") (pintype "passive"))
      (node (ref "J6") (pin "29") (pinfunction "29_29") (pintype "passive"))
      (node (ref "J6") (pin "30") (pinfunction "30_30") (pintype "passive"))
      (node (ref "J6") (pin "31") (pinfunction "31_31") (pintype "passive"))
      (node (ref "J6") (pin "32") (pinfunction "32_32") (pintype "passive"))
      (node (ref "J6") (pin "37") (pinfunction "37_37") (pintype "passive"))
      (node (ref "J6") (pin "38") (pinfunction "38_38") (pintype "passive"))
      (node (ref "Q13") (pin "2") (pinfunction "S_2") (pintype "passive"))
      (node (ref "Q14") (pin "2") (pinfunction "S_2") (pintype "passive"))
      (node (ref "Q23") (pin "2") (pinfunction "S_2") (pintype "passive"))
      (node (ref "Q24") (pin "2") (pinfunction "S_2") (pintype "passive"))
      (node (ref "Q28") (pin "2") (pinfunction "S_2") (pintype "passive"))
      (node (ref "Q29") (pin "2") (pinfunction "S_2") (pintype "passive"))
      (node (ref "Q33") (pin "2") (pinfunction "S_2") (pintype "passive"))
      (node (ref "Q34") (pin "2") (pinfunction "S_2") (pintype "passive"))
      (node (ref "Q8") (pin "2") (pinfunction "S_2") (pintype "passive"))
      (node (ref "Q9") (pin "2") (pinfunction "S_2") (pintype "passive"))
      (node (ref "QUADRANT1") (pin "P$1") (pinfunction "GND_P$1") (pintype "bidirectional"))
      (node (ref "QUADRANT1") (pin "P$14") (pinfunction "GND_P$14") (pintype "bidirectional"))
      (node (ref "QUADRANT1") (pin "P$15") (pinfunction "GND_P$15") (pintype "bidirectional"))
      (node (ref "QUADRANT1") (pin "P$16") (pinfunction "GND_P$16") (pintype "bidirectional"))
      (node (ref "QUADRANT1") (pin "P$17") (pinfunction "GND_P$17") (pintype "bidirectional"))
      (node (ref "QUADRANT1") (pin "P$2") (pinfunction "GND_P$2") (pintype "bidirectional"))
      (node (ref "QUADRANT1") (pin "P$29") (pinfunction "GND_P$29") (pintype "bidirectional"))
      (node (ref "QUADRANT1") (pin "P$30") (pinfunction "GND_P$30") (pintype "bidirectional"))
      (node (ref "QUADRANT2") (pin "P$1") (pinfunction "GND_P$1") (pintype "bidirectional"))
      (node (ref "QUADRANT2") (pin "P$14") (pinfunction "GND_P$14") (pintype "bidirectional"))
      (node (ref "QUADRANT2") (pin "P$15") (pinfunction "GND_P$15") (pintype "bidirectional"))
      (node (ref "QUADRANT2") (pin "P$16") (pinfunction "GND_P$16") (pintype "bidirectional"))
      (node (ref "QUADRANT2") (pin "P$17") (pinfunction "GND_P$17") (pintype "bidirectional"))
      (node (ref "QUADRANT2") (pin "P$2") (pinfunction "GND_P$2") (pintype "bidirectional"))
      (node (ref "QUADRANT2") (pin "P$29") (pinfunction "GND_P$29") (pintype "bidirectional"))
      (node (ref "QUADRANT2") (pin "P$30") (pinfunction "GND_P$30") (pintype "bidirectional"))
      (node (ref "QUADRANT3") (pin "P$1") (pinfunction "GND_P$1") (pintype "bidirectional"))
      (node (ref "QUADRANT3") (pin "P$14") (pinfunction "GND_P$14") (pintype "bidirectional"))
      (node (ref "QUADRANT3") (pin "P$15") (pinfunction "GND_P$15") (pintype "bidirectional"))
      (node (ref "QUADRANT3") (pin "P$16") (pinfunction "GND_P$16") (pintype "bidirectional"))
      (node (ref "QUADRANT3") (pin "P$17") (pinfunction "GND_P$17") (pintype "bidirectional"))
      (node (ref "QUADRANT3") (pin "P$2") (pinfunction "GND_P$2") (pintype "bidirectional"))
      (node (ref "QUADRANT3") (pin "P$29") (pinfunction "GND_P$29") (pintype "bidirectional"))
      (node (ref "QUADRANT3") (pin "P$30") (pinfunction "GND_P$30") (pintype "bidirectional"))
      (node (ref "QUADRANT4") (pin "P$1") (pinfunction "GND_P$1") (pintype "bidirectional"))
      (node (ref "QUADRANT4") (pin "P$14") (pinfunction "GND_P$14") (pintype "bidirectional"))
      (node (ref "QUADRANT4") (pin "P$15") (pinfunction "GND_P$15") (pintype "bidirectional"))
      (node (ref "QUADRANT4") (pin "P$16") (pinfunction "GND_P$16") (pintype "bidirectional"))
      (node (ref "QUADRANT4") (pin "P$17") (pinfunction "GND_P$17") (pintype "bidirectional"))
      (node (ref "QUADRANT4") (pin "P$2") (pinfunction "GND_P$2") (pintype "bidirectional"))
      (node (ref "QUADRANT4") (pin "P$29") (pinfunction "GND_P$29") (pintype "bidirectional"))
      (node (ref "QUADRANT4") (pin "P$30") (pinfunction "GND_P$30") (pintype "bidirectional"))
      (node (ref "R100") (pin "1") (pinfunction "1_1") (pintype "passive"))
      (node (ref "R102") (pin "1") (pinfunction "1_1") (pintype "passive"))
      (node (ref "R157") (pin "1") (pinfunction "1_1") (pintype "passive"))
      (node (ref "R161") (pin "1") (pinfunction "1_1") (pintype "passive"))
      (node (ref "R165") (pin "1") (pinfunction "1_1") (pintype "passive"))
      (node (ref "R170") (pin "1") (pinfunction "1_1") (pintype "passive"))
      (node (ref "R172") (pin "1") (pinfunction "1_1") (pintype "passive"))
      (node (ref "R174") (pin "1") (pinfunction "1_1") (pintype "passive"))
      (node (ref "R176") (pin "1") (pinfunction "1_1") (pintype "passive"))
      (node (ref "R178") (pin "1") (pinfunction "1_1") (pintype "passive"))
      (node (ref "R2") (pin "1") (pinfunction "1_1") (pintype "passive"))
      (node (ref "R203") (pin "1") (pinfunction "1_1") (pintype "passive"))
      (node (ref "R207") (pin "1") (pinfunction "1_1") (pintype "passive"))
      (node (ref "R211") (pin "1") (pinfunction "1_1") (pintype "passive"))
      (node (ref "R216") (pin "1") (pinfunction "1_1") (pintype "passive"))
      (node (ref "R218") (pin "1") (pinfunction "1_1") (pintype "passive"))
      (node (ref "R220") (pin "1") (pinfunction "1_1") (pintype "passive"))
      (node (ref "R222") (pin "1") (pinfunction "1_1") (pintype "passive"))
      (node (ref "R224") (pin "1") (pinfunction "1_1") (pintype "passive"))
      (node (ref "R228") (pin "1") (pinfunction "1_1") (pintype "passive"))
      (node (ref "R233") (pin "1") (pinfunction "1_1") (pintype "passive"))
      (node (ref "R237") (pin "1") (pinfunction "1_1") (pintype "passive"))
      (node (ref "R241") (pin "1") (pinfunction "1_1") (pintype "passive"))
      (node (ref "R246") (pin "1") (pinfunction "1_1") (pintype "passive"))
      (node (ref "R248") (pin "1") (pinfunction "1_1") (pintype "passive"))
      (node (ref "R250") (pin "1") (pinfunction "1_1") (pintype "passive"))
      (node (ref "R252") (pin "1") (pinfunction "1_1") (pintype "passive"))
      (node (ref "R254") (pin "1") (pinfunction "1_1") (pintype "passive"))
      (node (ref "R4") (pin "1") (pinfunction "1_1") (pintype "passive"))
      (node (ref "R43") (pin "1") (pinfunction "1_1") (pintype "passive"))
      (node (ref "R47") (pin "1") (pinfunction "1_1") (pintype "passive"))
      (node (ref "R5") (pin "1") (pinfunction "1_1") (pintype "passive"))
      (node (ref "R51") (pin "1") (pinfunction "1_1") (pintype "passive"))
      (node (ref "R56") (pin "1") (pinfunction "1_1") (pintype "passive"))
      (node (ref "R58") (pin "1") (pinfunction "1_1") (pintype "passive"))
      (node (ref "R60") (pin "1") (pinfunction "1_1") (pintype "passive"))
      (node (ref "R62") (pin "1") (pinfunction "1_1") (pintype "passive"))
      (node (ref "R64") (pin "1") (pinfunction "1_1") (pintype "passive"))
      (node (ref "R7") (pin "1") (pinfunction "1_1") (pintype "passive"))
      (node (ref "R81") (pin "1") (pinfunction "1_1") (pintype "passive"))
      (node (ref "R85") (pin "1") (pinfunction "1_1") (pintype "passive"))
      (node (ref "R89") (pin "1") (pinfunction "1_1") (pintype "passive"))
      (node (ref "R94") (pin "1") (pinfunction "1_1") (pintype "passive"))
      (node (ref "R96") (pin "1") (pinfunction "1_1") (pintype "passive"))
      (node (ref "R98") (pin "1") (pinfunction "1_1") (pintype "passive"))
      (node (ref "U1") (pin "4") (pinfunction "GND_4") (pintype "power_in"))
      (node (ref "U10") (pin "7") (pinfunction "GND_7") (pintype "power_in"))
      (node (ref "U10") (pin "EPAD") (pinfunction "GND_EPAD") (pintype "power_in"))
      (node (ref "U11") (pin "2") (pinfunction "GND_2") (pintype "power_in"))
      (node (ref "U12") (pin "2") (pinfunction "GND_2") (pintype "power_in"))
      (node (ref "U13") (pin "4") (pinfunction "GNDA_4") (pintype "power_in"))
      (node (ref "U13") (pin "6") (pinfunction "GNDIO_6") (pintype "power_in"))
      (node (ref "U14") (pin "2") (pinfunction "GND_2") (pintype "power_in"))
      (node (ref "U15") (pin "23") (pinfunction "VSS_23") (pintype "power_in"))
      (node (ref "U15") (pin "35") (pinfunction "VSS_35") (pintype "power_in"))
      (node (ref "U15") (pin "47") (pinfunction "VSS_47") (pintype "power_in"))
      (node (ref "U15") (pin "8") (pinfunction "VSSA_8") (pintype "power_in"))
      (node (ref "U17") (pin "6") (pinfunction "GND_6") (pintype "power_in"))
      (node (ref "U17") (pin "EPAD") (pinfunction "GND_EPAD") (pintype "power_in"))
      (node (ref "U18") (pin "7") (pinfunction "GND_7") (pintype "power_in"))
      (node (ref "U18") (pin "EPAD") (pinfunction "GND_EPAD") (pintype "power_in"))
      (node (ref "U19") (pin "2") (pinfunction "GND_2") (pintype "power_in"))
      (node (ref "U2") (pin "4") (pinfunction "GND_4") (pintype "power_in"))
      (node (ref "U20") (pin "2") (pinfunction "GND_2") (pintype "power_in"))
      (node (ref "U25") (pin "6") (pinfunction "GND_6") (pintype "power_in"))
      (node (ref "U25") (pin "EPAD") (pinfunction "GND_EPAD") (pintype "power_in"))
      (node (ref "U26") (pin "7") (pinfunction "GND_7") (pintype "power_in"))
      (node (ref "U26") (pin "EPAD") (pinfunction "GND_EPAD") (pintype "power_in"))
      (node (ref "U27") (pin "2") (pinfunction "GND_2") (pintype "power_in"))
      (node (ref "U28") (pin "2") (pinfunction "GND_2") (pintype "power_in"))
      (node (ref "U29") (pin "6") (pinfunction "GND_6") (pintype "power_in"))
      (node (ref "U29") (pin "EPAD") (pinfunction "GND_EPAD") (pintype "power_in"))
      (node (ref "U30") (pin "7") (pinfunction "GND_7") (pintype "power_in"))
      (node (ref "U30") (pin "EPAD") (pinfunction "GND_EPAD") (pintype "power_in"))
      (node (ref "U31") (pin "1") (pinfunction "GND_1") (pintype "power_in"))
      (node (ref "U31") (pin "11") (pinfunction "GND_11") (pintype "power_in"))
      (node (ref "U31") (pin "12") (pinfunction "GND_12") (pintype "power_in"))
      (node (ref "U31") (pin "16") (pinfunction "GND_16") (pintype "power_in"))
      (node (ref "U31") (pin "6") (pinfunction "LBO_6") (pintype "open_collector"))
      (node (ref "U31") (pin "7") (pinfunction "LBI_7") (pintype "input"))
      (node (ref "U31") (pin "9") (pinfunction "GND_9") (pintype "power_in"))
      (node (ref "U31") (pin "PAD") (pinfunction "GND_PAD") (pintype "power_in"))
      (node (ref "U32") (pin "2") (pinfunction "GND_2") (pintype "power_in"))
      (node (ref "U33") (pin "2") (pinfunction "GND_2") (pintype "power_in"))
      (node (ref "U5") (pin "6") (pinfunction "GND_6") (pintype "power_in"))
      (node (ref "U5") (pin "EPAD") (pinfunction "GND_EPAD") (pintype "power_in"))
      (node (ref "U6") (pin "7") (pinfunction "GND_7") (pintype "power_in"))
      (node (ref "U6") (pin "EPAD") (pinfunction "GND_EPAD") (pintype "power_in"))
      (node (ref "U7") (pin "2") (pinfunction "GND_2") (pintype "power_in"))
      (node (ref "U8") (pin "2") (pinfunction "GND_2") (pintype "power_in"))
      (node (ref "U9") (pin "6") (pinfunction "GND_6") (pintype "power_in"))
      (node (ref "U9") (pin "EPAD") (pinfunction "GND_EPAD") (pintype "power_in"))
      (node (ref "X2") (pin "2") (pinfunction "SHIELD_2") (pintype "power_in"))
      (node (ref "X2") (pin "4") (pinfunction "SHIELD_4") (pintype "power_in"))
    )
    (net (code "38") (name "IMU_INT1") (class "Default")
      (node (ref "U13") (pin "16") (pinfunction "INT1_16") (pintype "bidirectional"))
      (node (ref "U15") (pin "25") (pinfunction "PB12_25") (pintype "bidirectional"))
    )
    (net (code "39") (name "IMU_INT2") (class "Default")
      (node (ref "U13") (pin "1") (pinfunction "INT2_1") (pintype "bidirectional"))
      (node (ref "U15") (pin "26") (pinfunction "PB13_26") (pintype "bidirectional"))
    )
    (net (code "40") (name "IMU_INT3") (class "Default")
      (node (ref "U13") (pin "12") (pinfunction "INT3_12") (pintype "bidirectional"))
      (node (ref "U15") (pin "28") (pinfunction "PB15_28") (pintype "bidirectional"))
    )
    (net (code "41") (name "IMU_INT4") (class "Default")
      (node (ref "U13") (pin "13") (pinfunction "INT4_13") (pintype "bidirectional"))
      (node (ref "U15") (pin "27") (pinfunction "PB14_27") (pintype "bidirectional"))
    )
    (net (code "42") (name "MAG1_Q1") (class "Default")
      (node (ref "MAG_PIN_Q1") (pin "1") (pinfunction "1_1") (pintype "passive"))
      (node (ref "QUADRANT1") (pin "P$10") (pinfunction "MAG_1_P$10") (pintype "bidirectional"))
      (node (ref "QUADRANT1") (pin "P$21") (pinfunction "MAG_1_P$21") (pintype "bidirectional"))
    )
    (net (code "43") (name "MAG1_Q2") (class "Default")
      (node (ref "MAG_PIN_Q2") (pin "1") (pinfunction "1_1") (pintype "passive"))
      (node (ref "QUADRANT2") (pin "P$10") (pinfunction "MAG_1_P$10") (pintype "bidirectional"))
      (node (ref "QUADRANT2") (pin "P$21") (pinfunction "MAG_1_P$21") (pintype "bidirectional"))
    )
    (net (code "44") (name "MAG1_Q3") (class "Default")
      (node (ref "MAG_PIN_Q3") (pin "1") (pinfunction "1_1") (pintype "passive"))
      (node (ref "QUADRANT3") (pin "P$10") (pinfunction "MAG_1_P$10") (pintype "bidirectional"))
      (node (ref "QUADRANT3") (pin "P$21") (pinfunction "MAG_1_P$21") (pintype "bidirectional"))
    )
    (net (code "45") (name "MAG1_Q4") (class "Default")
      (node (ref "MAG_PIN_Q4") (pin "1") (pinfunction "1_1") (pintype "passive"))
      (node (ref "QUADRANT4") (pin "P$10") (pinfunction "MAG_1_P$10") (pintype "bidirectional"))
      (node (ref "QUADRANT4") (pin "P$21") (pinfunction "MAG_1_P$21") (pintype "bidirectional"))
    )
    (net (code "46") (name "MAG2_Q1") (class "Default")
      (node (ref "MAG_PIN_Q1") (pin "2") (pinfunction "2_2") (pintype "passive"))
      (node (ref "QUADRANT1") (pin "P$11") (pinfunction "MAG_2_P$11") (pintype "bidirectional"))
      (node (ref "QUADRANT1") (pin "P$20") (pinfunction "MAG_2_P$20") (pintype "bidirectional"))
    )
    (net (code "47") (name "MAG2_Q2") (class "Default")
      (node (ref "MAG_PIN_Q2") (pin "2") (pinfunction "2_2") (pintype "passive"))
      (node (ref "QUADRANT2") (pin "P$11") (pinfunction "MAG_2_P$11") (pintype "bidirectional"))
      (node (ref "QUADRANT2") (pin "P$20") (pinfunction "MAG_2_P$20") (pintype "bidirectional"))
    )
    (net (code "48") (name "MAG2_Q3") (class "Default")
      (node (ref "MAG_PIN_Q3") (pin "2") (pinfunction "2_2") (pintype "passive"))
      (node (ref "QUADRANT3") (pin "P$11") (pinfunction "MAG_2_P$11") (pintype "bidirectional"))
      (node (ref "QUADRANT3") (pin "P$20") (pinfunction "MAG_2_P$20") (pintype "bidirectional"))
    )
    (net (code "49") (name "MAG2_Q4") (class "Default")
      (node (ref "MAG_PIN_Q4") (pin "2") (pinfunction "2_2") (pintype "passive"))
      (node (ref "QUADRANT4") (pin "P$11") (pinfunction "MAG_2_P$11") (pintype "bidirectional"))
      (node (ref "QUADRANT4") (pin "P$20") (pinfunction "MAG_2_P$20") (pintype "bidirectional"))
    )
    (net (code "50") (name "MAG_PWR") (class "Default")
      (node (ref "C2") (pin "1") (pinfunction "1_1") (pintype "passive"))
      (node (ref "J6") (pin "5") (pinfunction "5_5") (pintype "passive"))
      (node (ref "J6") (pin "6") (pinfunction "6_6") (pintype "passive"))
      (node (ref "TP7") (pin "1") (pinfunction "1_1") (pintype "passive"))
      (node (ref "U1") (pin "7") (pinfunction "OUT_2_7") (pintype "power_in"))
      (node (ref "U1") (pin "8") (pinfunction "OUT_8") (pintype "power_in"))
    )
    (net (code "51") (name "MAG_READY") (class "Default")
      (node (ref "R10") (pin "2") (pinfunction "2_2") (pintype "passive"))
      (node (ref "U15") (pin "41") (pinfunction "PB5_41") (pintype "bidirectional"))
      (node (ref "U2") (pin "5") (pinfunction "READY_5") (pintype "output"))
    )
    (net (code "52") (name "MAG_SCL") (class "Default")
      (node (ref "J6") (pin "3") (pinfunction "3_3") (pintype "passive"))
      (node (ref "J6") (pin "4") (pinfunction "4_4") (pintype "passive"))
      (node (ref "R13") (pin "2") (pinfunction "2_2") (pintype "passive"))
      (node (ref "TP1") (pin "1") (pinfunction "1_1") (pintype "passive"))
      (node (ref "U2") (pin "3") (pinfunction "SCLIN_3") (pintype "input"))
    )
    (net (code "53") (name "MAG_SDA") (class "Default")
      (node (ref "J6") (pin "1") (pinfunction "1_1") (pintype "passive"))
      (node (ref "J6") (pin "2") (pinfunction "2_2") (pintype "passive"))
      (node (ref "R6") (pin "2") (pinfunction "2_2") (pintype "passive"))
      (node (ref "TP3") (pin "1") (pinfunction "1_1") (pintype "passive"))
      (node (ref "U2") (pin "6") (pinfunction "SDAIN_6") (pintype "input"))
    )
    (net (code "54") (name "MAG_~{EN}") (class "Default")
      (node (ref "R3") (pin "1") (pinfunction "1_1") (pintype "passive"))
      (node (ref "TP6") (pin "1") (pinfunction "1_1") (pintype "passive"))
      (node (ref "U1") (pin "3") (pinfunction "~{ON}_3") (pintype "input"))
      (node (ref "U15") (pin "40") (pinfunction "PB4_40") (pintype "bidirectional"))
    )
    (net (code "55") (name "MAG_~{FAULT}") (class "Default")
      (node (ref "R1") (pin "1") (pinfunction "1_1") (pintype "passive"))
      (node (ref "TP5") (pin "1") (pinfunction "1_1") (pintype "passive"))
      (node (ref "U1") (pin "6") (pinfunction "~{FAULT}_6") (pintype "output"))
      (node (ref "U15") (pin "39") (pinfunction "PB3_39") (pintype "bidirectional"))
    )
    (net (code "56") (name "NRESET") (class "Default")
      (node (ref "J2") (pin "10") (pinfunction "NRST_10") (pintype "passive"))
      (node (ref "U15") (pin "7") (pinfunction "NRST_7") (pintype "bidirectional"))
    )
    (net (code "57") (name "Net-(C7-Pad1)") (class "Default")
      (node (ref "C7") (pin "1") (pinfunction "1_1") (pintype "passive"))
      (node (ref "R64") (pin "2") (pinfunction "2_2") (pintype "passive"))
      (node (ref "R65") (pin "2") (pinfunction "2_2") (pintype "passive"))
    )
    (net (code "58") (name "Net-(C12-Pad1)") (class "Default")
      (node (ref "C12") (pin "1") (pinfunction "1_1") (pintype "passive"))
      (node (ref "R102") (pin "2") (pinfunction "2_2") (pintype "passive"))
      (node (ref "R103") (pin "2") (pinfunction "2_2") (pintype "passive"))
    )
    (net (code "59") (name "Net-(C22-Pad1)") (class "Default")
      (node (ref "C22") (pin "1") (pinfunction "1_1") (pintype "passive"))
      (node (ref "R178") (pin "2") (pinfunction "2_2") (pintype "passive"))
      (node (ref "R179") (pin "2") (pinfunction "2_2") (pintype "passive"))
    )
    (net (code "60") (name "Net-(C32-Pad1)") (class "Default")
      (node (ref "C32") (pin "1") (pinfunction "1_1") (pintype "passive"))
      (node (ref "R254") (pin "2") (pinfunction "2_2") (pintype "passive"))
      (node (ref "R255") (pin "2") (pinfunction "2_2") (pintype "passive"))
    )
    (net (code "61") (name "Net-(C44-Pad1)") (class "Default")
      (node (ref "C44") (pin "1") (pinfunction "1_1") (pintype "passive"))
      (node (ref "R224") (pin "2") (pinfunction "2_2") (pintype "passive"))
      (node (ref "R225") (pin "2") (pinfunction "2_2") (pintype "passive"))
    )
    (net (code "62") (name "Net-(D2-PadA)") (class "Default")
      (node (ref "D2") (pin "A") (pinfunction "A_A") (pintype "passive"))
      (node (ref "R8") (pin "1") (pinfunction "1_1") (pintype "passive"))
    )
    (net (code "63") (name "Net-(D3-PadA)") (class "Default")
      (node (ref "D3") (pin "A") (pinfunction "A_A") (pintype "passive"))
      (node (ref "R39") (pin "1") (pinfunction "1_1") (pintype "passive"))
    )
    (net (code "64") (name "Net-(D4-PadA)") (class "Default")
      (node (ref "D4") (pin "A") (pinfunction "A_A") (pintype "passive"))
      (node (ref "R67") (pin "1") (pinfunction "1_1") (pintype "passive"))
    )
    (net (code "65") (name "Net-(D5-PadA)") (class "Default")
      (node (ref "D5") (pin "A") (pinfunction "A_A") (pintype "passive"))
      (node (ref "R77") (pin "1") (pinfunction "1_1") (pintype "passive"))
    )
    (net (code "66") (name "Net-(D6-PadA)") (class "Default")
      (node (ref "D6") (pin "A") (pinfunction "A_A") (pintype "passive"))
      (node (ref "R105") (pin "1") (pinfunction "1_1") (pintype "passive"))
    )
    (net (code "67") (name "Net-(D9-PadA)") (class "Default")
      (node (ref "D9") (pin "A") (pinfunction "A_A") (pintype "passive"))
      (node (ref "R153") (pin "1") (pinfunction "1_1") (pintype "passive"))
    )
    (net (code "68") (name "Net-(D10-PadA)") (class "Default")
      (node (ref "D10") (pin "A") (pinfunction "A_A") (pintype "passive"))
      (node (ref "R181") (pin "1") (pinfunction "1_1") (pintype "passive"))
    )
    (net (code "69") (name "Net-(D13-PadA)") (class "Default")
      (node (ref "D13") (pin "A") (pinfunction "A_A") (pintype "passive"))
      (node (ref "R229") (pin "1") (pinfunction "1_1") (pintype "passive"))
    )
    (net (code "70") (name "Net-(D14-PadA)") (class "Default")
      (node (ref "D14") (pin "A") (pinfunction "A_A") (pintype "passive"))
      (node (ref "R257") (pin "1") (pinfunction "1_1") (pintype "passive"))
    )
    (net (code "71") (name "Net-(D16-PadA)") (class "Default")
      (node (ref "D16") (pin "A") (pinfunction "A_A") (pintype "passive"))
      (node (ref "R198") (pin "1") (pinfunction "1_1") (pintype "passive"))
    )
    (net (code "72") (name "Net-(D17-PadA)") (class "Default")
      (node (ref "D17") (pin "A") (pinfunction "A_A") (pintype "passive"))
      (node (ref "R199") (pin "1") (pinfunction "1_1") (pintype "passive"))
    )
    (net (code "73") (name "Net-(D18-PadA)") (class "Default")
      (node (ref "D18") (pin "A") (pinfunction "A_A") (pintype "passive"))
      (node (ref "R267") (pin "1") (pinfunction "1_1") (pintype "passive"))
    )
    (net (code "74") (name "Net-(J2-DEBUG-0)") (class "Default")
      (node (ref "J2") (pin "17") (pinfunction "DEBUG-0_17") (pintype "passive"))
      (node (ref "TP10") (pin "1") (pinfunction "1_1") (pintype "passive"))
    )
    (net (code "75") (name "Net-(J2-DEBUG-1)") (class "Default")
      (node (ref "J2") (pin "18") (pinfunction "DEBUG-1_18") (pintype "passive"))
      (node (ref "TP11") (pin "1") (pinfunction "1_1") (pintype "passive"))
    )
    (net (code "76") (name "Net-(J2-DEBUG-2)") (class "Default")
      (node (ref "J2") (pin "19") (pinfunction "DEBUG-2_19") (pintype "passive"))
      (node (ref "TP12") (pin "1") (pinfunction "1_1") (pintype "passive"))
    )
    (net (code "77") (name "Net-(J2-DEBUG-3)") (class "Default")
      (node (ref "J2") (pin "20") (pinfunction "DEBUG-3_20") (pintype "passive"))
      (node (ref "TP13") (pin "1") (pinfunction "1_1") (pintype "passive"))
    )
    (net (code "78") (name "Net-(J2-SWO)") (class "Default")
      (node (ref "J2") (pin "16") (pinfunction "SWO_16") (pintype "passive"))
      (node (ref "TP14") (pin "1") (pinfunction "1_1") (pintype "passive"))
    )
    (net (code "79") (name "Net-(J6-Pad7)") (class "Default")
      (node (ref "J6") (pin "7") (pinfunction "7_7") (pintype "passive"))
      (node (ref "J6") (pin "8") (pinfunction "8_8") (pintype "passive"))
    )
    (net (code "80") (name "Net-(J6-Pad10)") (class "Default")
      (node (ref "J6") (pin "10") (pinfunction "10_10") (pintype "passive"))
      (node (ref "J6") (pin "9") (pinfunction "9_9") (pintype "passive"))
    )
    (net (code "81") (name "Net-(J6-Pad33)") (class "Default")
      (node (ref "J6") (pin "33") (pinfunction "33_33") (pintype "passive"))
      (node (ref "J6") (pin "34") (pinfunction "34_34") (pintype "passive"))
    )
    (net (code "82") (name "Net-(J6-Pad35)") (class "Default")
      (node (ref "J6") (pin "35") (pinfunction "35_35") (pintype "passive"))
      (node (ref "J6") (pin "36") (pinfunction "36_36") (pintype "passive"))
    )
    (net (code "83") (name "Net-(J6-Pad39)") (class "Default")
      (node (ref "J6") (pin "39") (pinfunction "39_39") (pintype "passive"))
      (node (ref "J6") (pin "40") (pinfunction "40_40") (pintype "passive"))
    )
    (net (code "84") (name "Net-(L3-Pad1)") (class "Default")
      (node (ref "L3") (pin "1") (pinfunction "1_1") (pintype "passive"))
      (node (ref "U31") (pin "14") (pinfunction "SW_14") (pintype "output"))
      (node (ref "U31") (pin "15") (pinfunction "SW_15") (pintype "output"))
    )
    (net (code "85") (name "Net-(Q6-S)") (class "Default")
      (node (ref "Q6") (pin "4") (pinfunction "S_4") (pintype "passive"))
      (node (ref "R57") (pin "2") (pinfunction "2_2") (pintype "passive"))
      (node (ref "R63") (pin "2") (pinfunction "2_2") (pintype "passive"))
      (node (ref "U6") (pin "15") (pinfunction "RS-_15") (pintype "passive"))
    )
    (net (code "86") (name "Net-(Q7-G)") (class "Default")
      (node (ref "Q7") (pin "3") (pinfunction "G_3") (pintype "passive"))
      (node (ref "Q8") (pin "3") (pinfunction "D_3") (pintype "passive"))
      (node (ref "R55") (pin "1") (pinfunction "1_1") (pintype "passive"))
    )
    (net (code "87") (name "Net-(Q10A-G)") (class "Default")
      (node (ref "Q10") (pin "1") (pinfunction "G_1") (pintype "passive"))
      (node (ref "R68") (pin "2") (pinfunction "2_2") (pintype "passive"))
    )
    (net (code "88") (name "Net-(Q10A-S)") (class "Default")
      (node (ref "Q10") (pin "5") (pinfunction "S_5") (pintype "passive"))
      (node (ref "R53") (pin "2") (pinfunction "2_2") (pintype "passive"))
    )
    (net (code "89") (name "Net-(Q10B-G)") (class "Default")
      (node (ref "Q10") (pin "3") (pinfunction "G_3") (pintype "passive"))
      (node (ref "R74") (pin "2") (pinfunction "2_2") (pintype "passive"))
    )
    (net (code "90") (name "Net-(Q10B-S)") (class "Default")
      (node (ref "Q10") (pin "2") (pinfunction "S_2") (pintype "passive"))
      (node (ref "R73") (pin "2") (pinfunction "2_2") (pintype "passive"))
    )
    (net (code "91") (name "Net-(Q11-S)") (class "Default")
      (node (ref "Q11") (pin "4") (pinfunction "S_4") (pintype "passive"))
      (node (ref "R101") (pin "2") (pinfunction "2_2") (pintype "passive"))
      (node (ref "R95") (pin "2") (pinfunction "2_2") (pintype "passive"))
      (node (ref "U10") (pin "15") (pinfunction "RS-_15") (pintype "passive"))
    )
    (net (code "92") (name "Net-(Q12-G)") (class "Default")
      (node (ref "Q12") (pin "3") (pinfunction "G_3") (pintype "passive"))
      (node (ref "Q13") (pin "3") (pinfunction "D_3") (pintype "passive"))
      (node (ref "R93") (pin "1") (pinfunction "1_1") (pintype "passive"))
    )
    (net (code "93") (name "Net-(Q15A-G)") (class "Default")
      (node (ref "Q15") (pin "1") (pinfunction "G_1") (pintype "passive"))
      (node (ref "R106") (pin "2") (pinfunction "2_2") (pintype "passive"))
    )
    (net (code "94") (name "Net-(Q15A-S)") (class "Default")
      (node (ref "Q15") (pin "5") (pinfunction "S_5") (pintype "passive"))
      (node (ref "R91") (pin "2") (pinfunction "2_2") (pintype "passive"))
    )
    (net (code "95") (name "Net-(Q15B-G)") (class "Default")
      (node (ref "Q15") (pin "3") (pinfunction "G_3") (pintype "passive"))
      (node (ref "R112") (pin "2") (pinfunction "2_2") (pintype "passive"))
    )
    (net (code "96") (name "Net-(Q15B-S)") (class "Default")
      (node (ref "Q15") (pin "2") (pinfunction "S_2") (pintype "passive"))
      (node (ref "R111") (pin "2") (pinfunction "2_2") (pintype "passive"))
    )
    (net (code "97") (name "Net-(Q21-S)") (class "Default")
      (node (ref "Q21") (pin "4") (pinfunction "S_4") (pintype "passive"))
      (node (ref "R171") (pin "2") (pinfunction "2_2") (pintype "passive"))
      (node (ref "R177") (pin "2") (pinfunction "2_2") (pintype "passive"))
      (node (ref "U18") (pin "15") (pinfunction "RS-_15") (pintype "passive"))
    )
    (net (code "98") (name "Net-(Q22-G)") (class "Default")
      (node (ref "Q22") (pin "3") (pinfunction "G_3") (pintype "passive"))
      (node (ref "Q23") (pin "3") (pinfunction "D_3") (pintype "passive"))
      (node (ref "R169") (pin "1") (pinfunction "1_1") (pintype "passive"))
    )
    (net (code "99") (name "Net-(Q25A-G)") (class "Default")
      (node (ref "Q25") (pin "1") (pinfunction "G_1") (pintype "passive"))
      (node (ref "R182") (pin "2") (pinfunction "2_2") (pintype "passive"))
    )
    (net (code "100") (name "Net-(Q25A-S)") (class "Default")
      (node (ref "Q25") (pin "5") (pinfunction "S_5") (pintype "passive"))
      (node (ref "R167") (pin "2") (pinfunction "2_2") (pintype "passive"))
    )
    (net (code "101") (name "Net-(Q25B-G)") (class "Default")
      (node (ref "Q25") (pin "3") (pinfunction "G_3") (pintype "passive"))
      (node (ref "R188") (pin "2") (pinfunction "2_2") (pintype "passive"))
    )
    (net (code "102") (name "Net-(Q25B-S)") (class "Default")
      (node (ref "Q25") (pin "2") (pinfunction "S_2") (pintype "passive"))
      (node (ref "R187") (pin "2") (pinfunction "2_2") (pintype "passive"))
    )
    (net (code "103") (name "Net-(Q26-S)") (class "Default")
      (node (ref "Q26") (pin "4") (pinfunction "S_4") (pintype "passive"))
      (node (ref "R217") (pin "2") (pinfunction "2_2") (pintype "passive"))
      (node (ref "R223") (pin "2") (pinfunction "2_2") (pintype "passive"))
      (node (ref "U30") (pin "15") (pinfunction "RS-_15") (pintype "passive"))
    )
    (net (code "104") (name "Net-(Q27-G)") (class "Default")
      (node (ref "Q27") (pin "3") (pinfunction "G_3") (pintype "passive"))
      (node (ref "Q28") (pin "3") (pinfunction "D_3") (pintype "passive"))
      (node (ref "R215") (pin "1") (pinfunction "1_1") (pintype "passive"))
    )
    (net (code "105") (name "Net-(Q30A-G)") (class "Default")
      (node (ref "Q30") (pin "1") (pinfunction "G_1") (pintype "passive"))
      (node (ref "R268") (pin "2") (pinfunction "2_2") (pintype "passive"))
    )
    (net (code "106") (name "Net-(Q30A-S)") (class "Default")
      (node (ref "Q30") (pin "5") (pinfunction "S_5") (pintype "passive"))
      (node (ref "R213") (pin "2") (pinfunction "2_2") (pintype "passive"))
    )
    (net (code "107") (name "Net-(Q30B-G)") (class "Default")
      (node (ref "Q30") (pin "3") (pinfunction "G_3") (pintype "passive"))
      (node (ref "R272") (pin "2") (pinfunction "2_2") (pintype "passive"))
    )
    (net (code "108") (name "Net-(Q30B-S)") (class "Default")
      (node (ref "Q30") (pin "2") (pinfunction "S_2") (pintype "passive"))
      (node (ref "R271") (pin "2") (pinfunction "2_2") (pintype "passive"))
    )
    (net (code "109") (name "Net-(Q31-S)") (class "Default")
      (node (ref "Q31") (pin "4") (pinfunction "S_4") (pintype "passive"))
      (node (ref "R247") (pin "2") (pinfunction "2_2") (pintype "passive"))
      (node (ref "R253") (pin "2") (pinfunction "2_2") (pintype "passive"))
      (node (ref "U26") (pin "15") (pinfunction "RS-_15") (pintype "passive"))
    )
    (net (code "110") (name "Net-(Q32-G)") (class "Default")
      (node (ref "Q32") (pin "3") (pinfunction "G_3") (pintype "passive"))
      (node (ref "Q33") (pin "3") (pinfunction "D_3") (pintype "passive"))
      (node (ref "R245") (pin "1") (pinfunction "1_1") (pintype "passive"))
    )
    (net (code "111") (name "Net-(Q35A-G)") (class "Default")
      (node (ref "Q35") (pin "1") (pinfunction "G_1") (pintype "passive"))
      (node (ref "R258") (pin "2") (pinfunction "2_2") (pintype "passive"))
    )
    (net (code "112") (name "Net-(Q35A-S)") (class "Default")
      (node (ref "Q35") (pin "5") (pinfunction "S_5") (pintype "passive"))
      (node (ref "R243") (pin "2") (pinfunction "2_2") (pintype "passive"))
    )
    (net (code "113") (name "Net-(Q35B-G)") (class "Default")
      (node (ref "Q35") (pin "3") (pinfunction "G_3") (pintype "passive"))
      (node (ref "R264") (pin "2") (pinfunction "2_2") (pintype "passive"))
    )
    (net (code "114") (name "Net-(Q35B-S)") (class "Default")
      (node (ref "Q35") (pin "2") (pinfunction "S_2") (pintype "passive"))
      (node (ref "R263") (pin "2") (pinfunction "2_2") (pintype "passive"))
    )
    (net (code "115") (name "Net-(U1-SET)") (class "Default")
      (node (ref "R2") (pin "2") (pinfunction "2_2") (pintype "passive"))
      (node (ref "U1") (pin "5") (pinfunction "SET_5") (pintype "input"))
    )
    (net (code "116") (name "Net-(U5-IO6)") (class "Default")
      (node (ref "R69") (pin "1") (pinfunction "1_1") (pintype "passive"))
      (node (ref "R70") (pin "1") (pinfunction "1_1") (pintype "passive"))
      (node (ref "TP28") (pin "1") (pinfunction "1_1") (pintype "passive"))
      (node (ref "U5") (pin "11") (pinfunction "IO6_11") (pintype "bidirectional"))
    )
    (net (code "117") (name "Net-(U5-IO7)") (class "Default")
      (node (ref "TP24") (pin "1") (pinfunction "1_1") (pintype "passive"))
      (node (ref "U5") (pin "12") (pinfunction "IO7_12") (pintype "bidirectional"))
    )
    (net (code "118") (name "Net-(U5-~{RESET})") (class "Default")
      (node (ref "R54") (pin "1") (pinfunction "1_1") (pintype "passive"))
      (node (ref "U5") (pin "13") (pinfunction "~{RESET}_13") (pintype "input"))
    )
    (net (code "119") (name "Net-(U6-CIN1+)") (class "Default")
      (node (ref "R59") (pin "1") (pinfunction "1_1") (pintype "passive"))
      (node (ref "R60") (pin "2") (pinfunction "2_2") (pintype "passive"))
      (node (ref "TP15") (pin "1") (pinfunction "1_1") (pintype "passive"))
      (node (ref "U6") (pin "10") (pinfunction "CIN1+_10") (pintype "input"))
    )
    (net (code "120") (name "Net-(U6-CIN1-)") (class "Default")
      (node (ref "R61") (pin "1") (pinfunction "1_1") (pintype "passive"))
      (node (ref "R62") (pin "2") (pinfunction "2_2") (pintype "passive"))
      (node (ref "TP4") (pin "1") (pinfunction "1_1") (pintype "passive"))
      (node (ref "U6") (pin "11") (pinfunction "CIN1-_11") (pintype "input"))
    )
    (net (code "121") (name "Net-(U6-CIN2+)") (class "Default")
      (node (ref "R61") (pin "2") (pinfunction "2_2") (pintype "passive"))
      (node (ref "U6") (pin "12") (pinfunction "REF_12") (pintype "output"))
      (node (ref "U6") (pin "8") (pinfunction "CIN2+_8") (pintype "input"))
    )
    (net (code "122") (name "Net-(U6-INHIBIT)") (class "Default")
      (node (ref "R65") (pin "1") (pinfunction "1_1") (pintype "passive"))
      (node (ref "U6") (pin "5") (pinfunction "INHIBIT_5") (pintype "input"))
    )
    (net (code "123") (name "Net-(U6-IOUT)") (class "Default")
      (node (ref "R59") (pin "2") (pinfunction "2_2") (pintype "passive"))
      (node (ref "U6") (pin "14") (pinfunction "IOUT_14") (pintype "output"))
    )
    (net (code "124") (name "Net-(U6-RS+)") (class "Default")
      (node (ref "Q7") (pin "1") (pinfunction "D_1") (pintype "passive"))
      (node (ref "Q7") (pin "2") (pinfunction "D_2") (pintype "passive"))
      (node (ref "Q7") (pin "5") (pinfunction "D_5") (pintype "passive"))
      (node (ref "Q7") (pin "6") (pinfunction "D_6") (pintype "passive"))
      (node (ref "R57") (pin "1") (pinfunction "1_1") (pintype "passive"))
      (node (ref "U6") (pin "16") (pinfunction "RS+_16") (pintype "passive"))
    )
    (net (code "125") (name "Net-(U7-INP)") (class "Default")
      (node (ref "C10") (pin "1") (pinfunction "1_1") (pintype "passive"))
      (node (ref "R75") (pin "1") (pinfunction "1_1") (pintype "passive"))
      (node (ref "R76") (pin "1") (pinfunction "1_1") (pintype "passive"))
      (node (ref "U7") (pin "1") (pinfunction "INP_1") (pintype "input"))
    )
    (net (code "126") (name "Net-(U7-OUT)") (class "Default")
      (node (ref "R74") (pin "1") (pinfunction "1_1") (pintype "passive"))
      (node (ref "TP30") (pin "1") (pinfunction "1_1") (pintype "passive"))
      (node (ref "U7") (pin "4") (pinfunction "OUT_4") (pintype "output"))
    )
    (net (code "127") (name "Net-(U8-INP)") (class "Default")
      (node (ref "C9") (pin "1") (pinfunction "1_1") (pintype "passive"))
      (node (ref "R71") (pin "1") (pinfunction "1_1") (pintype "passive"))
      (node (ref "R72") (pin "1") (pinfunction "1_1") (pintype "passive"))
      (node (ref "U8") (pin "1") (pinfunction "INP_1") (pintype "input"))
    )
    (net (code "128") (name "Net-(U8-OUT)") (class "Default")
      (node (ref "R68") (pin "1") (pinfunction "1_1") (pintype "passive"))
      (node (ref "TP29") (pin "1") (pinfunction "1_1") (pintype "passive"))
      (node (ref "U8") (pin "4") (pinfunction "OUT_4") (pintype "output"))
    )
    (net (code "129") (name "Net-(U9-IO6)") (class "Default")
      (node (ref "R107") (pin "1") (pinfunction "1_1") (pintype "passive"))
      (node (ref "R108") (pin "1") (pinfunction "1_1") (pintype "passive"))
      (node (ref "TP43") (pin "1") (pinfunction "1_1") (pintype "passive"))
      (node (ref "U9") (pin "11") (pinfunction "IO6_11") (pintype "bidirectional"))
    )
    (net (code "130") (name "Net-(U9-IO7)") (class "Default")
      (node (ref "TP39") (pin "1") (pinfunction "1_1") (pintype "passive"))
      (node (ref "U9") (pin "12") (pinfunction "IO7_12") (pintype "bidirectional"))
    )
    (net (code "131") (name "Net-(U9-~{RESET})") (class "Default")
      (node (ref "R92") (pin "1") (pinfunction "1_1") (pintype "passive"))
      (node (ref "U9") (pin "13") (pinfunction "~{RESET}_13") (pintype "input"))
    )
    (net (code "132") (name "Net-(U10-CIN1+)") (class "Default")
      (node (ref "R97") (pin "1") (pinfunction "1_1") (pintype "passive"))
      (node (ref "R98") (pin "2") (pinfunction "2_2") (pintype "passive"))
      (node (ref "TP33") (pin "1") (pinfunction "1_1") (pintype "passive"))
      (node (ref "U10") (pin "10") (pinfunction "CIN1+_10") (pintype "input"))
    )
    (net (code "133") (name "Net-(U10-CIN1-)") (class "Default")
      (node (ref "R100") (pin "2") (pinfunction "2_2") (pintype "passive"))
      (node (ref "R99") (pin "1") (pinfunction "1_1") (pintype "passive"))
      (node (ref "TP32") (pin "1") (pinfunction "1_1") (pintype "passive"))
      (node (ref "U10") (pin "11") (pinfunction "CIN1-_11") (pintype "input"))
    )
    (net (code "134") (name "Net-(U10-CIN2+)") (class "Default")
      (node (ref "R99") (pin "2") (pinfunction "2_2") (pintype "passive"))
      (node (ref "U10") (pin "12") (pinfunction "REF_12") (pintype "output"))
      (node (ref "U10") (pin "8") (pinfunction "CIN2+_8") (pintype "input"))
    )
    (net (code "135") (name "Net-(U10-INHIBIT)") (class "Default")
      (node (ref "R103") (pin "1") (pinfunction "1_1") (pintype "passive"))
      (node (ref "U10") (pin "5") (pinfunction "INHIBIT_5") (pintype "input"))
    )
    (net (code "136") (name "Net-(U10-IOUT)") (class "Default")
      (node (ref "R97") (pin "2") (pinfunction "2_2") (pintype "passive"))
      (node (ref "U10") (pin "14") (pinfunction "IOUT_14") (pintype "output"))
    )
    (net (code "137") (name "Net-(U10-RS+)") (class "Default")
      (node (ref "Q12") (pin "1") (pinfunction "D_1") (pintype "passive"))
      (node (ref "Q12") (pin "2") (pinfunction "D_2") (pintype "passive"))
      (node (ref "Q12") (pin "5") (pinfunction "D_5") (pintype "passive"))
      (node (ref "Q12") (pin "6") (pinfunction "D_6") (pintype "passive"))
      (node (ref "R95") (pin "1") (pinfunction "1_1") (pintype "passive"))
      (node (ref "U10") (pin "16") (pinfunction "RS+_16") (pintype "passive"))
    )
    (net (code "138") (name "Net-(U11-INP)") (class "Default")
      (node (ref "C15") (pin "1") (pinfunction "1_1") (pintype "passive"))
      (node (ref "R113") (pin "1") (pinfunction "1_1") (pintype "passive"))
      (node (ref "R114") (pin "1") (pinfunction "1_1") (pintype "passive"))
      (node (ref "U11") (pin "1") (pinfunction "INP_1") (pintype "input"))
    )
    (net (code "139") (name "Net-(U11-OUT)") (class "Default")
      (node (ref "R112") (pin "1") (pinfunction "1_1") (pintype "passive"))
      (node (ref "TP45") (pin "1") (pinfunction "1_1") (pintype "passive"))
      (node (ref "U11") (pin "4") (pinfunction "OUT_4") (pintype "output"))
    )
    (net (code "140") (name "Net-(U12-INP)") (class "Default")
      (node (ref "C14") (pin "1") (pinfunction "1_1") (pintype "passive"))
      (node (ref "R109") (pin "1") (pinfunction "1_1") (pintype "passive"))
      (node (ref "R110") (pin "1") (pinfunction "1_1") (pintype "passive"))
      (node (ref "U12") (pin "1") (pinfunction "INP_1") (pintype "input"))
    )
    (net (code "141") (name "Net-(U12-OUT)") (class "Default")
      (node (ref "R106") (pin "1") (pinfunction "1_1") (pintype "passive"))
      (node (ref "TP44") (pin "1") (pinfunction "1_1") (pintype "passive"))
      (node (ref "U12") (pin "4") (pinfunction "OUT_4") (pintype "output"))
    )
    (net (code "142") (name "Net-(U13-SDO1)") (class "Default")
      (node (ref "R5") (pin "2") (pinfunction "2_2") (pintype "passive"))
      (node (ref "U13") (pin "15") (pinfunction "SDO1_15") (pintype "bidirectional"))
    )
    (net (code "143") (name "Net-(U13-SDO2)") (class "Default")
      (node (ref "R4") (pin "2") (pinfunction "2_2") (pintype "passive"))
      (node (ref "U13") (pin "10") (pinfunction "SDO2_10") (pintype "bidirectional"))
    )
    (net (code "144") (name "Net-(U15-PF0-OSC_IN)") (class "Default")
      (node (ref "C36") (pin "1") (pinfunction "1_1") (pintype "passive"))
      (node (ref "U15") (pin "5") (pinfunction "PF0-OSC_IN_5") (pintype "bidirectional"))
      (node (ref "X2") (pin "1") (pinfunction "1_1") (pintype "passive"))
    )
    (net (code "145") (name "Net-(U15-PF1-OSC_OUT)") (class "Default")
      (node (ref "C30") (pin "1") (pinfunction "1_1") (pintype "passive"))
      (node (ref "U15") (pin "6") (pinfunction "PF1-OSC_OUT_6") (pintype "bidirectional"))
      (node (ref "X2") (pin "3") (pinfunction "2_3") (pintype "passive"))
    )
    (net (code "146") (name "Net-(U17-IO6)") (class "Default")
      (node (ref "R183") (pin "1") (pinfunction "1_1") (pintype "passive"))
      (node (ref "R184") (pin "1") (pinfunction "1_1") (pintype "passive"))
      (node (ref "TP73") (pin "1") (pinfunction "1_1") (pintype "passive"))
      (node (ref "U17") (pin "11") (pinfunction "IO6_11") (pintype "bidirectional"))
    )
    (net (code "147") (name "Net-(U17-IO7)") (class "Default")
      (node (ref "TP69") (pin "1") (pinfunction "1_1") (pintype "passive"))
      (node (ref "U17") (pin "12") (pinfunction "IO7_12") (pintype "bidirectional"))
    )
    (net (code "148") (name "Net-(U17-~{RESET})") (class "Default")
      (node (ref "R168") (pin "1") (pinfunction "1_1") (pintype "passive"))
      (node (ref "U17") (pin "13") (pinfunction "~{RESET}_13") (pintype "input"))
    )
    (net (code "149") (name "Net-(U18-CIN1+)") (class "Default")
      (node (ref "R173") (pin "1") (pinfunction "1_1") (pintype "passive"))
      (node (ref "R174") (pin "2") (pinfunction "2_2") (pintype "passive"))
      (node (ref "TP63") (pin "1") (pinfunction "1_1") (pintype "passive"))
      (node (ref "U18") (pin "10") (pinfunction "CIN1+_10") (pintype "input"))
    )
    (net (code "150") (name "Net-(U18-CIN1-)") (class "Default")
      (node (ref "R175") (pin "1") (pinfunction "1_1") (pintype "passive"))
      (node (ref "R176") (pin "2") (pinfunction "2_2") (pintype "passive"))
      (node (ref "TP62") (pin "1") (pinfunction "1_1") (pintype "passive"))
      (node (ref "U18") (pin "11") (pinfunction "CIN1-_11") (pintype "input"))
    )
    (net (code "151") (name "Net-(U18-CIN2+)") (class "Default")
      (node (ref "R175") (pin "2") (pinfunction "2_2") (pintype "passive"))
      (node (ref "U18") (pin "12") (pinfunction "REF_12") (pintype "output"))
      (node (ref "U18") (pin "8") (pinfunction "CIN2+_8") (pintype "input"))
    )
    (net (code "152") (name "Net-(U18-INHIBIT)") (class "Default")
      (node (ref "R179") (pin "1") (pinfunction "1_1") (pintype "passive"))
      (node (ref "U18") (pin "5") (pinfunction "INHIBIT_5") (pintype "input"))
    )
    (net (code "153") (name "Net-(U18-IOUT)") (class "Default")
      (node (ref "R173") (pin "2") (pinfunction "2_2") (pintype "passive"))
      (node (ref "U18") (pin "14") (pinfunction "IOUT_14") (pintype "output"))
    )
    (net (code "154") (name "Net-(U18-RS+)") (class "Default")
      (node (ref "Q22") (pin "1") (pinfunction "D_1") (pintype "passive"))
      (node (ref "Q22") (pin "2") (pinfunction "D_2") (pintype "passive"))
      (node (ref "Q22") (pin "5") (pinfunction "D_5") (pintype "passive"))
      (node (ref "Q22") (pin "6") (pinfunction "D_6") (pintype "passive"))
      (node (ref "R171") (pin "1") (pinfunction "1_1") (pintype "passive"))
      (node (ref "U18") (pin "16") (pinfunction "RS+_16") (pintype "passive"))
    )
    (net (code "155") (name "Net-(U19-INP)") (class "Default")
      (node (ref "C25") (pin "1") (pinfunction "1_1") (pintype "passive"))
      (node (ref "R189") (pin "1") (pinfunction "1_1") (pintype "passive"))
      (node (ref "R190") (pin "1") (pinfunction "1_1") (pintype "passive"))
      (node (ref "U19") (pin "1") (pinfunction "INP_1") (pintype "input"))
    )
    (net (code "156") (name "Net-(U19-OUT)") (class "Default")
      (node (ref "R188") (pin "1") (pinfunction "1_1") (pintype "passive"))
      (node (ref "TP75") (pin "1") (pinfunction "1_1") (pintype "passive"))
      (node (ref "U19") (pin "4") (pinfunction "OUT_4") (pintype "output"))
    )
    (net (code "157") (name "Net-(U20-INP)") (class "Default")
      (node (ref "C24") (pin "1") (pinfunction "1_1") (pintype "passive"))
      (node (ref "R185") (pin "1") (pinfunction "1_1") (pintype "passive"))
      (node (ref "R186") (pin "1") (pinfunction "1_1") (pintype "passive"))
      (node (ref "U20") (pin "1") (pinfunction "INP_1") (pintype "input"))
    )
    (net (code "158") (name "Net-(U20-OUT)") (class "Default")
      (node (ref "R182") (pin "1") (pinfunction "1_1") (pintype "passive"))
      (node (ref "TP74") (pin "1") (pinfunction "1_1") (pintype "passive"))
      (node (ref "U20") (pin "4") (pinfunction "OUT_4") (pintype "output"))
    )
    (net (code "159") (name "Net-(U25-IO6)") (class "Default")
      (node (ref "R259") (pin "1") (pinfunction "1_1") (pintype "passive"))
      (node (ref "R260") (pin "1") (pinfunction "1_1") (pintype "passive"))
      (node (ref "TP103") (pin "1") (pinfunction "1_1") (pintype "passive"))
      (node (ref "U25") (pin "11") (pinfunction "IO6_11") (pintype "bidirectional"))
    )
    (net (code "160") (name "Net-(U25-IO7)") (class "Default")
      (node (ref "TP99") (pin "1") (pinfunction "1_1") (pintype "passive"))
      (node (ref "U25") (pin "12") (pinfunction "IO7_12") (pintype "bidirectional"))
    )
    (net (code "161") (name "Net-(U25-~{RESET})") (class "Default")
      (node (ref "R244") (pin "1") (pinfunction "1_1") (pintype "passive"))
      (node (ref "U25") (pin "13") (pinfunction "~{RESET}_13") (pintype "input"))
    )
    (net (code "162") (name "Net-(U26-CIN1+)") (class "Default")
      (node (ref "R249") (pin "1") (pinfunction "1_1") (pintype "passive"))
      (node (ref "R250") (pin "2") (pinfunction "2_2") (pintype "passive"))
      (node (ref "TP93") (pin "1") (pinfunction "1_1") (pintype "passive"))
      (node (ref "U26") (pin "10") (pinfunction "CIN1+_10") (pintype "input"))
    )
    (net (code "163") (name "Net-(U26-CIN1-)") (class "Default")
      (node (ref "R251") (pin "1") (pinfunction "1_1") (pintype "passive"))
      (node (ref "R252") (pin "2") (pinfunction "2_2") (pintype "passive"))
      (node (ref "TP92") (pin "1") (pinfunction "1_1") (pintype "passive"))
      (node (ref "U26") (pin "11") (pinfunction "CIN1-_11") (pintype "input"))
    )
    (net (code "164") (name "Net-(U26-CIN2+)") (class "Default")
      (node (ref "R251") (pin "2") (pinfunction "2_2") (pintype "passive"))
      (node (ref "U26") (pin "12") (pinfunction "REF_12") (pintype "output"))
      (node (ref "U26") (pin "8") (pinfunction "CIN2+_8") (pintype "input"))
    )
    (net (code "165") (name "Net-(U26-INHIBIT)") (class "Default")
      (node (ref "R255") (pin "1") (pinfunction "1_1") (pintype "passive"))
      (node (ref "U26") (pin "5") (pinfunction "INHIBIT_5") (pintype "input"))
    )
    (net (code "166") (name "Net-(U26-IOUT)") (class "Default")
      (node (ref "R249") (pin "2") (pinfunction "2_2") (pintype "passive"))
      (node (ref "U26") (pin "14") (pinfunction "IOUT_14") (pintype "output"))
    )
    (net (code "167") (name "Net-(U26-RS+)") (class "Default")
      (node (ref "Q32") (pin "1") (pinfunction "D_1") (pintype "passive"))
      (node (ref "Q32") (pin "2") (pinfunction "D_2") (pintype "passive"))
      (node (ref "Q32") (pin "5") (pinfunction "D_5") (pintype "passive"))
      (node (ref "Q32") (pin "6") (pinfunction "D_6") (pintype "passive"))
      (node (ref "R247") (pin "1") (pinfunction "1_1") (pintype "passive"))
      (node (ref "U26") (pin "16") (pinfunction "RS+_16") (pintype "passive"))
    )
    (net (code "168") (name "Net-(U27-INP)") (class "Default")
      (node (ref "C35") (pin "1") (pinfunction "1_1") (pintype "passive"))
      (node (ref "R265") (pin "1") (pinfunction "1_1") (pintype "passive"))
      (node (ref "R266") (pin "1") (pinfunction "1_1") (pintype "passive"))
      (node (ref "U27") (pin "1") (pinfunction "INP_1") (pintype "input"))
    )
    (net (code "169") (name "Net-(U27-OUT)") (class "Default")
      (node (ref "R264") (pin "1") (pinfunction "1_1") (pintype "passive"))
      (node (ref "TP105") (pin "1") (pinfunction "1_1") (pintype "passive"))
      (node (ref "U27") (pin "4") (pinfunction "OUT_4") (pintype "output"))
    )
    (net (code "170") (name "Net-(U28-INP)") (class "Default")
      (node (ref "C34") (pin "1") (pinfunction "1_1") (pintype "passive"))
      (node (ref "R261") (pin "1") (pinfunction "1_1") (pintype "passive"))
      (node (ref "R262") (pin "1") (pinfunction "1_1") (pintype "passive"))
      (node (ref "U28") (pin "1") (pinfunction "INP_1") (pintype "input"))
    )
    (net (code "171") (name "Net-(U28-OUT)") (class "Default")
      (node (ref "R258") (pin "1") (pinfunction "1_1") (pintype "passive"))
      (node (ref "TP104") (pin "1") (pinfunction "1_1") (pintype "passive"))
      (node (ref "U28") (pin "4") (pinfunction "OUT_4") (pintype "output"))
    )
    (net (code "172") (name "Net-(U29-IO6)") (class "Default")
      (node (ref "TP119") (pin "1") (pinfunction "1_1") (pintype "passive"))
      (node (ref "U29") (pin "11") (pinfunction "IO6_11") (pintype "bidirectional"))
    )
    (net (code "173") (name "Net-(U29-IO7)") (class "Default")
      (node (ref "TP115") (pin "1") (pinfunction "1_1") (pintype "passive"))
      (node (ref "U29") (pin "12") (pinfunction "IO7_12") (pintype "bidirectional"))
    )
    (net (code "174") (name "Net-(U29-~{RESET})") (class "Default")
      (node (ref "R214") (pin "1") (pinfunction "1_1") (pintype "passive"))
      (node (ref "U29") (pin "13") (pinfunction "~{RESET}_13") (pintype "input"))
    )
    (net (code "175") (name "Net-(U30-CIN1+)") (class "Default")
      (node (ref "R219") (pin "1") (pinfunction "1_1") (pintype "passive"))
      (node (ref "R220") (pin "2") (pinfunction "2_2") (pintype "passive"))
      (node (ref "TP106") (pin "1") (pinfunction "1_1") (pintype "passive"))
      (node (ref "U30") (pin "10") (pinfunction "CIN1+_10") (pintype "input"))
    )
    (net (code "176") (name "Net-(U30-CIN1-)") (class "Default")
      (node (ref "R221") (pin "1") (pinfunction "1_1") (pintype "passive"))
      (node (ref "R222") (pin "2") (pinfunction "2_2") (pintype "passive"))
      (node (ref "TP90") (pin "1") (pinfunction "1_1") (pintype "passive"))
      (node (ref "U30") (pin "11") (pinfunction "CIN1-_11") (pintype "input"))
    )
    (net (code "177") (name "Net-(U30-CIN2+)") (class "Default")
      (node (ref "R221") (pin "2") (pinfunction "2_2") (pintype "passive"))
      (node (ref "U30") (pin "12") (pinfunction "REF_12") (pintype "output"))
      (node (ref "U30") (pin "8") (pinfunction "CIN2+_8") (pintype "input"))
    )
    (net (code "178") (name "Net-(U30-INHIBIT)") (class "Default")
      (node (ref "R225") (pin "1") (pinfunction "1_1") (pintype "passive"))
      (node (ref "U30") (pin "5") (pinfunction "INHIBIT_5") (pintype "input"))
    )
    (net (code "179") (name "Net-(U30-IOUT)") (class "Default")
      (node (ref "R219") (pin "2") (pinfunction "2_2") (pintype "passive"))
      (node (ref "U30") (pin "14") (pinfunction "IOUT_14") (pintype "output"))
    )
    (net (code "180") (name "Net-(U30-RS+)") (class "Default")
      (node (ref "Q27") (pin "1") (pinfunction "D_1") (pintype "passive"))
      (node (ref "Q27") (pin "2") (pinfunction "D_2") (pintype "passive"))
      (node (ref "Q27") (pin "5") (pinfunction "D_5") (pintype "passive"))
      (node (ref "Q27") (pin "6") (pinfunction "D_6") (pintype "passive"))
      (node (ref "R217") (pin "1") (pinfunction "1_1") (pintype "passive"))
      (node (ref "U30") (pin "16") (pinfunction "RS+_16") (pintype "passive"))
    )
    (net (code "181") (name "Net-(U31-PG)") (class "Default")
      (node (ref "TP111") (pin "1") (pinfunction "1_1") (pintype "passive"))
      (node (ref "U31") (pin "13") (pinfunction "PG_13") (pintype "open_collector"))
    )
    (net (code "182") (name "Net-(U31-SYNC)") (class "Default")
      (node (ref "R227") (pin "1") (pinfunction "1_1") (pintype "passive"))
      (node (ref "R228") (pin "2") (pinfunction "2_2") (pintype "passive"))
      (node (ref "TP112") (pin "1") (pinfunction "1_1") (pintype "passive"))
      (node (ref "U31") (pin "5") (pinfunction "SYNC_5") (pintype "input"))
    )
    (net (code "183") (name "Net-(U32-INP)") (class "Default")
      (node (ref "C50") (pin "1") (pinfunction "1_1") (pintype "passive"))
      (node (ref "R273") (pin "1") (pinfunction "1_1") (pintype "passive"))
      (node (ref "R274") (pin "1") (pinfunction "1_1") (pintype "passive"))
      (node (ref "U32") (pin "1") (pinfunction "INP_1") (pintype "input"))
    )
    (net (code "184") (name "Net-(U32-OUT)") (class "Default")
      (node (ref "R272") (pin "1") (pinfunction "1_1") (pintype "passive"))
      (node (ref "TP121") (pin "1") (pinfunction "1_1") (pintype "passive"))
      (node (ref "U32") (pin "4") (pinfunction "OUT_4") (pintype "output"))
    )
    (net (code "185") (name "Net-(U33-INP)") (class "Default")
      (node (ref "C49") (pin "1") (pinfunction "1_1") (pintype "passive"))
      (node (ref "R269") (pin "1") (pinfunction "1_1") (pintype "passive"))
      (node (ref "R270") (pin "1") (pinfunction "1_1") (pintype "passive"))
      (node (ref "U33") (pin "1") (pinfunction "INP_1") (pintype "input"))
    )
    (net (code "186") (name "Net-(U33-OUT)") (class "Default")
      (node (ref "R268") (pin "1") (pinfunction "1_1") (pintype "passive"))
      (node (ref "TP120") (pin "1") (pinfunction "1_1") (pintype "passive"))
      (node (ref "U33") (pin "4") (pinfunction "OUT_4") (pintype "output"))
    )
    (net (code "187") (name "ON{slash}~{OFF_Q1}") (class "Default")
      (node (ref "C13") (pin "1") (pinfunction "1_1") (pintype "passive"))
      (node (ref "Q13") (pin "1") (pinfunction "G_1") (pintype "passive"))
      (node (ref "R105") (pin "2") (pinfunction "2_2") (pintype "passive"))
      (node (ref "R94") (pin "2") (pinfunction "2_2") (pintype "passive"))
      (node (ref "TP34") (pin "1") (pinfunction "1_1") (pintype "passive"))
      (node (ref "U10") (pin "1") (pinfunction "VCC_1") (pintype "power_in"))
      (node (ref "U9") (pin "8") (pinfunction "IO3_8") (pintype "bidirectional"))
    )
    (net (code "188") (name "ON{slash}~{OFF_Q2}") (class "Default")
      (node (ref "C23") (pin "1") (pinfunction "1_1") (pintype "passive"))
      (node (ref "Q23") (pin "1") (pinfunction "G_1") (pintype "passive"))
      (node (ref "R170") (pin "2") (pinfunction "2_2") (pintype "passive"))
      (node (ref "R181") (pin "2") (pinfunction "2_2") (pintype "passive"))
      (node (ref "TP64") (pin "1") (pinfunction "1_1") (pintype "passive"))
      (node (ref "U17") (pin "8") (pinfunction "IO3_8") (pintype "bidirectional"))
      (node (ref "U18") (pin "1") (pinfunction "VCC_1") (pintype "power_in"))
    )
    (net (code "189") (name "ON{slash}~{OFF_Q3}") (class "Default")
      (node (ref "C33") (pin "1") (pinfunction "1_1") (pintype "passive"))
      (node (ref "Q33") (pin "1") (pinfunction "G_1") (pintype "passive"))
      (node (ref "R246") (pin "2") (pinfunction "2_2") (pintype "passive"))
      (node (ref "R257") (pin "2") (pinfunction "2_2") (pintype "passive"))
      (node (ref "TP94") (pin "1") (pinfunction "1_1") (pintype "passive"))
      (node (ref "U25") (pin "8") (pinfunction "IO3_8") (pintype "bidirectional"))
      (node (ref "U26") (pin "1") (pinfunction "VCC_1") (pintype "power_in"))
    )
    (net (code "190") (name "ON{slash}~{OFF_Q4}") (class "Default")
      (node (ref "C8") (pin "1") (pinfunction "1_1") (pintype "passive"))
      (node (ref "Q8") (pin "1") (pinfunction "G_1") (pintype "passive"))
      (node (ref "R56") (pin "2") (pinfunction "2_2") (pintype "passive"))
      (node (ref "R67") (pin "2") (pinfunction "2_2") (pintype "passive"))
      (node (ref "TP16") (pin "1") (pinfunction "1_1") (pintype "passive"))
      (node (ref "U5") (pin "8") (pinfunction "IO3_8") (pintype "bidirectional"))
      (node (ref "U6") (pin "1") (pinfunction "VCC_1") (pintype "power_in"))
    )
    (net (code "191") (name "ON{slash}~{OFF}") (class "Default")
      (node (ref "C48") (pin "1") (pinfunction "1_1") (pintype "passive"))
      (node (ref "Q28") (pin "1") (pinfunction "G_1") (pintype "passive"))
      (node (ref "R216") (pin "2") (pinfunction "2_2") (pintype "passive"))
      (node (ref "R267") (pin "2") (pinfunction "2_2") (pintype "passive"))
      (node (ref "TP107") (pin "1") (pinfunction "1_1") (pintype "passive"))
      (node (ref "U29") (pin "8") (pinfunction "IO3_8") (pintype "bidirectional"))
      (node (ref "U30") (pin "1") (pinfunction "VCC_1") (pintype "power_in"))
    )
    (net (code "192") (name "OPD_PWR") (class "Default")
      (node (ref "J6") (pin "15") (pinfunction "15_15") (pintype "passive"))
      (node (ref "J6") (pin "16") (pinfunction "16_16") (pintype "passive"))
      (node (ref "R154") (pin "1") (pinfunction "1_1") (pintype "passive"))
      (node (ref "R200") (pin "1") (pinfunction "1_1") (pintype "passive"))
      (node (ref "R230") (pin "1") (pinfunction "1_1") (pintype "passive"))
      (node (ref "R40") (pin "1") (pinfunction "1_1") (pintype "passive"))
      (node (ref "R78") (pin "1") (pinfunction "1_1") (pintype "passive"))
    )
    (net (code "193") (name "OPD_SCL") (class "Default")
      (node (ref "J6") (pin "13") (pinfunction "13_13") (pintype "passive"))
      (node (ref "J6") (pin "14") (pinfunction "14_14") (pintype "passive"))
      (node (ref "R111") (pin "1") (pinfunction "1_1") (pintype "passive"))
      (node (ref "R187") (pin "1") (pinfunction "1_1") (pintype "passive"))
      (node (ref "R263") (pin "1") (pinfunction "1_1") (pintype "passive"))
      (node (ref "R271") (pin "1") (pinfunction "1_1") (pintype "passive"))
      (node (ref "R73") (pin "1") (pinfunction "1_1") (pintype "passive"))
    )
    (net (code "194") (name "OPD_SDA") (class "Default")
      (node (ref "J6") (pin "11") (pinfunction "11_11") (pintype "passive"))
      (node (ref "J6") (pin "12") (pinfunction "12_12") (pintype "passive"))
      (node (ref "R167") (pin "1") (pinfunction "1_1") (pintype "passive"))
      (node (ref "R213") (pin "1") (pinfunction "1_1") (pintype "passive"))
      (node (ref "R243") (pin "1") (pinfunction "1_1") (pintype "passive"))
      (node (ref "R53") (pin "1") (pinfunction "1_1") (pintype "passive"))
      (node (ref "R91") (pin "1") (pinfunction "1_1") (pintype "passive"))
    )
    (net (code "195") (name "PA0") (class "Default")
      (node (ref "R8") (pin "2") (pinfunction "2_2") (pintype "passive"))
      (node (ref "U15") (pin "10") (pinfunction "PA0_10") (pintype "bidirectional"))
    )
    (net (code "196") (name "PA2{slash}USART2_TX") (class "Default")
      (node (ref "J2") (pin "13") (pinfunction "CARD-TX_13") (pintype "passive"))
      (node (ref "U15") (pin "12") (pinfunction "PA2_12") (pintype "bidirectional"))
    )
    (net (code "197") (name "PA3{slash}USART2_RX") (class "Default")
      (node (ref "J2") (pin "12") (pinfunction "CARD-RX_12") (pintype "passive"))
      (node (ref "U15") (pin "13") (pinfunction "PA3_13") (pintype "bidirectional"))
    )
    (net (code "198") (name "PA8{slash}POUTPROT") (class "Default")
      (node (ref "R9") (pin "2") (pinfunction "2_2") (pintype "passive"))
      (node (ref "U15") (pin "29") (pinfunction "PA8_29") (pintype "bidirectional"))
    )
    (net (code "199") (name "PA9{slash}CAN_SILENT") (class "Default")
      (node (ref "U14") (pin "8") (pinfunction "S_8") (pintype "input"))
      (node (ref "U15") (pin "30") (pinfunction "PA9_30") (pintype "bidirectional"))
    )
    (net (code "200") (name "PB6{slash}SCL") (class "Default")
      (node (ref "R11") (pin "1") (pinfunction "1_1") (pintype "passive"))
      (node (ref "TP8") (pin "1") (pinfunction "1_1") (pintype "passive"))
      (node (ref "U13") (pin "8") (pinfunction "SCL/SCK_8") (pintype "input"))
      (node (ref "U15") (pin "42") (pinfunction "PB6_42") (pintype "bidirectional"))
      (node (ref "U2") (pin "2") (pinfunction "SCLOUT_2") (pintype "output"))
      (node (ref "U29") (pin "4") (pinfunction "IO0_4") (pintype "bidirectional"))
    )
    (net (code "201") (name "PB6{slash}SCL_Q1") (class "Default")
      (node (ref "QUADRANT1") (pin "P$24") (pinfunction "I2C_SCL_P$24") (pintype "bidirectional"))
      (node (ref "QUADRANT1") (pin "P$7") (pinfunction "I2C_SCL_P$7") (pintype "bidirectional"))
      (node (ref "R108") (pin "2") (pinfunction "2_2") (pintype "passive"))
      (node (ref "U9") (pin "4") (pinfunction "IO0_4") (pintype "bidirectional"))
    )
    (net (code "202") (name "PB6{slash}SCL_Q2") (class "Default")
      (node (ref "QUADRANT2") (pin "P$24") (pinfunction "I2C_SCL_P$24") (pintype "bidirectional"))
      (node (ref "QUADRANT2") (pin "P$7") (pinfunction "I2C_SCL_P$7") (pintype "bidirectional"))
      (node (ref "R184") (pin "2") (pinfunction "2_2") (pintype "passive"))
      (node (ref "U17") (pin "4") (pinfunction "IO0_4") (pintype "bidirectional"))
    )
    (net (code "203") (name "PB6{slash}SCL_Q3") (class "Default")
      (node (ref "QUADRANT3") (pin "P$24") (pinfunction "I2C_SCL_P$24") (pintype "bidirectional"))
      (node (ref "QUADRANT3") (pin "P$7") (pinfunction "I2C_SCL_P$7") (pintype "bidirectional"))
      (node (ref "R260") (pin "2") (pinfunction "2_2") (pintype "passive"))
      (node (ref "U25") (pin "4") (pinfunction "IO0_4") (pintype "bidirectional"))
    )
    (net (code "204") (name "PB6{slash}SCL_Q4") (class "Default")
      (node (ref "QUADRANT4") (pin "P$24") (pinfunction "I2C_SCL_P$24") (pintype "bidirectional"))
      (node (ref "QUADRANT4") (pin "P$7") (pinfunction "I2C_SCL_P$7") (pintype "bidirectional"))
      (node (ref "R70") (pin "2") (pinfunction "2_2") (pintype "passive"))
      (node (ref "U5") (pin "4") (pinfunction "IO0_4") (pintype "bidirectional"))
    )
    (net (code "205") (name "PB7{slash}SDA") (class "Default")
      (node (ref "R12") (pin "1") (pinfunction "1_1") (pintype "passive"))
      (node (ref "TP18") (pin "1") (pinfunction "1_1") (pintype "passive"))
      (node (ref "U13") (pin "9") (pinfunction "SDA/SDI_9") (pintype "bidirectional"))
      (node (ref "U15") (pin "43") (pinfunction "PB7_43") (pintype "bidirectional"))
      (node (ref "U2") (pin "7") (pinfunction "SDAOUT_7") (pintype "output"))
      (node (ref "U29") (pin "5") (pinfunction "IO1_5") (pintype "bidirectional"))
    )
    (net (code "206") (name "PB7{slash}SDA_Q1") (class "Default")
      (node (ref "QUADRANT1") (pin "P$23") (pinfunction "I2C_SDA_P$23") (pintype "bidirectional"))
      (node (ref "QUADRANT1") (pin "P$8") (pinfunction "I2C_SDA_P$8") (pintype "bidirectional"))
      (node (ref "R107") (pin "2") (pinfunction "2_2") (pintype "passive"))
      (node (ref "U9") (pin "5") (pinfunction "IO1_5") (pintype "bidirectional"))
    )
    (net (code "207") (name "PB7{slash}SDA_Q2") (class "Default")
      (node (ref "QUADRANT2") (pin "P$23") (pinfunction "I2C_SDA_P$23") (pintype "bidirectional"))
      (node (ref "QUADRANT2") (pin "P$8") (pinfunction "I2C_SDA_P$8") (pintype "bidirectional"))
      (node (ref "R183") (pin "2") (pinfunction "2_2") (pintype "passive"))
      (node (ref "U17") (pin "5") (pinfunction "IO1_5") (pintype "bidirectional"))
    )
    (net (code "208") (name "PB7{slash}SDA_Q3") (class "Default")
      (node (ref "QUADRANT3") (pin "P$23") (pinfunction "I2C_SDA_P$23") (pintype "bidirectional"))
      (node (ref "QUADRANT3") (pin "P$8") (pinfunction "I2C_SDA_P$8") (pintype "bidirectional"))
      (node (ref "R259") (pin "2") (pinfunction "2_2") (pintype "passive"))
      (node (ref "U25") (pin "5") (pinfunction "IO1_5") (pintype "bidirectional"))
    )
    (net (code "209") (name "PB7{slash}SDA_Q4") (class "Default")
      (node (ref "QUADRANT4") (pin "P$23") (pinfunction "I2C_SDA_P$23") (pintype "bidirectional"))
      (node (ref "QUADRANT4") (pin "P$8") (pinfunction "I2C_SDA_P$8") (pintype "bidirectional"))
      (node (ref "R69") (pin "2") (pinfunction "2_2") (pintype "passive"))
      (node (ref "U5") (pin "5") (pinfunction "IO1_5") (pintype "bidirectional"))
    )
    (net (code "210") (name "PEN-SCL-FILT") (class "Default")
      (node (ref "Q30") (pin "4") (pinfunction "D_4") (pintype "passive"))
      (node (ref "R202") (pin "1") (pinfunction "1_1") (pintype "passive"))
      (node (ref "R206") (pin "1") (pinfunction "1_1") (pintype "passive"))
      (node (ref "R210") (pin "1") (pinfunction "1_1") (pintype "passive"))
      (node (ref "R273") (pin "2") (pinfunction "2_2") (pintype "passive"))
      (node (ref "TP116") (pin "1") (pinfunction "1_1") (pintype "passive"))
      (node (ref "U29") (pin "15") (pinfunction "SCL_15") (pintype "input"))
    )
    (net (code "211") (name "PEN-SCL-FILT_Q1") (class "Default")
      (node (ref "Q15") (pin "4") (pinfunction "D_4") (pintype "passive"))
      (node (ref "R113") (pin "2") (pinfunction "2_2") (pintype "passive"))
      (node (ref "R80") (pin "1") (pinfunction "1_1") (pintype "passive"))
      (node (ref "R84") (pin "1") (pinfunction "1_1") (pintype "passive"))
      (node (ref "R88") (pin "1") (pinfunction "1_1") (pintype "passive"))
      (node (ref "TP40") (pin "1") (pinfunction "1_1") (pintype "passive"))
      (node (ref "U9") (pin "15") (pinfunction "SCL_15") (pintype "input"))
    )
    (net (code "212") (name "PEN-SCL-FILT_Q2") (class "Default")
      (node (ref "Q25") (pin "4") (pinfunction "D_4") (pintype "passive"))
      (node (ref "R156") (pin "1") (pinfunction "1_1") (pintype "passive"))
      (node (ref "R160") (pin "1") (pinfunction "1_1") (pintype "passive"))
      (node (ref "R164") (pin "1") (pinfunction "1_1") (pintype "passive"))
      (node (ref "R189") (pin "2") (pinfunction "2_2") (pintype "passive"))
      (node (ref "TP70") (pin "1") (pinfunction "1_1") (pintype "passive"))
      (node (ref "U17") (pin "15") (pinfunction "SCL_15") (pintype "input"))
    )
    (net (code "213") (name "PEN-SCL-FILT_Q3") (class "Default")
      (node (ref "Q35") (pin "4") (pinfunction "D_4") (pintype "passive"))
      (node (ref "R232") (pin "1") (pinfunction "1_1") (pintype "passive"))
      (node (ref "R236") (pin "1") (pinfunction "1_1") (pintype "passive"))
      (node (ref "R240") (pin "1") (pinfunction "1_1") (pintype "passive"))
      (node (ref "R265") (pin "2") (pinfunction "2_2") (pintype "passive"))
      (node (ref "TP100") (pin "1") (pinfunction "1_1") (pintype "passive"))
      (node (ref "U25") (pin "15") (pinfunction "SCL_15") (pintype "input"))
    )
    (net (code "214") (name "PEN-SCL-FILT_Q4") (class "Default")
      (node (ref "Q10") (pin "4") (pinfunction "D_4") (pintype "passive"))
      (node (ref "R42") (pin "1") (pinfunction "1_1") (pintype "passive"))
      (node (ref "R46") (pin "1") (pinfunction "1_1") (pintype "passive"))
      (node (ref "R50") (pin "1") (pinfunction "1_1") (pintype "passive"))
      (node (ref "R75") (pin "2") (pinfunction "2_2") (pintype "passive"))
      (node (ref "TP25") (pin "1") (pinfunction "1_1") (pintype "passive"))
      (node (ref "U5") (pin "15") (pinfunction "SCL_15") (pintype "input"))
    )
    (net (code "215") (name "PEN-SDA-FILT") (class "Default")
      (node (ref "Q30") (pin "6") (pinfunction "D_6") (pintype "passive"))
      (node (ref "R204") (pin "2") (pinfunction "2_2") (pintype "passive"))
      (node (ref "R208") (pin "2") (pinfunction "2_2") (pintype "passive"))
      (node (ref "R212") (pin "2") (pinfunction "2_2") (pintype "passive"))
      (node (ref "R269") (pin "2") (pinfunction "2_2") (pintype "passive"))
      (node (ref "TP117") (pin "1") (pinfunction "1_1") (pintype "passive"))
      (node (ref "U29") (pin "16") (pinfunction "SDA_16") (pintype "bidirectional"))
    )
    (net (code "216") (name "PEN-SDA-FILT_Q1") (class "Default")
      (node (ref "Q15") (pin "6") (pinfunction "D_6") (pintype "passive"))
      (node (ref "R109") (pin "2") (pinfunction "2_2") (pintype "passive"))
      (node (ref "R82") (pin "2") (pinfunction "2_2") (pintype "passive"))
      (node (ref "R86") (pin "2") (pinfunction "2_2") (pintype "passive"))
      (node (ref "R90") (pin "2") (pinfunction "2_2") (pintype "passive"))
      (node (ref "TP41") (pin "1") (pinfunction "1_1") (pintype "passive"))
      (node (ref "U9") (pin "16") (pinfunction "SDA_16") (pintype "bidirectional"))
    )
    (net (code "217") (name "PEN-SDA-FILT_Q2") (class "Default")
      (node (ref "Q25") (pin "6") (pinfunction "D_6") (pintype "passive"))
      (node (ref "R158") (pin "2") (pinfunction "2_2") (pintype "passive"))
      (node (ref "R162") (pin "2") (pinfunction "2_2") (pintype "passive"))
      (node (ref "R166") (pin "2") (pinfunction "2_2") (pintype "passive"))
      (node (ref "R185") (pin "2") (pinfunction "2_2") (pintype "passive"))
      (node (ref "TP71") (pin "1") (pinfunction "1_1") (pintype "passive"))
      (node (ref "U17") (pin "16") (pinfunction "SDA_16") (pintype "bidirectional"))
    )
    (net (code "218") (name "PEN-SDA-FILT_Q3") (class "Default")
      (node (ref "Q35") (pin "6") (pinfunction "D_6") (pintype "passive"))
      (node (ref "R234") (pin "2") (pinfunction "2_2") (pintype "passive"))
      (node (ref "R238") (pin "2") (pinfunction "2_2") (pintype "passive"))
      (node (ref "R242") (pin "2") (pinfunction "2_2") (pintype "passive"))
      (node (ref "R261") (pin "2") (pinfunction "2_2") (pintype "passive"))
      (node (ref "TP101") (pin "1") (pinfunction "1_1") (pintype "passive"))
      (node (ref "U25") (pin "16") (pinfunction "SDA_16") (pintype "bidirectional"))
    )
    (net (code "219") (name "PEN-SDA-FILT_Q4") (class "Default")
      (node (ref "Q10") (pin "6") (pinfunction "D_6") (pintype "passive"))
      (node (ref "R44") (pin "2") (pinfunction "2_2") (pintype "passive"))
      (node (ref "R48") (pin "2") (pinfunction "2_2") (pintype "passive"))
      (node (ref "R52") (pin "2") (pinfunction "2_2") (pintype "passive"))
      (node (ref "R71") (pin "2") (pinfunction "2_2") (pintype "passive"))
      (node (ref "TP26") (pin "1") (pinfunction "1_1") (pintype "passive"))
      (node (ref "U5") (pin "16") (pinfunction "SDA_16") (pintype "bidirectional"))
    )
    (net (code "220") (name "POUT") (class "Default")
      (node (ref "R9") (pin "1") (pinfunction "1_1") (pintype "passive"))
      (node (ref "TP89") (pin "1") (pinfunction "1_1") (pintype "passive"))
      (node (ref "U30") (pin "13") (pinfunction "POUT_13") (pintype "output"))
    )
    (net (code "221") (name "POUT_Q1") (class "Default")
      (node (ref "TP31") (pin "1") (pinfunction "1_1") (pintype "passive"))
      (node (ref "U10") (pin "13") (pinfunction "POUT_13") (pintype "output"))
    )
    (net (code "222") (name "POUT_Q2") (class "Default")
      (node (ref "TP61") (pin "1") (pinfunction "1_1") (pintype "passive"))
      (node (ref "U18") (pin "13") (pinfunction "POUT_13") (pintype "output"))
    )
    (net (code "223") (name "POUT_Q3") (class "Default")
      (node (ref "TP91") (pin "1") (pinfunction "1_1") (pintype "passive"))
      (node (ref "U26") (pin "13") (pinfunction "POUT_13") (pintype "output"))
    )
    (net (code "224") (name "POUT_Q4") (class "Default")
      (node (ref "TP2") (pin "1") (pinfunction "1_1") (pintype "passive"))
      (node (ref "U6") (pin "13") (pinfunction "POUT_13") (pintype "output"))
    )
    (net (code "225") (name "SWCLK") (class "Default")
      (node (ref "J2") (pin "15") (pinfunction "SWCLK_15") (pintype "passive"))
      (node (ref "U15") (pin "37") (pinfunction "PA14-SWCLK_37") (pintype "bidirectional"))
    )
    (net (code "226") (name "SWDIO") (class "Default")
      (node (ref "J2") (pin "14") (pinfunction "SWDIO_14") (pintype "passive"))
      (node (ref "U15") (pin "34") (pinfunction "PA13-SWDIO_34") (pintype "bidirectional"))
    )
    (net (code "227") (name "VBUS") (class "Default")
      (node (ref "J6") (pin "21") (pinfunction "21_21") (pintype "passive"))
      (node (ref "J6") (pin "22") (pinfunction "22_22") (pintype "passive"))
      (node (ref "J6") (pin "23") (pinfunction "23_23") (pintype "passive"))
      (node (ref "J6") (pin "24") (pinfunction "24_24") (pintype "passive"))
      (node (ref "J6") (pin "25") (pinfunction "25_25") (pintype "passive"))
      (node (ref "J6") (pin "26") (pinfunction "26_26") (pintype "passive"))
      (node (ref "Q12") (pin "4") (pinfunction "S_4") (pintype "passive"))
      (node (ref "Q22") (pin "4") (pinfunction "S_4") (pintype "passive"))
      (node (ref "Q27") (pin "4") (pinfunction "S_4") (pintype "passive"))
      (node (ref "Q32") (pin "4") (pinfunction "S_4") (pintype "passive"))
      (node (ref "Q7") (pin "4") (pinfunction "S_4") (pintype "passive"))
      (node (ref "R169") (pin "2") (pinfunction "2_2") (pintype "passive"))
      (node (ref "R215") (pin "2") (pinfunction "2_2") (pintype "passive"))
      (node (ref "R245") (pin "2") (pinfunction "2_2") (pintype "passive"))
      (node (ref "R55") (pin "2") (pinfunction "2_2") (pintype "passive"))
      (node (ref "R93") (pin "2") (pinfunction "2_2") (pintype "passive"))
    )
    (net (code "228") (name "VBUSP") (class "Default")
      (node (ref "C44") (pin "2") (pinfunction "2_2") (pintype "passive"))
      (node (ref "C45") (pin "1") (pinfunction "1_1") (pintype "passive"))
      (node (ref "C46") (pin "1") (pinfunction "1_1") (pintype "passive"))
      (node (ref "J2") (pin "1") (pinfunction "VBUSP_1") (pintype "passive"))
      (node (ref "J2") (pin "2") (pinfunction "VBUSP_2") (pintype "passive"))
      (node (ref "Q26") (pin "1") (pinfunction "D_1") (pintype "passive"))
      (node (ref "Q26") (pin "2") (pinfunction "D_2") (pintype "passive"))
      (node (ref "Q26") (pin "5") (pinfunction "D_5") (pintype "passive"))
      (node (ref "Q26") (pin "6") (pinfunction "D_6") (pintype "passive"))
      (node (ref "R198") (pin "2") (pinfunction "2_2") (pintype "passive"))
      (node (ref "R227") (pin "2") (pinfunction "2_2") (pintype "passive"))
      (node (ref "TP110") (pin "1") (pinfunction "1_1") (pintype "passive"))
      (node (ref "U31") (pin "2") (pinfunction "VIN_2") (pintype "power_in"))
      (node (ref "U31") (pin "3") (pinfunction "VIN_3") (pintype "power_in"))
      (node (ref "U31") (pin "4") (pinfunction "EN_4") (pintype "input"))
      (node (ref "U31") (pin "8") (pinfunction "VIN_8") (pintype "power_in"))
    )
    (net (code "229") (name "VBUSP_Q1") (class "Default")
      (node (ref "C12") (pin "2") (pinfunction "2_2") (pintype "passive"))
      (node (ref "Q11") (pin "1") (pinfunction "D_1") (pintype "passive"))
      (node (ref "Q11") (pin "2") (pinfunction "D_2") (pintype "passive"))
      (node (ref "Q11") (pin "5") (pinfunction "D_5") (pintype "passive"))
      (node (ref "Q11") (pin "6") (pinfunction "D_6") (pintype "passive"))
      (node (ref "QUADRANT1") (pin "P$12") (pinfunction "VCC_P$12") (pintype "bidirectional"))
      (node (ref "QUADRANT1") (pin "P$13") (pinfunction "VCC_P$13") (pintype "bidirectional"))
      (node (ref "QUADRANT1") (pin "P$18") (pinfunction "VCC_P$18") (pintype "bidirectional"))
      (node (ref "QUADRANT1") (pin "P$19") (pinfunction "VCC_P$19") (pintype "bidirectional"))
      (node (ref "QUADRANT1") (pin "P$27") (pinfunction "VCC_P$27") (pintype "bidirectional"))
      (node (ref "QUADRANT1") (pin "P$28") (pinfunction "VCC_P$28") (pintype "bidirectional"))
      (node (ref "QUADRANT1") (pin "P$3") (pinfunction "VCC_P$3") (pintype "bidirectional"))
      (node (ref "QUADRANT1") (pin "P$4") (pinfunction "VCC_P$4") (pintype "bidirectional"))
      (node (ref "R77") (pin "2") (pinfunction "2_2") (pintype "passive"))
      (node (ref "TP37") (pin "1") (pinfunction "1_1") (pintype "passive"))
    )
    (net (code "230") (name "VBUSP_Q2") (class "Default")
      (node (ref "C22") (pin "2") (pinfunction "2_2") (pintype "passive"))
      (node (ref "Q21") (pin "1") (pinfunction "D_1") (pintype "passive"))
      (node (ref "Q21") (pin "2") (pinfunction "D_2") (pintype "passive"))
      (node (ref "Q21") (pin "5") (pinfunction "D_5") (pintype "passive"))
      (node (ref "Q21") (pin "6") (pinfunction "D_6") (pintype "passive"))
      (node (ref "QUADRANT2") (pin "P$12") (pinfunction "VCC_P$12") (pintype "bidirectional"))
      (node (ref "QUADRANT2") (pin "P$13") (pinfunction "VCC_P$13") (pintype "bidirectional"))
      (node (ref "QUADRANT2") (pin "P$18") (pinfunction "VCC_P$18") (pintype "bidirectional"))
      (node (ref "QUADRANT2") (pin "P$19") (pinfunction "VCC_P$19") (pintype "bidirectional"))
      (node (ref "QUADRANT2") (pin "P$27") (pinfunction "VCC_P$27") (pintype "bidirectional"))
      (node (ref "QUADRANT2") (pin "P$28") (pinfunction "VCC_P$28") (pintype "bidirectional"))
      (node (ref "QUADRANT2") (pin "P$3") (pinfunction "VCC_P$3") (pintype "bidirectional"))
      (node (ref "QUADRANT2") (pin "P$4") (pinfunction "VCC_P$4") (pintype "bidirectional"))
      (node (ref "R153") (pin "2") (pinfunction "2_2") (pintype "passive"))
      (node (ref "TP67") (pin "1") (pinfunction "1_1") (pintype "passive"))
    )
    (net (code "231") (name "VBUSP_Q3") (class "Default")
      (node (ref "C32") (pin "2") (pinfunction "2_2") (pintype "passive"))
      (node (ref "Q31") (pin "1") (pinfunction "D_1") (pintype "passive"))
      (node (ref "Q31") (pin "2") (pinfunction "D_2") (pintype "passive"))
      (node (ref "Q31") (pin "5") (pinfunction "D_5") (pintype "passive"))
      (node (ref "Q31") (pin "6") (pinfunction "D_6") (pintype "passive"))
      (node (ref "QUADRANT3") (pin "P$12") (pinfunction "VCC_P$12") (pintype "bidirectional"))
      (node (ref "QUADRANT3") (pin "P$13") (pinfunction "VCC_P$13") (pintype "bidirectional"))
      (node (ref "QUADRANT3") (pin "P$18") (pinfunction "VCC_P$18") (pintype "bidirectional"))
      (node (ref "QUADRANT3") (pin "P$19") (pinfunction "VCC_P$19") (pintype "bidirectional"))
      (node (ref "QUADRANT3") (pin "P$27") (pinfunction "VCC_P$27") (pintype "bidirectional"))
      (node (ref "QUADRANT3") (pin "P$28") (pinfunction "VCC_P$28") (pintype "bidirectional"))
      (node (ref "QUADRANT3") (pin "P$3") (pinfunction "VCC_P$3") (pintype "bidirectional"))
      (node (ref "QUADRANT3") (pin "P$4") (pinfunction "VCC_P$4") (pintype "bidirectional"))
      (node (ref "R229") (pin "2") (pinfunction "2_2") (pintype "passive"))
      (node (ref "TP97") (pin "1") (pinfunction "1_1") (pintype "passive"))
    )
    (net (code "232") (name "VBUSP_Q4") (class "Default")
      (node (ref "C7") (pin "2") (pinfunction "2_2") (pintype "passive"))
      (node (ref "Q6") (pin "1") (pinfunction "D_1") (pintype "passive"))
      (node (ref "Q6") (pin "2") (pinfunction "D_2") (pintype "passive"))
      (node (ref "Q6") (pin "5") (pinfunction "D_5") (pintype "passive"))
      (node (ref "Q6") (pin "6") (pinfunction "D_6") (pintype "passive"))
      (node (ref "QUADRANT4") (pin "P$12") (pinfunction "VCC_P$12") (pintype "bidirectional"))
      (node (ref "QUADRANT4") (pin "P$13") (pinfunction "VCC_P$13") (pintype "bidirectional"))
      (node (ref "QUADRANT4") (pin "P$18") (pinfunction "VCC_P$18") (pintype "bidirectional"))
      (node (ref "QUADRANT4") (pin "P$19") (pinfunction "VCC_P$19") (pintype "bidirectional"))
      (node (ref "QUADRANT4") (pin "P$27") (pinfunction "VCC_P$27") (pintype "bidirectional"))
      (node (ref "QUADRANT4") (pin "P$28") (pinfunction "VCC_P$28") (pintype "bidirectional"))
      (node (ref "QUADRANT4") (pin "P$3") (pinfunction "VCC_P$3") (pintype "bidirectional"))
      (node (ref "QUADRANT4") (pin "P$4") (pinfunction "VCC_P$4") (pintype "bidirectional"))
      (node (ref "R39") (pin "2") (pinfunction "2_2") (pintype "passive"))
      (node (ref "TP21") (pin "1") (pinfunction "1_1") (pintype "passive"))
    )
    (net (code "233") (name "VPD") (class "Default")
      (node (ref "C43") (pin "2") (pinfunction "2_2") (pintype "passive"))
      (node (ref "R200") (pin "2") (pinfunction "2_2") (pintype "passive"))
      (node (ref "R201") (pin "2") (pinfunction "2_2") (pintype "passive"))
      (node (ref "R205") (pin "2") (pinfunction "2_2") (pintype "passive"))
      (node (ref "R209") (pin "2") (pinfunction "2_2") (pintype "passive"))
      (node (ref "R214") (pin "2") (pinfunction "2_2") (pintype "passive"))
      (node (ref "R226") (pin "2") (pinfunction "2_2") (pintype "passive"))
      (node (ref "R270") (pin "2") (pinfunction "2_2") (pintype "passive"))
      (node (ref "R274") (pin "2") (pinfunction "2_2") (pintype "passive"))
      (node (ref "TP114") (pin "1") (pinfunction "1_1") (pintype "passive"))
      (node (ref "U29") (pin "14") (pinfunction "V+_14") (pintype "power_in"))
      (node (ref "U32") (pin "5") (pinfunction "VDD_5") (pintype "power_in"))
      (node (ref "U33") (pin "5") (pinfunction "VDD_5") (pintype "power_in"))
    )
    (net (code "234") (name "VPD_Q1") (class "Default")
      (node (ref "C11") (pin "2") (pinfunction "2_2") (pintype "passive"))
      (node (ref "R104") (pin "2") (pinfunction "2_2") (pintype "passive"))
      (node (ref "R110") (pin "2") (pinfunction "2_2") (pintype "passive"))
      (node (ref "R114") (pin "2") (pinfunction "2_2") (pintype "passive"))
      (node (ref "R78") (pin "2") (pinfunction "2_2") (pintype "passive"))
      (node (ref "R79") (pin "2") (pinfunction "2_2") (pintype "passive"))
      (node (ref "R83") (pin "2") (pinfunction "2_2") (pintype "passive"))
      (node (ref "R87") (pin "2") (pinfunction "2_2") (pintype "passive"))
      (node (ref "R92") (pin "2") (pinfunction "2_2") (pintype "passive"))
      (node (ref "TP38") (pin "1") (pinfunction "1_1") (pintype "passive"))
      (node (ref "U11") (pin "5") (pinfunction "VDD_5") (pintype "power_in"))
      (node (ref "U12") (pin "5") (pinfunction "VDD_5") (pintype "power_in"))
      (node (ref "U9") (pin "14") (pinfunction "V+_14") (pintype "power_in"))
    )
    (net (code "235") (name "VPD_Q2") (class "Default")
      (node (ref "C21") (pin "2") (pinfunction "2_2") (pintype "passive"))
      (node (ref "R154") (pin "2") (pinfunction "2_2") (pintype "passive"))
      (node (ref "R155") (pin "2") (pinfunction "2_2") (pintype "passive"))
      (node (ref "R159") (pin "2") (pinfunction "2_2") (pintype "passive"))
      (node (ref "R163") (pin "2") (pinfunction "2_2") (pintype "passive"))
      (node (ref "R168") (pin "2") (pinfunction "2_2") (pintype "passive"))
      (node (ref "R180") (pin "2") (pinfunction "2_2") (pintype "passive"))
      (node (ref "R186") (pin "2") (pinfunction "2_2") (pintype "passive"))
      (node (ref "R190") (pin "2") (pinfunction "2_2") (pintype "passive"))
      (node (ref "TP68") (pin "1") (pinfunction "1_1") (pintype "passive"))
      (node (ref "U17") (pin "14") (pinfunction "V+_14") (pintype "power_in"))
      (node (ref "U19") (pin "5") (pinfunction "VDD_5") (pintype "power_in"))
      (node (ref "U20") (pin "5") (pinfunction "VDD_5") (pintype "power_in"))
    )
    (net (code "236") (name "VPD_Q3") (class "Default")
      (node (ref "C31") (pin "2") (pinfunction "2_2") (pintype "passive"))
      (node (ref "R230") (pin "2") (pinfunction "2_2") (pintype "passive"))
      (node (ref "R231") (pin "2") (pinfunction "2_2") (pintype "passive"))
      (node (ref "R235") (pin "2") (pinfunction "2_2") (pintype "passive"))
      (node (ref "R239") (pin "2") (pinfunction "2_2") (pintype "passive"))
      (node (ref "R244") (pin "2") (pinfunction "2_2") (pintype "passive"))
      (node (ref "R256") (pin "2") (pinfunction "2_2") (pintype "passive"))
      (node (ref "R262") (pin "2") (pinfunction "2_2") (pintype "passive"))
      (node (ref "R266") (pin "2") (pinfunction "2_2") (pintype "passive"))
      (node (ref "TP98") (pin "1") (pinfunction "1_1") (pintype "passive"))
      (node (ref "U25") (pin "14") (pinfunction "V+_14") (pintype "power_in"))
      (node (ref "U27") (pin "5") (pinfunction "VDD_5") (pintype "power_in"))
      (node (ref "U28") (pin "5") (pinfunction "VDD_5") (pintype "power_in"))
    )
    (net (code "237") (name "VPD_Q4") (class "Default")
      (node (ref "C6") (pin "2") (pinfunction "2_2") (pintype "passive"))
      (node (ref "R40") (pin "2") (pinfunction "2_2") (pintype "passive"))
      (node (ref "R41") (pin "2") (pinfunction "2_2") (pintype "passive"))
      (node (ref "R45") (pin "2") (pinfunction "2_2") (pintype "passive"))
      (node (ref "R49") (pin "2") (pinfunction "2_2") (pintype "passive"))
      (node (ref "R54") (pin "2") (pinfunction "2_2") (pintype "passive"))
      (node (ref "R66") (pin "2") (pinfunction "2_2") (pintype "passive"))
      (node (ref "R72") (pin "2") (pinfunction "2_2") (pintype "passive"))
      (node (ref "R76") (pin "2") (pinfunction "2_2") (pintype "passive"))
      (node (ref "TP23") (pin "1") (pinfunction "1_1") (pintype "passive"))
      (node (ref "U5") (pin "14") (pinfunction "V+_14") (pintype "power_in"))
      (node (ref "U7") (pin "5") (pinfunction "VDD_5") (pintype "power_in"))
      (node (ref "U8") (pin "5") (pinfunction "VDD_5") (pintype "power_in"))
    )
    (net (code "238") (name "unconnected-(FIDUCIAL1-PadFIDUCIAL)") (class "Default")
      (node (ref "FIDUCIAL1") (pin "FIDUCIAL") (pinfunction "FIDUCIAL_FIDUCIAL") (pintype "no_connect"))
    )
    (net (code "239") (name "unconnected-(FIDUCIAL2-PadFIDUCIAL)") (class "Default")
      (node (ref "FIDUCIAL2") (pin "FIDUCIAL") (pinfunction "FIDUCIAL_FIDUCIAL") (pintype "no_connect"))
    )
    (net (code "240") (name "unconnected-(FIDUCIAL3-PadFIDUCIAL)") (class "Default")
      (node (ref "FIDUCIAL3") (pin "FIDUCIAL") (pinfunction "FIDUCIAL_FIDUCIAL") (pintype "no_connect"))
    )
    (net (code "241") (name "unconnected-(FIDUCIAL4-PadFIDUCIAL)") (class "Default")
      (node (ref "FIDUCIAL4") (pin "FIDUCIAL") (pinfunction "FIDUCIAL_FIDUCIAL") (pintype "no_connect"))
    )
    (net (code "242") (name "unconnected-(FIDUCIAL5-PadFIDUCIAL)") (class "Default")
      (node (ref "FIDUCIAL5") (pin "FIDUCIAL") (pinfunction "FIDUCIAL_FIDUCIAL") (pintype "no_connect"))
    )
    (net (code "243") (name "unconnected-(FIDUCIAL6-PadFIDUCIAL)") (class "Default")
      (node (ref "FIDUCIAL6") (pin "FIDUCIAL") (pinfunction "FIDUCIAL_FIDUCIAL") (pintype "no_connect"))
    )
    (net (code "244") (name "unconnected-(J2-DEVICE-D+-Pad4)") (class "Default")
      (node (ref "J2") (pin "4") (pinfunction "DEVICE-D+_4") (pintype "passive"))
    )
    (net (code "245") (name "unconnected-(J2-DEVICE-D--Pad5)") (class "Default")
      (node (ref "J2") (pin "5") (pinfunction "DEVICE-D-_5") (pintype "passive"))
    )
    (net (code "246") (name "unconnected-(J2-HOST-D+-Pad7)") (class "Default")
      (node (ref "J2") (pin "7") (pinfunction "HOST-D+_7") (pintype "passive"))
    )
    (net (code "247") (name "unconnected-(J2-HOST-D--Pad8)") (class "Default")
      (node (ref "J2") (pin "8") (pinfunction "HOST-D-_8") (pintype "passive"))
    )
    (net (code "248") (name "unconnected-(U13-CSB1-Pad14)") (class "Default")
      (node (ref "U13") (pin "14") (pinfunction "CSB1_14") (pintype "input"))
    )
    (net (code "249") (name "unconnected-(U13-CSB2-Pad5)") (class "Default")
      (node (ref "U13") (pin "5") (pinfunction "CSB2_5") (pintype "input"))
    )
    (net (code "250") (name "unconnected-(U15-PA1-Pad11)") (class "Default")
      (node (ref "U15") (pin "11") (pinfunction "PA1_11") (pintype "bidirectional"))
    )
    (net (code "251") (name "unconnected-(U15-PA4-Pad14)") (class "Default")
      (node (ref "U15") (pin "14") (pinfunction "PA4_14") (pintype "bidirectional"))
    )
    (net (code "252") (name "unconnected-(U15-PA5-Pad15)") (class "Default")
      (node (ref "U15") (pin "15") (pinfunction "PA5_15") (pintype "bidirectional"))
    )
    (net (code "253") (name "unconnected-(U15-PA6-Pad16)") (class "Default")
      (node (ref "U15") (pin "16") (pinfunction "PA6_16") (pintype "bidirectional"))
    )
    (net (code "254") (name "unconnected-(U15-PA7-Pad17)") (class "Default")
      (node (ref "U15") (pin "17") (pinfunction "PA7_17") (pintype "bidirectional"))
    )
    (net (code "255") (name "unconnected-(U15-PA15-Pad38)") (class "Default")
      (node (ref "U15") (pin "38") (pinfunction "PA15_38") (pintype "bidirectional"))
    )
    (net (code "256") (name "unconnected-(U15-PB0-Pad18)") (class "Default")
      (node (ref "U15") (pin "18") (pinfunction "PB0_18") (pintype "bidirectional"))
    )
    (net (code "257") (name "unconnected-(U15-PB1-Pad19)") (class "Default")
      (node (ref "U15") (pin "19") (pinfunction "PB1_19") (pintype "bidirectional"))
    )
    (net (code "258") (name "unconnected-(U15-PB2-Pad20)") (class "Default")
      (node (ref "U15") (pin "20") (pinfunction "PB2_20") (pintype "bidirectional"))
    )
    (net (code "259") (name "unconnected-(U15-PB8-Pad45)") (class "Default")
      (node (ref "U15") (pin "45") (pinfunction "PB8_45") (pintype "bidirectional"))
    )
    (net (code "260") (name "unconnected-(U15-PB9-Pad46)") (class "Default")
      (node (ref "U15") (pin "46") (pinfunction "PB9_46") (pintype "bidirectional"))
    )
    (net (code "261") (name "unconnected-(U15-PB10-Pad21)") (class "Default")
      (node (ref "U15") (pin "21") (pinfunction "PB10_21") (pintype "bidirectional"))
    )
    (net (code "262") (name "unconnected-(U15-PB11-Pad22)") (class "Default")
      (node (ref "U15") (pin "22") (pinfunction "PB11_22") (pintype "bidirectional"))
    )
    (net (code "263") (name "unconnected-(U15-PC13-Pad2)") (class "Default")
      (node (ref "U15") (pin "2") (pinfunction "PC13_2") (pintype "bidirectional"))
    )
    (net (code "264") (name "unconnected-(U15-PC14-OSC32_IN-Pad3)") (class "Default")
      (node (ref "U15") (pin "3") (pinfunction "PC14-OSC32_IN_3") (pintype "bidirectional"))
    )
    (net (code "265") (name "unconnected-(U15-PC15-OSC32_OUT-Pad4)") (class "Default")
      (node (ref "U15") (pin "4") (pinfunction "PC15-OSC32_OUT_4") (pintype "bidirectional"))
    )
    (net (code "266") (name "~{FAULT_Q1}") (class "Default")
      (node (ref "Q14") (pin "3") (pinfunction "D_3") (pintype "passive"))
      (node (ref "R104") (pin "1") (pinfunction "1_1") (pintype "passive"))
      (node (ref "TP36") (pin "1") (pinfunction "1_1") (pintype "passive"))
      (node (ref "U9") (pin "7") (pinfunction "IO2_7") (pintype "bidirectional"))
    )
    (net (code "267") (name "~{FAULT_Q2}") (class "Default")
      (node (ref "Q24") (pin "3") (pinfunction "D_3") (pintype "passive"))
      (node (ref "R180") (pin "1") (pinfunction "1_1") (pintype "passive"))
      (node (ref "TP66") (pin "1") (pinfunction "1_1") (pintype "passive"))
      (node (ref "U17") (pin "7") (pinfunction "IO2_7") (pintype "bidirectional"))
    )
    (net (code "268") (name "~{FAULT_Q3}") (class "Default")
      (node (ref "Q34") (pin "3") (pinfunction "D_3") (pintype "passive"))
      (node (ref "R256") (pin "1") (pinfunction "1_1") (pintype "passive"))
      (node (ref "TP96") (pin "1") (pinfunction "1_1") (pintype "passive"))
      (node (ref "U25") (pin "7") (pinfunction "IO2_7") (pintype "bidirectional"))
    )
    (net (code "269") (name "~{FAULT_Q4}") (class "Default")
      (node (ref "Q9") (pin "3") (pinfunction "D_3") (pintype "passive"))
      (node (ref "R66") (pin "1") (pinfunction "1_1") (pintype "passive"))
      (node (ref "TP19") (pin "1") (pinfunction "1_1") (pintype "passive"))
      (node (ref "U5") (pin "7") (pinfunction "IO2_7") (pintype "bidirectional"))
    )
    (net (code "270") (name "~{FAULT}") (class "Default")
      (node (ref "Q29") (pin "3") (pinfunction "D_3") (pintype "passive"))
      (node (ref "R226") (pin "1") (pinfunction "1_1") (pintype "passive"))
      (node (ref "TP109") (pin "1") (pinfunction "1_1") (pintype "passive"))
      (node (ref "U29") (pin "7") (pinfunction "IO2_7") (pintype "bidirectional"))
    )
  )
)
